# design.net
KiCad netlist of a schematic drawn in EasyEDA Pro
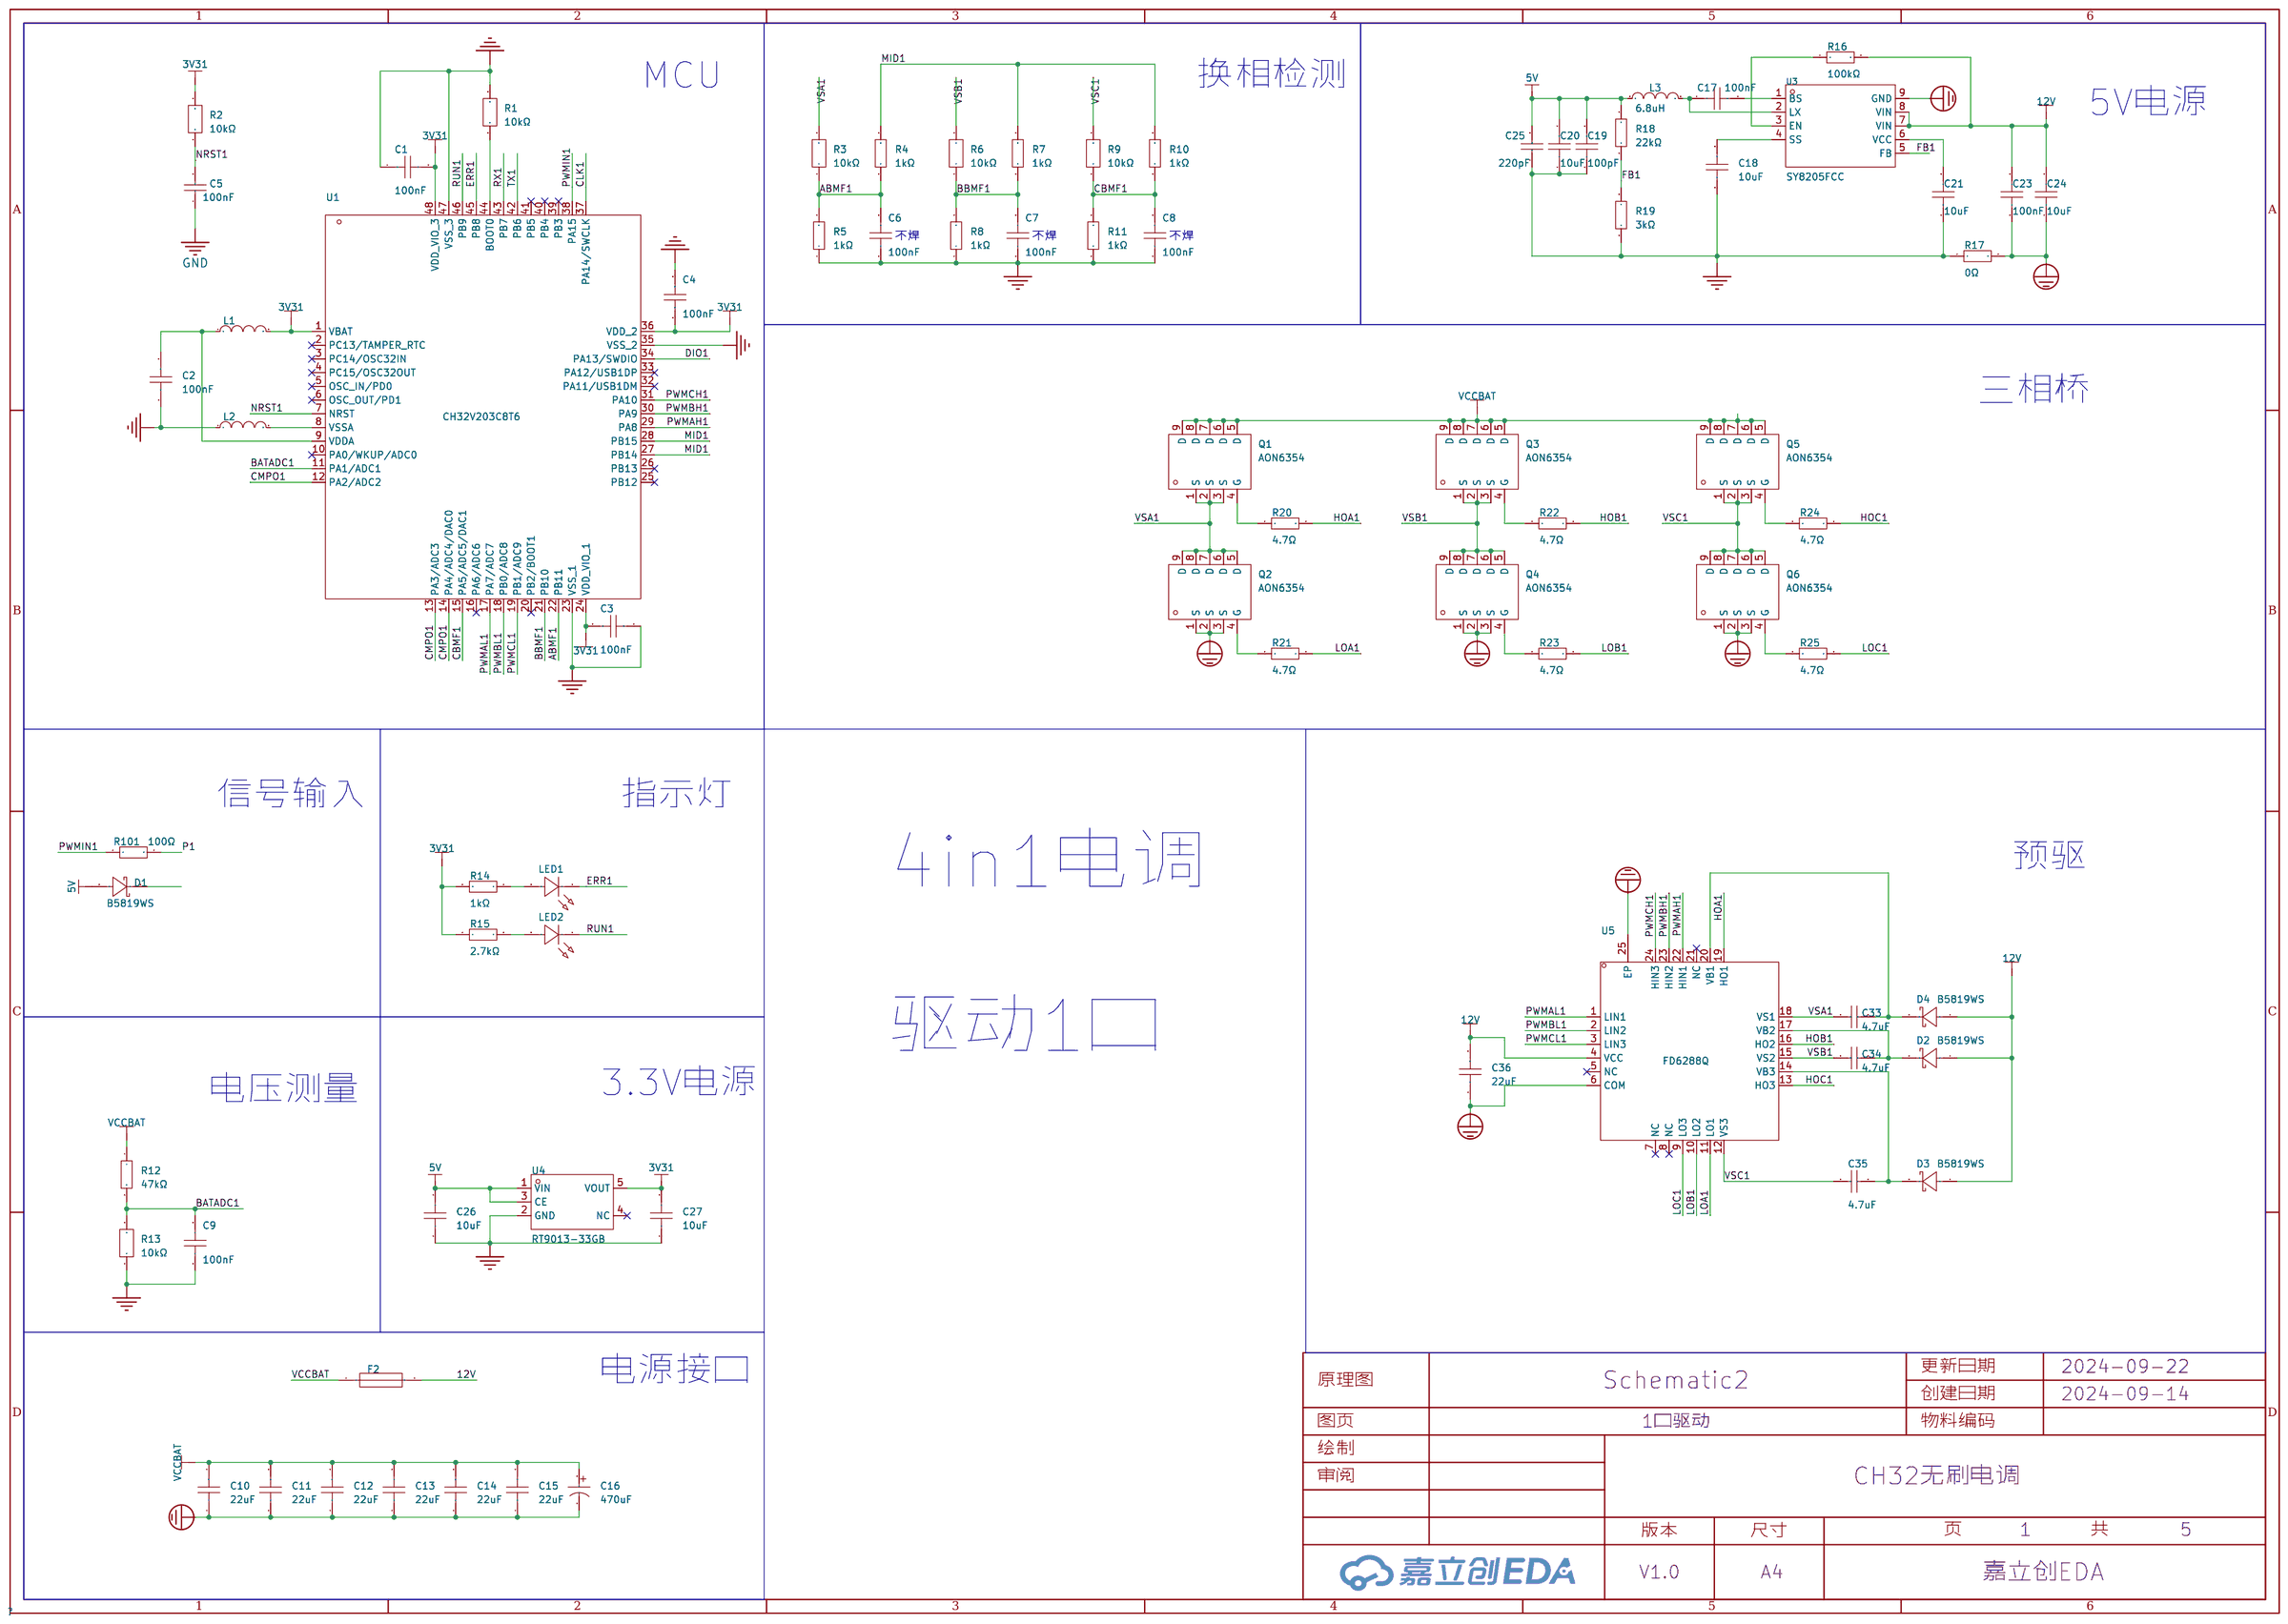
[diagram p0: 1口驱动]
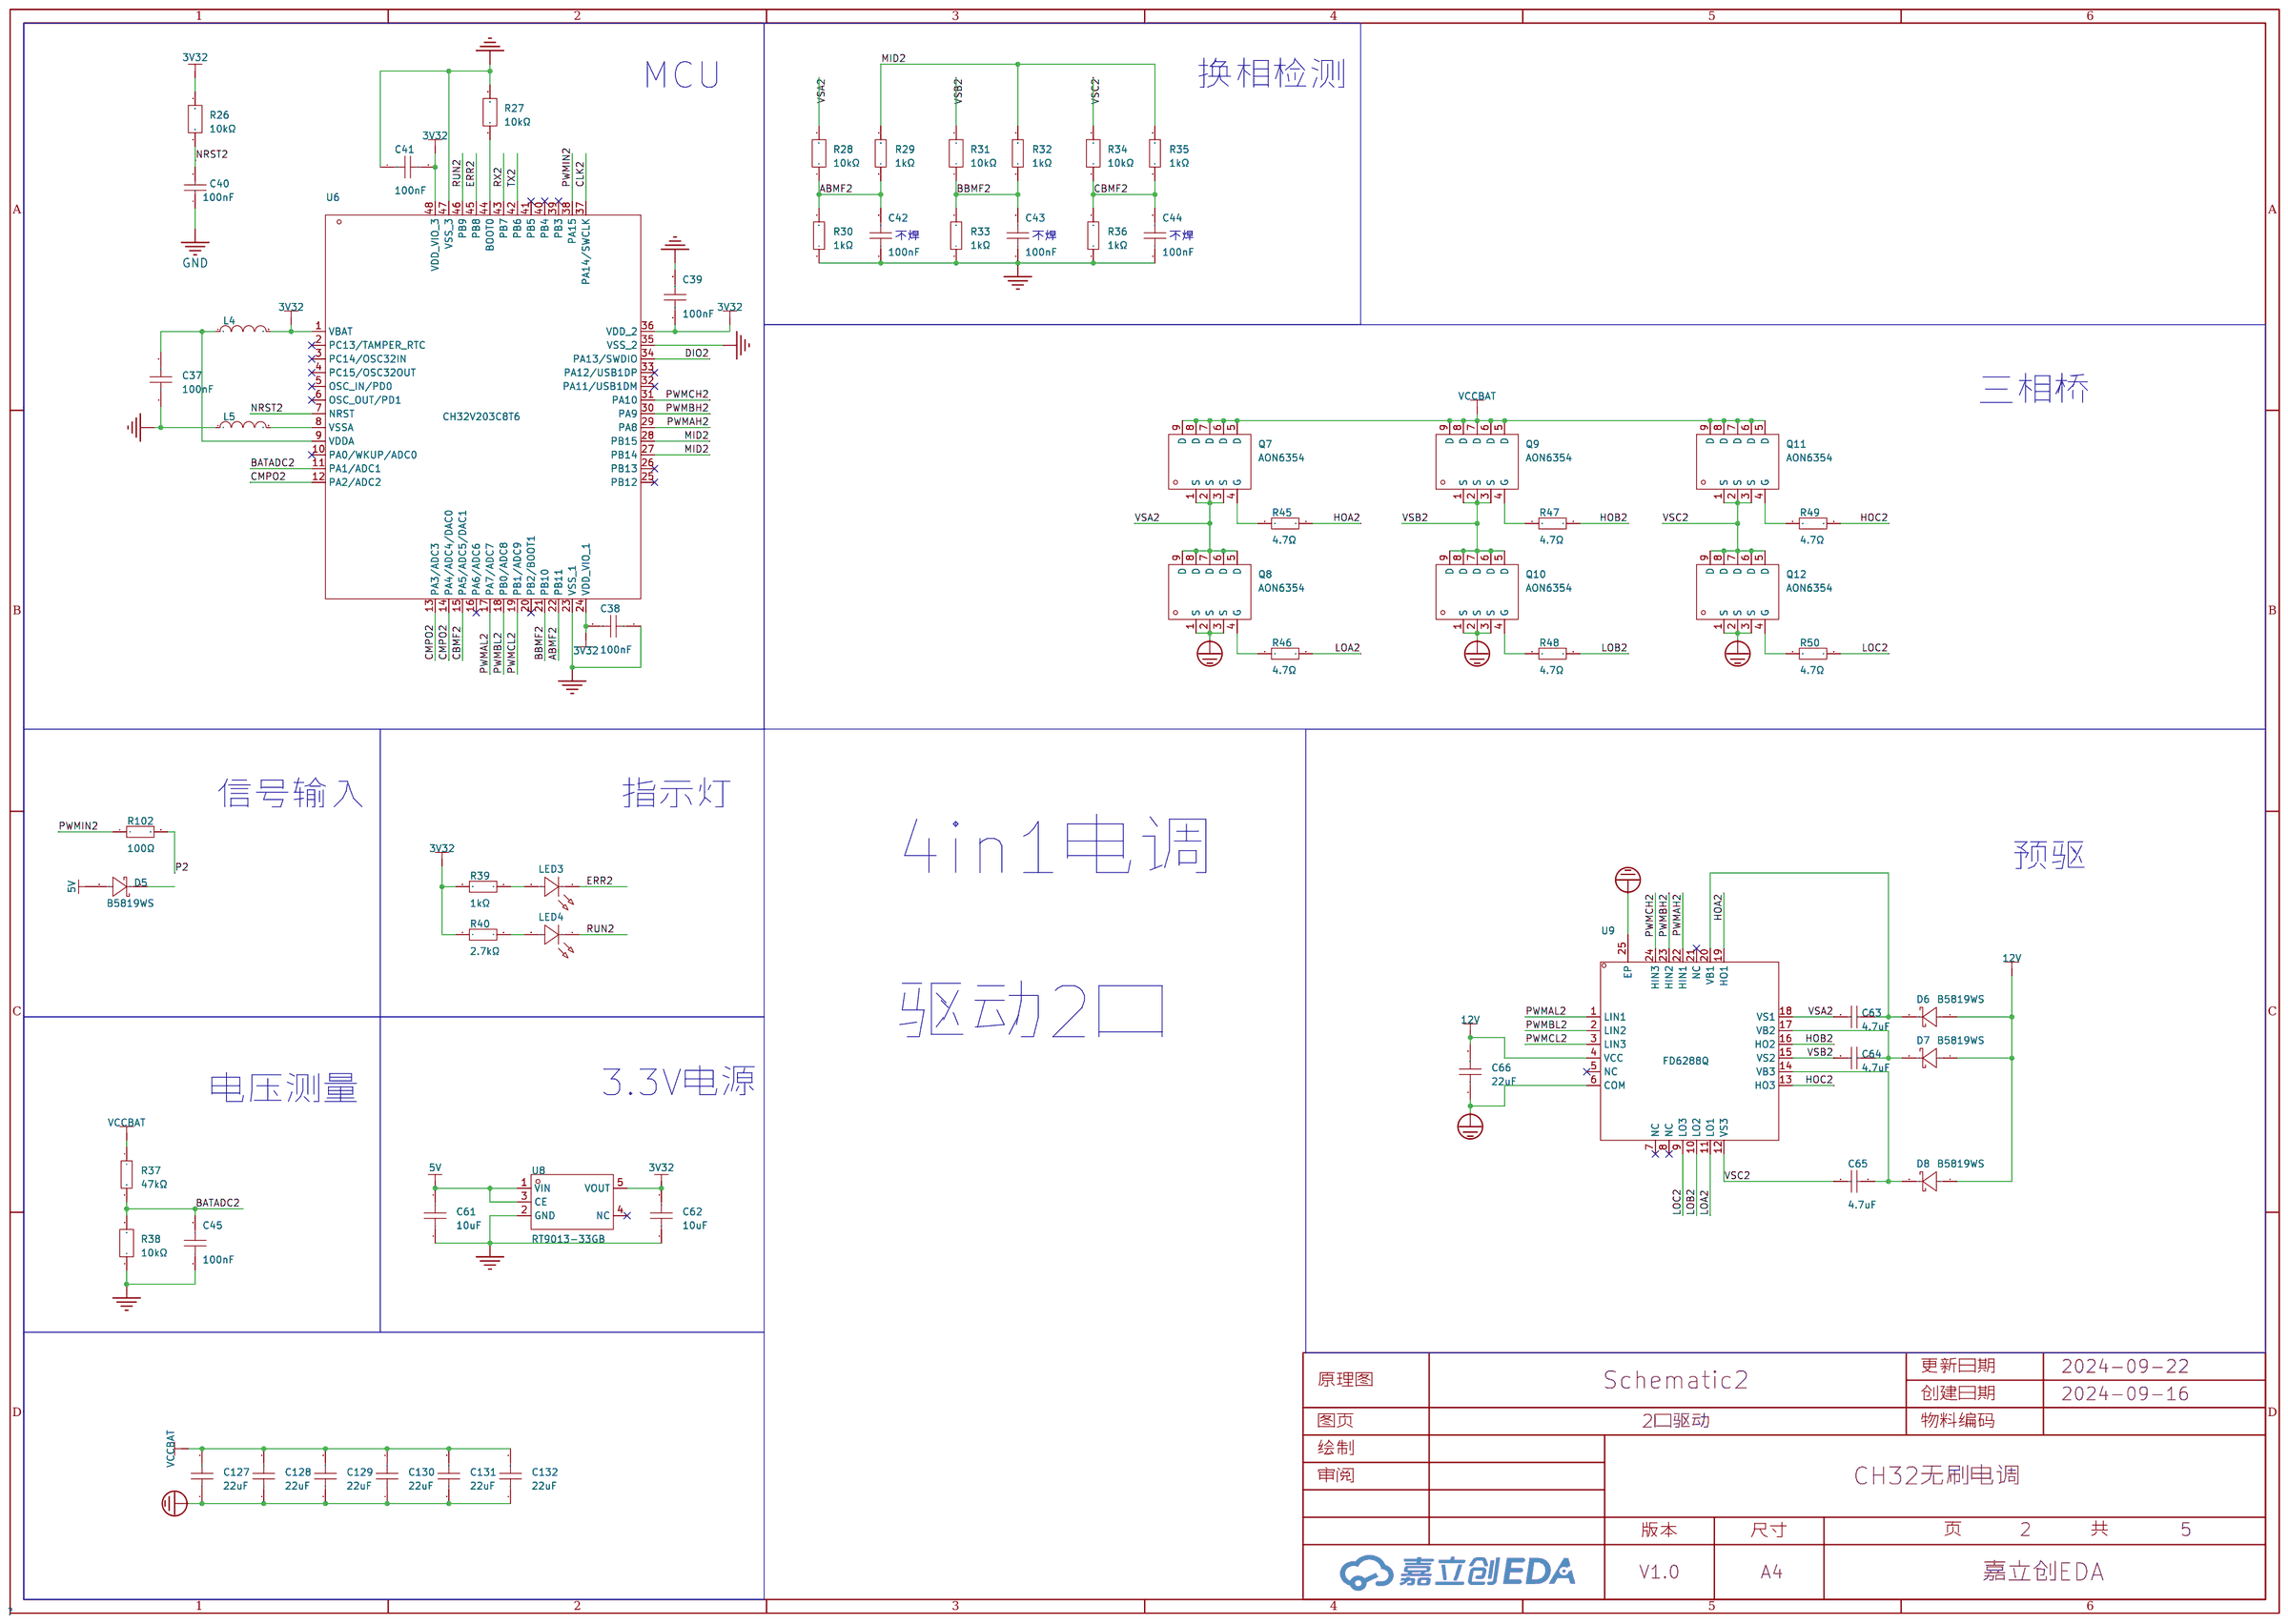
[diagram p1: 2口驱动]
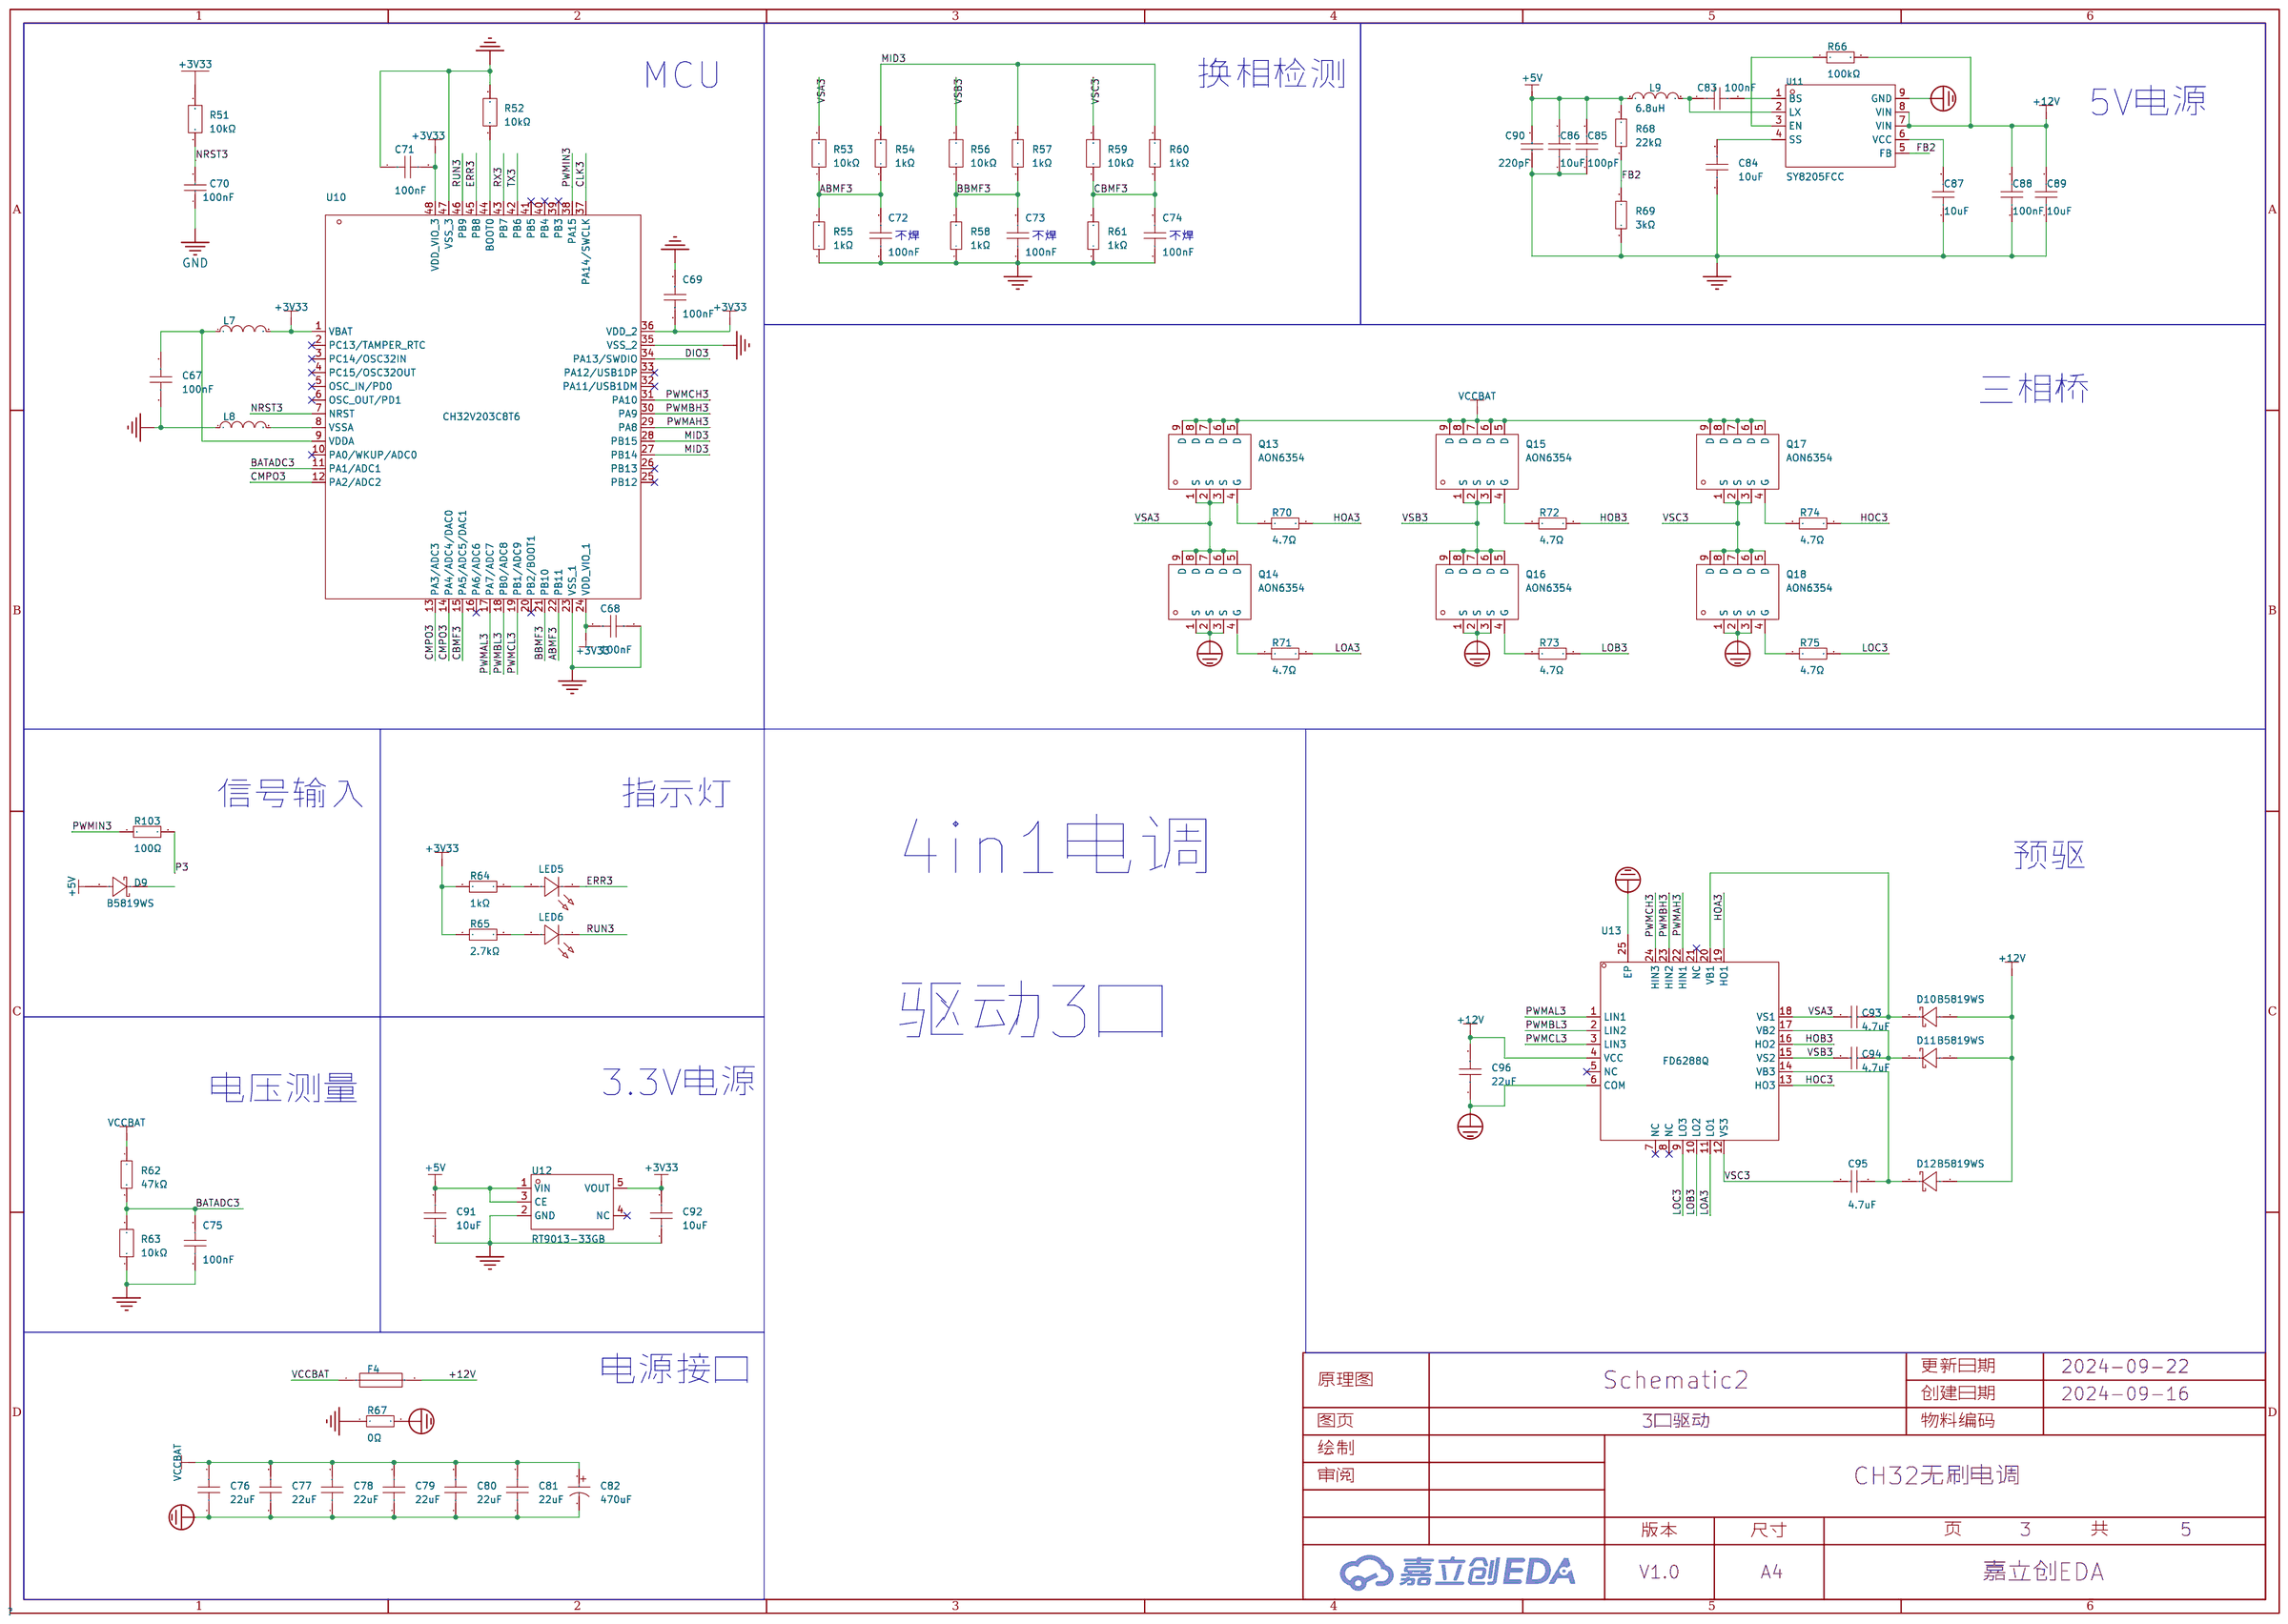
[diagram p2: 3口驱动]
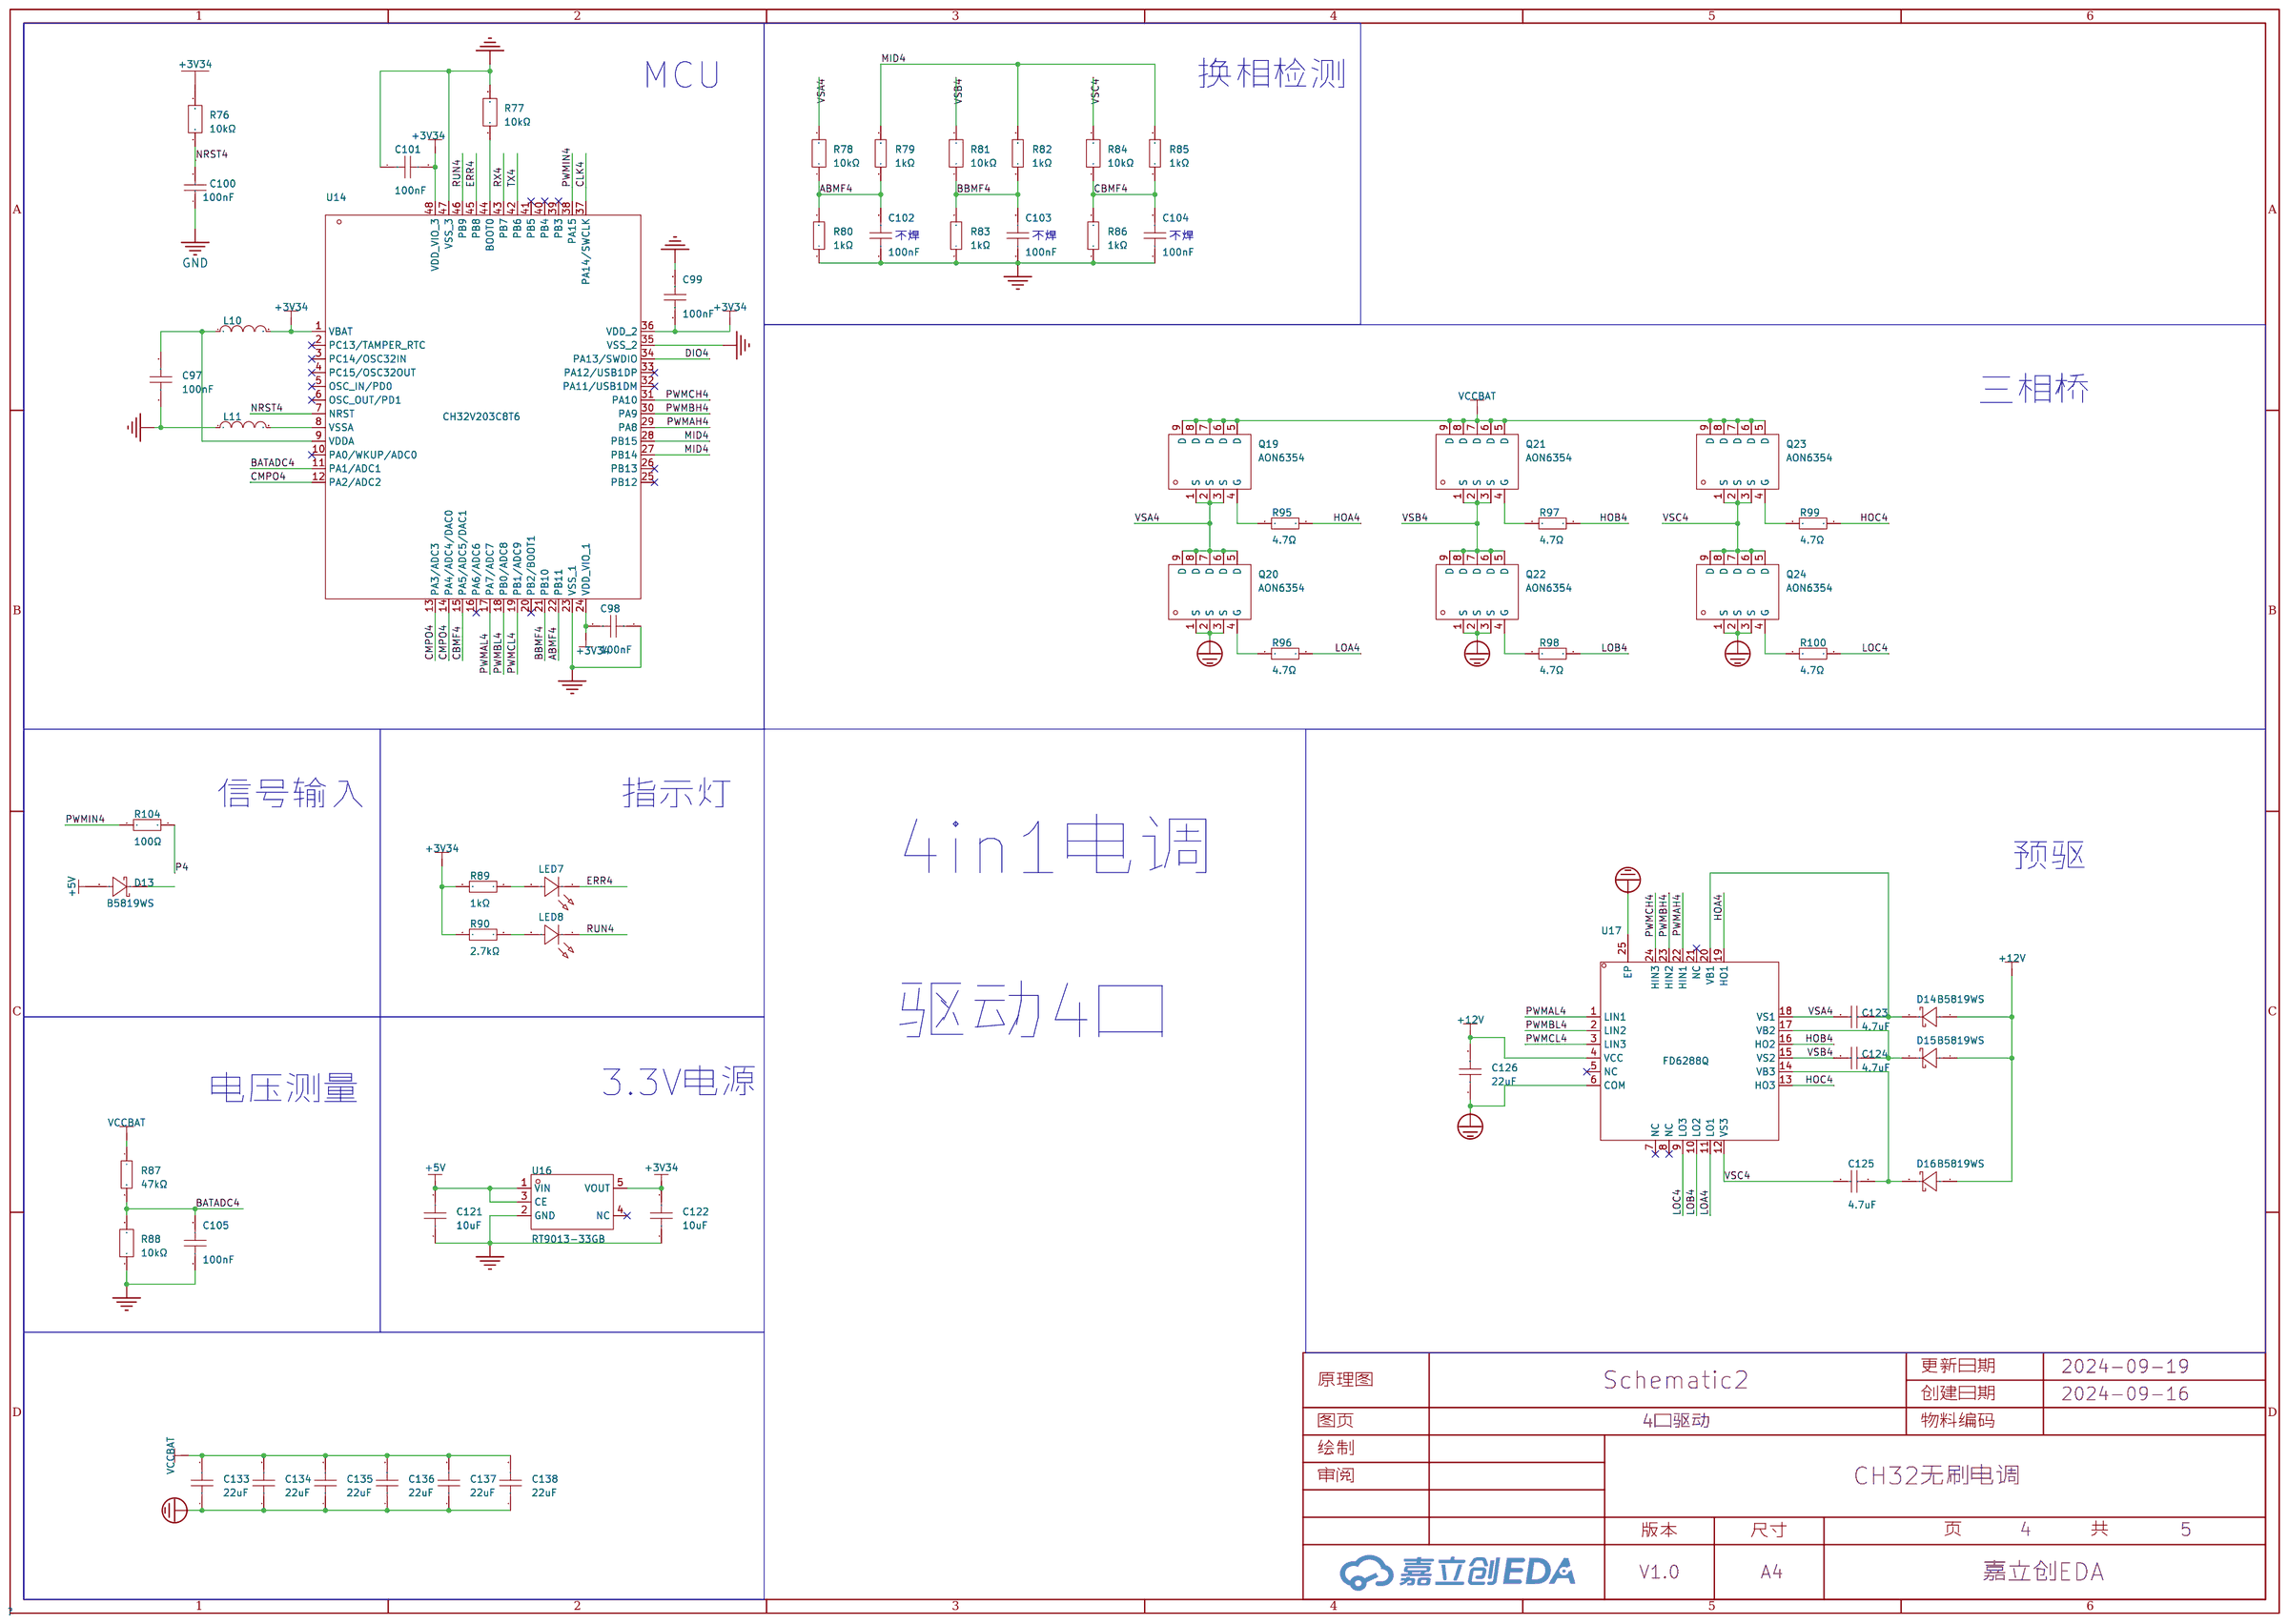
[diagram p3: 4口驱动]
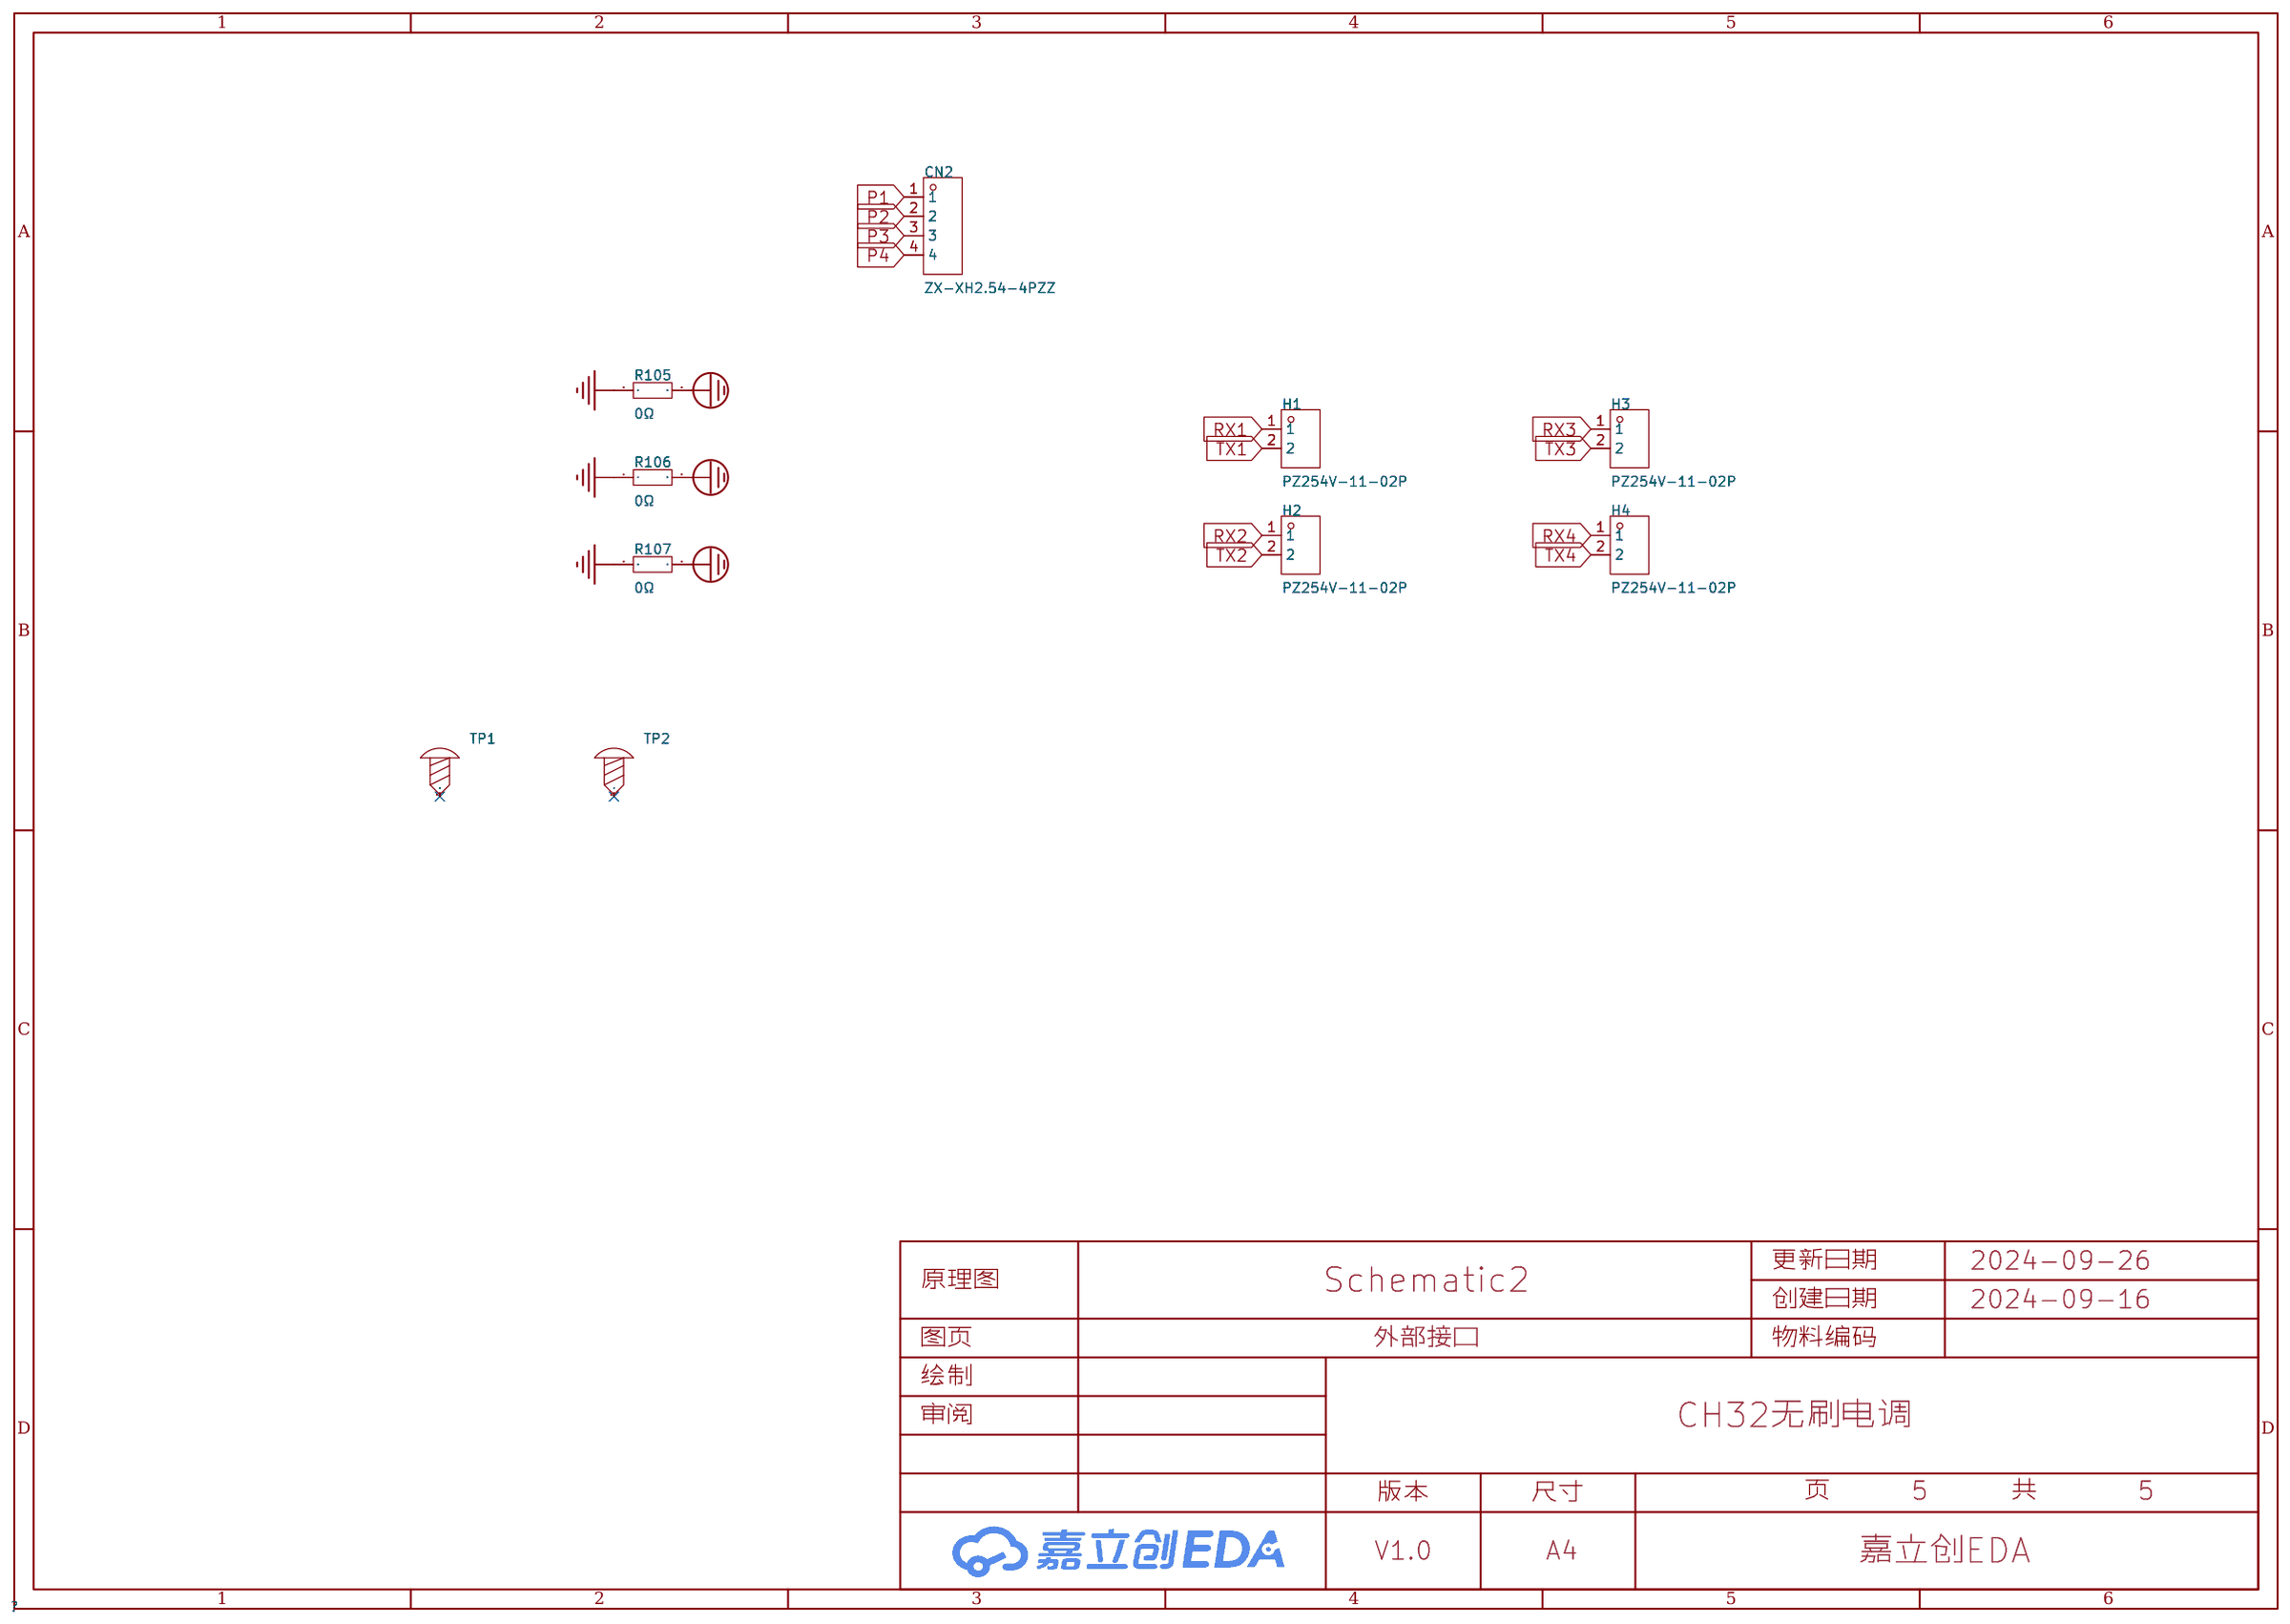
[diagram p4: 外部接口]

(export (version "E")
  (design (tool "Eeschema 10.0.6"))
  (components
    (comp (ref "C1")
      (value "100nF")
      (footprint "easyedapro:C0603")
      (description "容值:100nF;精度:±10%;额定电压:50V;材质(温度系数):X7R;")
      (fields
        (field (name "Manufacturer Part") "CGA0603X7R104K500JT")
        (field (name "Manufacturer") "HRE(芯声)")
      )
      (libsource (lib "easyedapro") (part "CGA0603X7R104K500JT"))
    )
    (comp (ref "C2")
      (value "100nF")
      (footprint "easyedapro:C0603")
      (description "容值:100nF;精度:±10%;额定电压:50V;材质(温度系数):X7R;")
      (fields
        (field (name "Manufacturer Part") "CGA0603X7R104K500JT")
        (field (name "Manufacturer") "HRE(芯声)")
      )
      (libsource (lib "easyedapro") (part "CGA0603X7R104K500JT"))
    )
    (comp (ref "C3")
      (value "100nF")
      (footprint "easyedapro:C0603")
      (description "容值:100nF;精度:±10%;额定电压:50V;材质(温度系数):X7R;")
      (fields
        (field (name "Manufacturer Part") "CGA0603X7R104K500JT")
        (field (name "Manufacturer") "HRE(芯声)")
      )
      (libsource (lib "easyedapro") (part "CGA0603X7R104K500JT"))
    )
    (comp (ref "C4")
      (value "100nF")
      (footprint "easyedapro:C0603")
      (description "容值:100nF;精度:±10%;额定电压:50V;材质(温度系数):X7R;")
      (fields
        (field (name "Manufacturer Part") "CGA0603X7R104K500JT")
        (field (name "Manufacturer") "HRE(芯声)")
      )
      (libsource (lib "easyedapro") (part "CGA0603X7R104K500JT"))
    )
    (comp (ref "C5")
      (value "100nF")
      (footprint "easyedapro:C0402")
      (description "容值:100nF;精度:±10%;额定电压:50V;温度系数:X7R;")
      (fields
        (field (name "Manufacturer Part") "CL05B104KB54PNC")
        (field (name "Manufacturer") "SAMSUNG(三星)")
      )
      (libsource (lib "easyedapro") (part "C 0402"))
    )
    (comp (ref "C6")
      (value "100nF")
      (footprint "easyedapro:C0603")
      (description "容值:100nF;精度:±10%;额定电压:50V;材质(温度系数):X7R;")
      (fields
        (field (name "Manufacturer Part") "CGA0603X7R104K500JT")
        (field (name "Manufacturer") "HRE(芯声)")
      )
      (libsource (lib "easyedapro") (part "CGA0603X7R104K500JT"))
    )
    (comp (ref "C7")
      (value "100nF")
      (footprint "easyedapro:C0603")
      (description "容值:100nF;精度:±10%;额定电压:50V;材质(温度系数):X7R;")
      (fields
        (field (name "Manufacturer Part") "CGA0603X7R104K500JT")
        (field (name "Manufacturer") "HRE(芯声)")
      )
      (libsource (lib "easyedapro") (part "CGA0603X7R104K500JT"))
    )
    (comp (ref "C8")
      (value "100nF")
      (footprint "easyedapro:C0603")
      (description "容值:100nF;精度:±10%;额定电压:50V;材质(温度系数):X7R;")
      (fields
        (field (name "Manufacturer Part") "CGA0603X7R104K500JT")
        (field (name "Manufacturer") "HRE(芯声)")
      )
      (libsource (lib "easyedapro") (part "CGA0603X7R104K500JT"))
    )
    (comp (ref "C9")
      (value "100nF")
      (footprint "easyedapro:C0603")
      (description "容值:100nF;精度:±10%;额定电压:50V;材质(温度系数):X7R;")
      (fields
        (field (name "Manufacturer Part") "CGA0603X7R104K500JT")
        (field (name "Manufacturer") "HRE(芯声)")
      )
      (libsource (lib "easyedapro") (part "CGA0603X7R104K500JT"))
    )
    (comp (ref "C10")
      (value "22uF")
      (footprint "easyedapro:C0805")
      (description "容值:22uF;精度:±20%;额定电压:35V;材质(温度系数):X5R;")
      (fields
        (field (name "Manufacturer Part") "CGA0805X5R226M350MT")
        (field (name "Manufacturer") "HRE(芯声)")
      )
      (libsource (lib "easyedapro") (part "CGA0805X5R226M350MT"))
    )
    (comp (ref "C11")
      (value "22uF")
      (footprint "easyedapro:C0805")
      (description "容值:22uF;精度:±20%;额定电压:35V;材质(温度系数):X5R;")
      (fields
        (field (name "Manufacturer Part") "CGA0805X5R226M350MT")
        (field (name "Manufacturer") "HRE(芯声)")
      )
      (libsource (lib "easyedapro") (part "CGA0805X5R226M350MT"))
    )
    (comp (ref "C12")
      (value "22uF")
      (footprint "easyedapro:C0805")
      (description "容值:22uF;精度:±20%;额定电压:35V;材质(温度系数):X5R;")
      (fields
        (field (name "Manufacturer Part") "CGA0805X5R226M350MT")
        (field (name "Manufacturer") "HRE(芯声)")
      )
      (libsource (lib "easyedapro") (part "CGA0805X5R226M350MT"))
    )
    (comp (ref "C13")
      (value "22uF")
      (footprint "easyedapro:C0805")
      (description "容值:22uF;精度:±20%;额定电压:35V;材质(温度系数):X5R;")
      (fields
        (field (name "Manufacturer Part") "CGA0805X5R226M350MT")
        (field (name "Manufacturer") "HRE(芯声)")
      )
      (libsource (lib "easyedapro") (part "CGA0805X5R226M350MT"))
    )
    (comp (ref "C14")
      (value "22uF")
      (footprint "easyedapro:C0805")
      (description "容值:22uF;精度:±20%;额定电压:35V;材质(温度系数):X5R;")
      (fields
        (field (name "Manufacturer Part") "CGA0805X5R226M350MT")
        (field (name "Manufacturer") "HRE(芯声)")
      )
      (libsource (lib "easyedapro") (part "CGA0805X5R226M350MT"))
    )
    (comp (ref "C15")
      (value "22uF")
      (footprint "easyedapro:C0805")
      (description "容值:22uF;精度:±20%;额定电压:35V;材质(温度系数):X5R;")
      (fields
        (field (name "Manufacturer Part") "CGA0805X5R226M350MT")
        (field (name "Manufacturer") "HRE(芯声)")
      )
      (libsource (lib "easyedapro") (part "CGA0805X5R226M350MT"))
    )
    (comp (ref "C16")
      (value "470uF")
      (footprint "easyedapro:CAP-TH_BD8.0-P3.50-D0.6-FD")
      (description "容值:470uF;精度:±20%;额定电压:25V;")
      (fields
        (field (name "Manufacturer Part") "KM477M025F12RR0VH2FP0")
        (field (name "Manufacturer") "CX(承兴)")
      )
      (libsource (lib "easyedapro") (part "470uF 25V 8*12"))
    )
    (comp (ref "C17")
      (value "100nF")
      (footprint "easyedapro:C0603")
      (description "容值:100nF;精度:±10%;额定电压:50V;材质(温度系数):X7R;")
      (fields
        (field (name "Manufacturer Part") "CGA0603X7R104K500JT")
        (field (name "Manufacturer") "HRE(芯声)")
      )
      (libsource (lib "easyedapro") (part "CGA0603X7R104K500JT"))
    )
    (comp (ref "C18")
      (value "10uF")
      (footprint "easyedapro:C0805")
      (description "容值:10uF;精度:±10%;额定电压:50V;材质(温度系数):X5R;")
      (fields
        (field (name "Manufacturer Part") "CL21A106KBYQNNE")
        (field (name "Manufacturer") "SAMSUNG(三星)")
      )
      (libsource (lib "easyedapro") (part "CL21A106KBYQNNE"))
    )
    (comp (ref "C19")
      (value "100pF")
      (footprint "easyedapro:C0603")
      (description "容值:100pF;精度:±5%;额定电压:50V;材质(温度系数):NP0;")
      (fields
        (field (name "Manufacturer Part") "CC0603JRNPO9BN101")
        (field (name "Manufacturer") "YAGEO(国巨)")
      )
      (libsource (lib "easyedapro") (part "CC0603JRNPO9BN101"))
    )
    (comp (ref "C20")
      (value "10uF")
      (footprint "easyedapro:C0603")
      (description "容值:10uF;精度:±20%;额定电压:25V;材质(温度系数):X5R;")
      (fields
        (field (name "Manufacturer Part") "CL10A106MA8NRNC")
        (field (name "Manufacturer") "SAMSUNG(三星)")
      )
      (libsource (lib "easyedapro") (part "CL10A106MA8NRNC"))
    )
    (comp (ref "C21")
      (value "10uF")
      (footprint "easyedapro:C0603")
      (description "容值:10uF;精度:±20%;额定电压:25V;材质(温度系数):X5R;")
      (fields
        (field (name "Manufacturer Part") "CL10A106MA8NRNC")
        (field (name "Manufacturer") "SAMSUNG(三星)")
      )
      (libsource (lib "easyedapro") (part "CL10A106MA8NRNC"))
    )
    (comp (ref "C23")
      (value "100nF")
      (footprint "easyedapro:C0603")
      (description "容值:100nF;精度:±10%;额定电压:50V;材质(温度系数):X7R;")
      (fields
        (field (name "Manufacturer Part") "CGA0603X7R104K500JT")
        (field (name "Manufacturer") "HRE(芯声)")
      )
      (libsource (lib "easyedapro") (part "CGA0603X7R104K500JT"))
    )
    (comp (ref "C24")
      (value "10uF")
      (footprint "easyedapro:C0805")
      (description "容值:10uF;精度:±10%;额定电压:50V;材质(温度系数):X5R;")
      (fields
        (field (name "Manufacturer Part") "CL21A106KBYQNNE")
        (field (name "Manufacturer") "SAMSUNG(三星)")
      )
      (libsource (lib "easyedapro") (part "CL21A106KBYQNNE"))
    )
    (comp (ref "C25")
      (value "220pF")
      (footprint "easyedapro:C0603")
      (description "容值:220pF;精度:±10%;额定电压:50V;材质(温度系数):X7R;")
      (fields
        (field (name "Manufacturer Part") "CL10B221KB8NNNC")
        (field (name "Manufacturer") "SAMSUNG(三星)")
      )
      (libsource (lib "easyedapro") (part "CL10B221KB8NNNC"))
    )
    (comp (ref "C26")
      (value "10uF")
      (footprint "easyedapro:C0603")
      (description "容值:10uF;精度:±10%;额定电压:10V;材质(温度系数):X5R;")
      (fields
        (field (name "Manufacturer Part") "CL10A106KP8NNNC")
        (field (name "Manufacturer") "SAMSUNG(三星)")
      )
      (libsource (lib "easyedapro") (part "CL10A106KP8NNNC"))
    )
    (comp (ref "C27")
      (value "10uF")
      (footprint "easyedapro:C0603")
      (description "容值:10uF;精度:±10%;额定电压:10V;材质(温度系数):X5R;")
      (fields
        (field (name "Manufacturer Part") "CL10A106KP8NNNC")
        (field (name "Manufacturer") "SAMSUNG(三星)")
      )
      (libsource (lib "easyedapro") (part "CL10A106KP8NNNC"))
    )
    (comp (ref "C33")
      (value "4.7uF")
      (footprint "easyedapro:C0603")
      (description "容值:4.7uF;精度:±10%;额定电压:16V;材质(温度系数):X5R;")
      (fields
        (field (name "Manufacturer Part") "CL10A475KO8NNNC")
        (field (name "Manufacturer") "SAMSUNG(三星)")
      )
      (libsource (lib "easyedapro") (part "CL10A475KO8NNNC"))
    )
    (comp (ref "C34")
      (value "4.7uF")
      (footprint "easyedapro:C0603")
      (description "容值:4.7uF;精度:±10%;额定电压:16V;材质(温度系数):X5R;")
      (fields
        (field (name "Manufacturer Part") "CL10A475KO8NNNC")
        (field (name "Manufacturer") "SAMSUNG(三星)")
      )
      (libsource (lib "easyedapro") (part "CL10A475KO8NNNC"))
    )
    (comp (ref "C35")
      (value "4.7uF")
      (footprint "easyedapro:C0603")
      (description "容值:4.7uF;精度:±10%;额定电压:16V;材质(温度系数):X5R;")
      (fields
        (field (name "Manufacturer Part") "CL10A475KO8NNNC")
        (field (name "Manufacturer") "SAMSUNG(三星)")
      )
      (libsource (lib "easyedapro") (part "CL10A475KO8NNNC"))
    )
    (comp (ref "C36")
      (value "22uF")
      (footprint "easyedapro:C0805")
      (description "容值:22uF;精度:±20%;额定电压:25V;材质(温度系数):X5R;")
      (fields
        (field (name "Manufacturer Part") "CL21A226MAQNNNE")
        (field (name "Manufacturer") "SAMSUNG(三星)")
      )
      (libsource (lib "easyedapro") (part "CL21A226MAQNNNE"))
    )
    (comp (ref "D1")
      (value "B5819WS")
      (footprint "easyedapro:SOD-323_L1.7-W1.3-LS2.5-FD")
      (description "二极管配置:独立式;正向压降(Vf):600mV@1.0A;直流反向耐压(Vr):40V;平均整流电流(Io):1A;")
      (fields (field (name "Manufacturer") "宏迦橙"))
      (libsource (lib "easyedapro") (part "B5819WS_C7420331"))
    )
    (comp (ref "D2")
      (value "B5819WS")
      (footprint "easyedapro:SOD-323_L1.7-W1.3-LS2.5-FD")
      (description "二极管配置:独立式;正向压降(Vf):600mV@1.0A;直流反向耐压(Vr):40V;平均整流电流(Io):1A;")
      (fields (field (name "Manufacturer") "宏迦橙"))
      (libsource (lib "easyedapro") (part "B5819WS_C7420331"))
    )
    (comp (ref "D3")
      (value "B5819WS")
      (footprint "easyedapro:SOD-323_L1.7-W1.3-LS2.5-FD")
      (description "二极管配置:独立式;正向压降(Vf):600mV@1.0A;直流反向耐压(Vr):40V;平均整流电流(Io):1A;")
      (fields (field (name "Manufacturer") "宏迦橙"))
      (libsource (lib "easyedapro") (part "B5819WS_C7420331"))
    )
    (comp (ref "D4")
      (value "B5819WS")
      (footprint "easyedapro:SOD-323_L1.7-W1.3-LS2.5-FD")
      (description "二极管配置:独立式;正向压降(Vf):600mV@1.0A;直流反向耐压(Vr):40V;平均整流电流(Io):1A;")
      (fields (field (name "Manufacturer") "宏迦橙"))
      (libsource (lib "easyedapro") (part "B5819WS_C7420331"))
    )
    (comp (ref "F2")
      (value "BSMD1206-150-16V")
      (footprint "easyedapro:F1206")
      (description "最大电压:16V;最大电流:40A;保持电流:1.5A;跳闸电流:3A;")
      (fields (field (name "Manufacturer") "BHFUSE(佰宏)"))
      (libsource (lib "easyedapro") (part "BSMD1206-150-16V"))
    )
    (comp (ref "L1")
      (value "CBG160808U000T")
      (footprint "easyedapro:L0603")
      (description "标称阻抗@测试频率:0Ω@100MHz;直流电阻(RDC):100mΩ;")
      (fields (field (name "Manufacturer") "FH(风华)"))
      (libsource (lib "easyedapro") (part "CBG160808U000T"))
    )
    (comp (ref "L2")
      (value "CBG160808U000T")
      (footprint "easyedapro:L0603")
      (description "标称阻抗@测试频率:0Ω@100MHz;直流电阻(RDC):100mΩ;")
      (fields (field (name "Manufacturer") "FH(风华)"))
      (libsource (lib "easyedapro") (part "CBG160808U000T"))
    )
    (comp (ref "L3")
      (value "6.8uH")
      (footprint "easyedapro:IND-SMD_L5.4-W5.2_FXL0530")
      (description "电感值:6.8uH;精度:±20%;额定电流:3.5A;饱和电流(Isat):4A;类型:一体成型电感;")
      (fields (field (name "Manufacturer Part") "FXL0530-6R8-M") (field (name "Manufacturer") "cjiang(长江微电)"))
      (libsource (lib "easyedapro") (part "FXL0530-6R8-M"))
    )
    (comp (ref "LED1")
      (value "XL-1608UGC-04")
      (footprint "easyedapro:LED0603-RD_GREEN")
      (fields (field (name "Manufacturer") "XINGLIGHT(成兴光)"))
      (libsource (lib "easyedapro") (part "XL-1608UGC-04"))
    )
    (comp (ref "LED2")
      (value "XL-1608UGC-04")
      (footprint "easyedapro:LED0603-RD_GREEN")
      (fields (field (name "Manufacturer") "XINGLIGHT(成兴光)"))
      (libsource (lib "easyedapro") (part "XL-1608UGC-04"))
    )
    (comp (ref "Q1")
      (value "AON6354")
      (footprint "easyedapro:DFN-8_L5.2-W6.1-P1.27-BL-EP")
      (fields (field (name "Manufacturer") "AOS"))
      (libsource (lib "easyedapro") (part "AON6354"))
    )
    (comp (ref "Q2")
      (value "AON6354")
      (footprint "easyedapro:DFN-8_L5.2-W6.1-P1.27-BL-EP")
      (fields (field (name "Manufacturer") "AOS"))
      (libsource (lib "easyedapro") (part "AON6354"))
    )
    (comp (ref "Q3")
      (value "AON6354")
      (footprint "easyedapro:DFN-8_L5.2-W6.1-P1.27-BL-EP")
      (fields (field (name "Manufacturer") "AOS"))
      (libsource (lib "easyedapro") (part "AON6354"))
    )
    (comp (ref "Q4")
      (value "AON6354")
      (footprint "easyedapro:DFN-8_L5.2-W6.1-P1.27-BL-EP")
      (fields (field (name "Manufacturer") "AOS"))
      (libsource (lib "easyedapro") (part "AON6354"))
    )
    (comp (ref "Q5")
      (value "AON6354")
      (footprint "easyedapro:DFN-8_L5.2-W6.1-P1.27-BL-EP")
      (fields (field (name "Manufacturer") "AOS"))
      (libsource (lib "easyedapro") (part "AON6354"))
    )
    (comp (ref "Q6")
      (value "AON6354")
      (footprint "easyedapro:DFN-8_L5.2-W6.1-P1.27-BL-EP")
      (fields (field (name "Manufacturer") "AOS"))
      (libsource (lib "easyedapro") (part "AON6354"))
    )
    (comp (ref "R1")
      (value "10kΩ")
      (footprint "easyedapro:R0603")
      (description "电阻类型:厚膜电阻;阻值:10kΩ;精度:±5%;功率:100mW;最大工作电压:75V;温度系数:±100ppm/°C;")
      (fields (field (name "Manufacturer Part") "FRC0603J103TS") (field (name "Manufacturer") "FOJAN(富捷)"))
      (libsource (lib "easyedapro") (part "FRC0603J103TS"))
    )
    (comp (ref "R2")
      (value "10kΩ")
      (footprint "easyedapro:R0603")
      (description "电阻类型:厚膜电阻;阻值:10kΩ;精度:±5%;功率:100mW;最大工作电压:75V;温度系数:±100ppm/°C;")
      (fields (field (name "Manufacturer Part") "FRC0603J103TS") (field (name "Manufacturer") "FOJAN(富捷)"))
      (libsource (lib "easyedapro") (part "FRC0603J103TS"))
    )
    (comp (ref "R3")
      (value "10kΩ")
      (footprint "easyedapro:R0603")
      (description "电阻类型:厚膜电阻;阻值:10kΩ;精度:±5%;功率:100mW;最大工作电压:75V;温度系数:±100ppm/°C;")
      (fields (field (name "Manufacturer Part") "FRC0603J103TS") (field (name "Manufacturer") "FOJAN(富捷)"))
      (libsource (lib "easyedapro") (part "FRC0603J103TS"))
    )
    (comp (ref "R4")
      (value "1kΩ")
      (footprint "easyedapro:R0603")
      (description "电阻类型:厚膜电阻;阻值:1kΩ;精度:±1%;功率:100mW;最大工作电压:75V;温度系数:±100ppm/°C;")
      (fields (field (name "Manufacturer Part") "RC0603FR-071KL") (field (name "Manufacturer") "YAGEO(国巨)"))
      (libsource (lib "easyedapro") (part "RC0603FR-071KL"))
    )
    (comp (ref "R5")
      (value "1kΩ")
      (footprint "easyedapro:R0603")
      (description "电阻类型:厚膜电阻;阻值:1kΩ;精度:±1%;功率:100mW;最大工作电压:75V;温度系数:±100ppm/°C;")
      (fields (field (name "Manufacturer Part") "RC0603FR-071KL") (field (name "Manufacturer") "YAGEO(国巨)"))
      (libsource (lib "easyedapro") (part "RC0603FR-071KL"))
    )
    (comp (ref "R6")
      (value "10kΩ")
      (footprint "easyedapro:R0603")
      (description "电阻类型:厚膜电阻;阻值:10kΩ;精度:±5%;功率:100mW;最大工作电压:75V;温度系数:±100ppm/°C;")
      (fields (field (name "Manufacturer Part") "FRC0603J103TS") (field (name "Manufacturer") "FOJAN(富捷)"))
      (libsource (lib "easyedapro") (part "FRC0603J103TS"))
    )
    (comp (ref "R7")
      (value "1kΩ")
      (footprint "easyedapro:R0603")
      (description "电阻类型:厚膜电阻;阻值:1kΩ;精度:±1%;功率:100mW;最大工作电压:75V;温度系数:±100ppm/°C;")
      (fields (field (name "Manufacturer Part") "RC0603FR-071KL") (field (name "Manufacturer") "YAGEO(国巨)"))
      (libsource (lib "easyedapro") (part "RC0603FR-071KL"))
    )
    (comp (ref "R8")
      (value "1kΩ")
      (footprint "easyedapro:R0603")
      (description "电阻类型:厚膜电阻;阻值:1kΩ;精度:±1%;功率:100mW;最大工作电压:75V;温度系数:±100ppm/°C;")
      (fields (field (name "Manufacturer Part") "RC0603FR-071KL") (field (name "Manufacturer") "YAGEO(国巨)"))
      (libsource (lib "easyedapro") (part "RC0603FR-071KL"))
    )
    (comp (ref "R9")
      (value "10kΩ")
      (footprint "easyedapro:R0603")
      (description "电阻类型:厚膜电阻;阻值:10kΩ;精度:±5%;功率:100mW;最大工作电压:75V;温度系数:±100ppm/°C;")
      (fields (field (name "Manufacturer Part") "FRC0603J103TS") (field (name "Manufacturer") "FOJAN(富捷)"))
      (libsource (lib "easyedapro") (part "FRC0603J103TS"))
    )
    (comp (ref "R10")
      (value "1kΩ")
      (footprint "easyedapro:R0603")
      (description "电阻类型:厚膜电阻;阻值:1kΩ;精度:±1%;功率:100mW;最大工作电压:75V;温度系数:±100ppm/°C;")
      (fields (field (name "Manufacturer Part") "RC0603FR-071KL") (field (name "Manufacturer") "YAGEO(国巨)"))
      (libsource (lib "easyedapro") (part "RC0603FR-071KL"))
    )
    (comp (ref "R11")
      (value "1kΩ")
      (footprint "easyedapro:R0603")
      (description "电阻类型:厚膜电阻;阻值:1kΩ;精度:±1%;功率:100mW;最大工作电压:75V;温度系数:±100ppm/°C;")
      (fields (field (name "Manufacturer Part") "RC0603FR-071KL") (field (name "Manufacturer") "YAGEO(国巨)"))
      (libsource (lib "easyedapro") (part "RC0603FR-071KL"))
    )
    (comp (ref "R12")
      (value "47kΩ")
      (footprint "easyedapro:R0603")
      (description "电阻类型:厚膜电阻;阻值:47kΩ;精度:±1%;功率:100mW;最大工作电压:75V;温度系数:±100ppm/°C;")
      (fields
        (field (name "Manufacturer Part") "0603WAF4702T5E")
        (field (name "Manufacturer") "UNI-ROYAL(厚声)")
      )
      (libsource (lib "easyedapro") (part "0603WAF4702T5E"))
    )
    (comp (ref "R13")
      (value "10kΩ")
      (footprint "easyedapro:R0603")
      (description "电阻类型:厚膜电阻;阻值:10kΩ;精度:±5%;功率:100mW;最大工作电压:75V;温度系数:±100ppm/°C;")
      (fields (field (name "Manufacturer Part") "FRC0603J103TS") (field (name "Manufacturer") "FOJAN(富捷)"))
      (libsource (lib "easyedapro") (part "FRC0603J103TS"))
    )
    (comp (ref "R14")
      (value "1kΩ")
      (footprint "easyedapro:R0603")
      (description "电阻类型:厚膜电阻;阻值:1kΩ;精度:±1%;功率:100mW;最大工作电压:75V;温度系数:±100ppm/°C;")
      (fields (field (name "Manufacturer Part") "RC0603FR-071KL") (field (name "Manufacturer") "YAGEO(国巨)"))
      (libsource (lib "easyedapro") (part "RC0603FR-071KL"))
    )
    (comp (ref "R15")
      (value "2.7kΩ")
      (footprint "easyedapro:R0603")
      (description "电阻类型:厚膜电阻;阻值:2.7kΩ;精度:±1%;功率:100mW;最大工作电压:75V;温度系数:±100ppm/°C;")
      (fields
        (field (name "Manufacturer Part") "0603WAF2701T5E")
        (field (name "Manufacturer") "UNI-ROYAL(厚声)")
      )
      (libsource (lib "easyedapro") (part "0603WAF2701T5E"))
    )
    (comp (ref "R16")
      (value "100kΩ")
      (footprint "easyedapro:R0603")
      (description "电阻类型:厚膜电阻;阻值:100kΩ;精度:±1%;功率:100mW;最大工作电压:75V;温度系数:±100ppm/°C;")
      (fields
        (field (name "Manufacturer Part") "0603WAF1003T5E")
        (field (name "Manufacturer") "UNI-ROYAL(厚声)")
      )
      (libsource (lib "easyedapro") (part "0603WAF1003T5E"))
    )
    (comp (ref "R17")
      (value "0Ω")
      (footprint "easyedapro:R0603")
      (description "电阻类型:厚膜电阻;阻值:0Ω;精度:±1%;功率:100mW;最大工作电压:75V;")
      (fields
        (field (name "Manufacturer Part") "0603WAF0000T5E")
        (field (name "Manufacturer") "UNI-ROYAL(厚声)")
      )
      (libsource (lib "easyedapro") (part "0603WAF0000T5E"))
    )
    (comp (ref "R18")
      (value "22kΩ")
      (footprint "easyedapro:R0603")
      (description "电阻类型:厚膜电阻;阻值:22kΩ;精度:±1%;功率:100mW;最大工作电压:75V;温度系数:±100ppm/°C;")
      (fields
        (field (name "Manufacturer Part") "0603WAF2202T5E")
        (field (name "Manufacturer") "UNI-ROYAL(厚声)")
      )
      (libsource (lib "easyedapro") (part "0603WAF2202T5E"))
    )
    (comp (ref "R19")
      (value "3kΩ")
      (footprint "easyedapro:R0603")
      (description "电阻类型:厚膜电阻;阻值:3kΩ;精度:±1%;功率:100mW;最大工作电压:75V;温度系数:±100ppm/°C;")
      (fields
        (field (name "Manufacturer Part") "0603WAF3001T5E")
        (field (name "Manufacturer") "UNI-ROYAL(厚声)")
      )
      (libsource (lib "easyedapro") (part "0603WAF3001T5E"))
    )
    (comp (ref "R20")
      (value "4.7Ω")
      (footprint "easyedapro:R0603")
      (description "电阻类型:厚膜电阻;阻值:4.7Ω;精度:±1%;功率:100mW;最大工作电压:75V;温度系数:±400ppm/°C;")
      (fields
        (field (name "Manufacturer Part") "0603WAF470KT5E")
        (field (name "Manufacturer") "UNI-ROYAL(厚声)")
      )
      (libsource (lib "easyedapro") (part "0603WAF470KT5E"))
    )
    (comp (ref "R21")
      (value "4.7Ω")
      (footprint "easyedapro:R0603")
      (description "电阻类型:厚膜电阻;阻值:4.7Ω;精度:±1%;功率:100mW;最大工作电压:75V;温度系数:±400ppm/°C;")
      (fields
        (field (name "Manufacturer Part") "0603WAF470KT5E")
        (field (name "Manufacturer") "UNI-ROYAL(厚声)")
      )
      (libsource (lib "easyedapro") (part "0603WAF470KT5E"))
    )
    (comp (ref "R22")
      (value "4.7Ω")
      (footprint "easyedapro:R0603")
      (description "电阻类型:厚膜电阻;阻值:4.7Ω;精度:±1%;功率:100mW;最大工作电压:75V;温度系数:±400ppm/°C;")
      (fields
        (field (name "Manufacturer Part") "0603WAF470KT5E")
        (field (name "Manufacturer") "UNI-ROYAL(厚声)")
      )
      (libsource (lib "easyedapro") (part "0603WAF470KT5E"))
    )
    (comp (ref "R23")
      (value "4.7Ω")
      (footprint "easyedapro:R0603")
      (description "电阻类型:厚膜电阻;阻值:4.7Ω;精度:±1%;功率:100mW;最大工作电压:75V;温度系数:±400ppm/°C;")
      (fields
        (field (name "Manufacturer Part") "0603WAF470KT5E")
        (field (name "Manufacturer") "UNI-ROYAL(厚声)")
      )
      (libsource (lib "easyedapro") (part "0603WAF470KT5E"))
    )
    (comp (ref "R24")
      (value "4.7Ω")
      (footprint "easyedapro:R0603")
      (description "电阻类型:厚膜电阻;阻值:4.7Ω;精度:±1%;功率:100mW;最大工作电压:75V;温度系数:±400ppm/°C;")
      (fields
        (field (name "Manufacturer Part") "0603WAF470KT5E")
        (field (name "Manufacturer") "UNI-ROYAL(厚声)")
      )
      (libsource (lib "easyedapro") (part "0603WAF470KT5E"))
    )
    (comp (ref "R25")
      (value "4.7Ω")
      (footprint "easyedapro:R0603")
      (description "电阻类型:厚膜电阻;阻值:4.7Ω;精度:±1%;功率:100mW;最大工作电压:75V;温度系数:±400ppm/°C;")
      (fields
        (field (name "Manufacturer Part") "0603WAF470KT5E")
        (field (name "Manufacturer") "UNI-ROYAL(厚声)")
      )
      (libsource (lib "easyedapro") (part "0603WAF470KT5E"))
    )
    (comp (ref "R101")
      (value "100Ω")
      (footprint "easyedapro:R0603")
      (description "电阻类型:厚膜电阻;阻值:100Ω;精度:±1%;功率:100mW;最大工作电压:75V;温度系数:±100ppm/°C;")
      (fields (field (name "Manufacturer Part") "RC0603FR-07100RL") (field (name "Manufacturer") "YAGEO(国巨)"))
      (libsource (lib "easyedapro") (part "RC0603FR-07100RL"))
    )
    (comp (ref "U1")
      (value "CH32V203C8T6")
      (footprint "easyedapro:LQFP-48_L7.0-W7.0-P0.50-LS9.0-BL")
      (description "CPU内核:RISC-V;程序存储容量:64KB;RAM总容量:20KB;GPIO端口数量:-;工作电压范围:-;CPU最大主频:144MHz;程序存储器类型:FLASH;")
      (fields (field (name "Manufacturer") "WCH(南京沁恒)"))
      (libsource (lib "easyedapro") (part "CH32V203C8T6"))
    )
    (comp (ref "U3")
      (value "SY8205FCC")
      (footprint "easyedapro:SOIC-8_L5.0-W4.0-P1.27-LS6.0-BL-EP2.0")
      (description "功能类型:降压型;输入电压:-;输出电流(最大值):-;")
      (fields (field (name "Manufacturer") "silergy(矽力杰)"))
      (libsource (lib "easyedapro") (part "SY8205FCC"))
    )
    (comp (ref "U4")
      (value "RT9013-33GB")
      (footprint "easyedapro:SOT-23-5_L2.9-W1.6-P0.95-LS2.8-BR")
      (fields (field (name "Manufacturer") "TECH PUBLIC(台舟)"))
      (libsource (lib "easyedapro") (part "RT9013-33GB_C19268157"))
    )
    (comp (ref "U5")
      (value "FD6288Q")
      (footprint "easyedapro:QFN-24_L4.0-W4.0-P0.50-BL-EP2.6")
      (fields (field (name "Manufacturer") "Fortior Tech(峰岹)"))
      (libsource (lib "easyedapro") (part "FD6288Q_C328453"))
    )
    (comp (ref "C37")
      (value "100nF")
      (footprint "easyedapro:C0603")
      (description "容值:100nF;精度:±10%;额定电压:50V;材质(温度系数):X7R;")
      (fields
        (field (name "Manufacturer Part") "CGA0603X7R104K500JT")
        (field (name "Manufacturer") "HRE(芯声)")
      )
      (libsource (lib "easyedapro") (part "CGA0603X7R104K500JT"))
    )
    (comp (ref "C38")
      (value "100nF")
      (footprint "easyedapro:C0603")
      (description "容值:100nF;精度:±10%;额定电压:50V;材质(温度系数):X7R;")
      (fields
        (field (name "Manufacturer Part") "CGA0603X7R104K500JT")
        (field (name "Manufacturer") "HRE(芯声)")
      )
      (libsource (lib "easyedapro") (part "CGA0603X7R104K500JT"))
    )
    (comp (ref "C39")
      (value "100nF")
      (footprint "easyedapro:C0603")
      (description "容值:100nF;精度:±10%;额定电压:50V;材质(温度系数):X7R;")
      (fields
        (field (name "Manufacturer Part") "CGA0603X7R104K500JT")
        (field (name "Manufacturer") "HRE(芯声)")
      )
      (libsource (lib "easyedapro") (part "CGA0603X7R104K500JT"))
    )
    (comp (ref "C40")
      (value "100nF")
      (footprint "easyedapro:C0402")
      (description "容值:100nF;精度:±10%;额定电压:50V;温度系数:X7R;")
      (fields
        (field (name "Manufacturer Part") "CL05B104KB54PNC")
        (field (name "Manufacturer") "SAMSUNG(三星)")
      )
      (libsource (lib "easyedapro") (part "C 0402"))
    )
    (comp (ref "C41")
      (value "100nF")
      (footprint "easyedapro:C0603")
      (description "容值:100nF;精度:±10%;额定电压:50V;材质(温度系数):X7R;")
      (fields
        (field (name "Manufacturer Part") "CGA0603X7R104K500JT")
        (field (name "Manufacturer") "HRE(芯声)")
      )
      (libsource (lib "easyedapro") (part "CGA0603X7R104K500JT"))
    )
    (comp (ref "C42")
      (value "100nF")
      (footprint "easyedapro:C0603")
      (description "容值:100nF;精度:±10%;额定电压:50V;材质(温度系数):X7R;")
      (fields
        (field (name "Manufacturer Part") "CGA0603X7R104K500JT")
        (field (name "Manufacturer") "HRE(芯声)")
      )
      (libsource (lib "easyedapro") (part "CGA0603X7R104K500JT"))
    )
    (comp (ref "C43")
      (value "100nF")
      (footprint "easyedapro:C0603")
      (description "容值:100nF;精度:±10%;额定电压:50V;材质(温度系数):X7R;")
      (fields
        (field (name "Manufacturer Part") "CGA0603X7R104K500JT")
        (field (name "Manufacturer") "HRE(芯声)")
      )
      (libsource (lib "easyedapro") (part "CGA0603X7R104K500JT"))
    )
    (comp (ref "C44")
      (value "100nF")
      (footprint "easyedapro:C0603")
      (description "容值:100nF;精度:±10%;额定电压:50V;材质(温度系数):X7R;")
      (fields
        (field (name "Manufacturer Part") "CGA0603X7R104K500JT")
        (field (name "Manufacturer") "HRE(芯声)")
      )
      (libsource (lib "easyedapro") (part "CGA0603X7R104K500JT"))
    )
    (comp (ref "C45")
      (value "100nF")
      (footprint "easyedapro:C0603")
      (description "容值:100nF;精度:±10%;额定电压:50V;材质(温度系数):X7R;")
      (fields
        (field (name "Manufacturer Part") "CGA0603X7R104K500JT")
        (field (name "Manufacturer") "HRE(芯声)")
      )
      (libsource (lib "easyedapro") (part "CGA0603X7R104K500JT"))
    )
    (comp (ref "C61")
      (value "10uF")
      (footprint "easyedapro:C0603")
      (description "容值:10uF;精度:±10%;额定电压:10V;材质(温度系数):X5R;")
      (fields
        (field (name "Manufacturer Part") "CL10A106KP8NNNC")
        (field (name "Manufacturer") "SAMSUNG(三星)")
      )
      (libsource (lib "easyedapro") (part "CL10A106KP8NNNC"))
    )
    (comp (ref "C62")
      (value "10uF")
      (footprint "easyedapro:C0603")
      (description "容值:10uF;精度:±10%;额定电压:10V;材质(温度系数):X5R;")
      (fields
        (field (name "Manufacturer Part") "CL10A106KP8NNNC")
        (field (name "Manufacturer") "SAMSUNG(三星)")
      )
      (libsource (lib "easyedapro") (part "CL10A106KP8NNNC"))
    )
    (comp (ref "C63")
      (value "4.7uF")
      (footprint "easyedapro:C0603")
      (description "容值:4.7uF;精度:±10%;额定电压:16V;材质(温度系数):X5R;")
      (fields
        (field (name "Manufacturer Part") "CL10A475KO8NNNC")
        (field (name "Manufacturer") "SAMSUNG(三星)")
      )
      (libsource (lib "easyedapro") (part "CL10A475KO8NNNC"))
    )
    (comp (ref "C64")
      (value "4.7uF")
      (footprint "easyedapro:C0603")
      (description "容值:4.7uF;精度:±10%;额定电压:16V;材质(温度系数):X5R;")
      (fields
        (field (name "Manufacturer Part") "CL10A475KO8NNNC")
        (field (name "Manufacturer") "SAMSUNG(三星)")
      )
      (libsource (lib "easyedapro") (part "CL10A475KO8NNNC"))
    )
    (comp (ref "C65")
      (value "4.7uF")
      (footprint "easyedapro:C0603")
      (description "容值:4.7uF;精度:±10%;额定电压:16V;材质(温度系数):X5R;")
      (fields
        (field (name "Manufacturer Part") "CL10A475KO8NNNC")
        (field (name "Manufacturer") "SAMSUNG(三星)")
      )
      (libsource (lib "easyedapro") (part "CL10A475KO8NNNC"))
    )
    (comp (ref "C66")
      (value "22uF")
      (footprint "easyedapro:C0805")
      (description "容值:22uF;精度:±20%;额定电压:25V;材质(温度系数):X5R;")
      (fields
        (field (name "Manufacturer Part") "CL21A226MAQNNNE")
        (field (name "Manufacturer") "SAMSUNG(三星)")
      )
      (libsource (lib "easyedapro") (part "CL21A226MAQNNNE"))
    )
    (comp (ref "C127")
      (value "22uF")
      (footprint "easyedapro:C0805")
      (description "容值:22uF;精度:±20%;额定电压:35V;材质(温度系数):X5R;")
      (fields
        (field (name "Manufacturer Part") "CGA0805X5R226M350MT")
        (field (name "Manufacturer") "HRE(芯声)")
      )
      (libsource (lib "easyedapro") (part "CGA0805X5R226M350MT"))
    )
    (comp (ref "C128")
      (value "22uF")
      (footprint "easyedapro:C0805")
      (description "容值:22uF;精度:±20%;额定电压:35V;材质(温度系数):X5R;")
      (fields
        (field (name "Manufacturer Part") "CGA0805X5R226M350MT")
        (field (name "Manufacturer") "HRE(芯声)")
      )
      (libsource (lib "easyedapro") (part "CGA0805X5R226M350MT"))
    )
    (comp (ref "C129")
      (value "22uF")
      (footprint "easyedapro:C0805")
      (description "容值:22uF;精度:±20%;额定电压:35V;材质(温度系数):X5R;")
      (fields
        (field (name "Manufacturer Part") "CGA0805X5R226M350MT")
        (field (name "Manufacturer") "HRE(芯声)")
      )
      (libsource (lib "easyedapro") (part "CGA0805X5R226M350MT"))
    )
    (comp (ref "C130")
      (value "22uF")
      (footprint "easyedapro:C0805")
      (description "容值:22uF;精度:±20%;额定电压:35V;材质(温度系数):X5R;")
      (fields
        (field (name "Manufacturer Part") "CGA0805X5R226M350MT")
        (field (name "Manufacturer") "HRE(芯声)")
      )
      (libsource (lib "easyedapro") (part "CGA0805X5R226M350MT"))
    )
    (comp (ref "C131")
      (value "22uF")
      (footprint "easyedapro:C0805")
      (description "容值:22uF;精度:±20%;额定电压:35V;材质(温度系数):X5R;")
      (fields
        (field (name "Manufacturer Part") "CGA0805X5R226M350MT")
        (field (name "Manufacturer") "HRE(芯声)")
      )
      (libsource (lib "easyedapro") (part "CGA0805X5R226M350MT"))
    )
    (comp (ref "C132")
      (value "22uF")
      (footprint "easyedapro:C0805")
      (description "容值:22uF;精度:±20%;额定电压:35V;材质(温度系数):X5R;")
      (fields
        (field (name "Manufacturer Part") "CGA0805X5R226M350MT")
        (field (name "Manufacturer") "HRE(芯声)")
      )
      (libsource (lib "easyedapro") (part "CGA0805X5R226M350MT"))
    )
    (comp (ref "D5")
      (value "B5819WS")
      (footprint "easyedapro:SOD-323_L1.7-W1.3-LS2.5-FD")
      (description "二极管配置:独立式;正向压降(Vf):600mV@1.0A;直流反向耐压(Vr):40V;平均整流电流(Io):1A;")
      (fields (field (name "Manufacturer") "宏迦橙"))
      (libsource (lib "easyedapro") (part "B5819WS_C7420331"))
    )
    (comp (ref "D6")
      (value "B5819WS")
      (footprint "easyedapro:SOD-323_L1.7-W1.3-LS2.5-FD")
      (description "二极管配置:独立式;正向压降(Vf):600mV@1.0A;直流反向耐压(Vr):40V;平均整流电流(Io):1A;")
      (fields (field (name "Manufacturer") "宏迦橙"))
      (libsource (lib "easyedapro") (part "B5819WS_C7420331"))
    )
    (comp (ref "D7")
      (value "B5819WS")
      (footprint "easyedapro:SOD-323_L1.7-W1.3-LS2.5-FD")
      (description "二极管配置:独立式;正向压降(Vf):600mV@1.0A;直流反向耐压(Vr):40V;平均整流电流(Io):1A;")
      (fields (field (name "Manufacturer") "宏迦橙"))
      (libsource (lib "easyedapro") (part "B5819WS_C7420331"))
    )
    (comp (ref "D8")
      (value "B5819WS")
      (footprint "easyedapro:SOD-323_L1.7-W1.3-LS2.5-FD")
      (description "二极管配置:独立式;正向压降(Vf):600mV@1.0A;直流反向耐压(Vr):40V;平均整流电流(Io):1A;")
      (fields (field (name "Manufacturer") "宏迦橙"))
      (libsource (lib "easyedapro") (part "B5819WS_C7420331"))
    )
    (comp (ref "L4")
      (value "CBG160808U000T")
      (footprint "easyedapro:L0603")
      (description "标称阻抗@测试频率:0Ω@100MHz;直流电阻(RDC):100mΩ;")
      (fields (field (name "Manufacturer") "FH(风华)"))
      (libsource (lib "easyedapro") (part "CBG160808U000T"))
    )
    (comp (ref "L5")
      (value "CBG160808U000T")
      (footprint "easyedapro:L0603")
      (description "标称阻抗@测试频率:0Ω@100MHz;直流电阻(RDC):100mΩ;")
      (fields (field (name "Manufacturer") "FH(风华)"))
      (libsource (lib "easyedapro") (part "CBG160808U000T"))
    )
    (comp (ref "LED3")
      (value "XL-1608UGC-04")
      (footprint "easyedapro:LED0603-RD_GREEN")
      (fields (field (name "Manufacturer") "XINGLIGHT(成兴光)"))
      (libsource (lib "easyedapro") (part "XL-1608UGC-04"))
    )
    (comp (ref "LED4")
      (value "XL-1608UGC-04")
      (footprint "easyedapro:LED0603-RD_GREEN")
      (fields (field (name "Manufacturer") "XINGLIGHT(成兴光)"))
      (libsource (lib "easyedapro") (part "XL-1608UGC-04"))
    )
    (comp (ref "Q7")
      (value "AON6354")
      (footprint "easyedapro:DFN-8_L5.2-W6.1-P1.27-BL-EP")
      (fields (field (name "Manufacturer") "AOS"))
      (libsource (lib "easyedapro") (part "AON6354"))
    )
    (comp (ref "Q8")
      (value "AON6354")
      (footprint "easyedapro:DFN-8_L5.2-W6.1-P1.27-BL-EP")
      (fields (field (name "Manufacturer") "AOS"))
      (libsource (lib "easyedapro") (part "AON6354"))
    )
    (comp (ref "Q9")
      (value "AON6354")
      (footprint "easyedapro:DFN-8_L5.2-W6.1-P1.27-BL-EP")
      (fields (field (name "Manufacturer") "AOS"))
      (libsource (lib "easyedapro") (part "AON6354"))
    )
    (comp (ref "Q10")
      (value "AON6354")
      (footprint "easyedapro:DFN-8_L5.2-W6.1-P1.27-BL-EP")
      (fields (field (name "Manufacturer") "AOS"))
      (libsource (lib "easyedapro") (part "AON6354"))
    )
    (comp (ref "Q11")
      (value "AON6354")
      (footprint "easyedapro:DFN-8_L5.2-W6.1-P1.27-BL-EP")
      (fields (field (name "Manufacturer") "AOS"))
      (libsource (lib "easyedapro") (part "AON6354"))
    )
    (comp (ref "Q12")
      (value "AON6354")
      (footprint "easyedapro:DFN-8_L5.2-W6.1-P1.27-BL-EP")
      (fields (field (name "Manufacturer") "AOS"))
      (libsource (lib "easyedapro") (part "AON6354"))
    )
    (comp (ref "R26")
      (value "10kΩ")
      (footprint "easyedapro:R0603")
      (description "电阻类型:厚膜电阻;阻值:10kΩ;精度:±5%;功率:100mW;最大工作电压:75V;温度系数:±100ppm/°C;")
      (fields (field (name "Manufacturer Part") "FRC0603J103TS") (field (name "Manufacturer") "FOJAN(富捷)"))
      (libsource (lib "easyedapro") (part "FRC0603J103TS"))
    )
    (comp (ref "R27")
      (value "10kΩ")
      (footprint "easyedapro:R0603")
      (description "电阻类型:厚膜电阻;阻值:10kΩ;精度:±5%;功率:100mW;最大工作电压:75V;温度系数:±100ppm/°C;")
      (fields (field (name "Manufacturer Part") "FRC0603J103TS") (field (name "Manufacturer") "FOJAN(富捷)"))
      (libsource (lib "easyedapro") (part "FRC0603J103TS"))
    )
    (comp (ref "R28")
      (value "10kΩ")
      (footprint "easyedapro:R0603")
      (description "电阻类型:厚膜电阻;阻值:10kΩ;精度:±5%;功率:100mW;最大工作电压:75V;温度系数:±100ppm/°C;")
      (fields (field (name "Manufacturer Part") "FRC0603J103TS") (field (name "Manufacturer") "FOJAN(富捷)"))
      (libsource (lib "easyedapro") (part "FRC0603J103TS"))
    )
    (comp (ref "R29")
      (value "1kΩ")
      (footprint "easyedapro:R0603")
      (description "电阻类型:厚膜电阻;阻值:1kΩ;精度:±1%;功率:100mW;最大工作电压:75V;温度系数:±100ppm/°C;")
      (fields (field (name "Manufacturer Part") "RC0603FR-071KL") (field (name "Manufacturer") "YAGEO(国巨)"))
      (libsource (lib "easyedapro") (part "RC0603FR-071KL"))
    )
    (comp (ref "R30")
      (value "1kΩ")
      (footprint "easyedapro:R0603")
      (description "电阻类型:厚膜电阻;阻值:1kΩ;精度:±1%;功率:100mW;最大工作电压:75V;温度系数:±100ppm/°C;")
      (fields (field (name "Manufacturer Part") "RC0603FR-071KL") (field (name "Manufacturer") "YAGEO(国巨)"))
      (libsource (lib "easyedapro") (part "RC0603FR-071KL"))
    )
    (comp (ref "R31")
      (value "10kΩ")
      (footprint "easyedapro:R0603")
      (description "电阻类型:厚膜电阻;阻值:10kΩ;精度:±5%;功率:100mW;最大工作电压:75V;温度系数:±100ppm/°C;")
      (fields (field (name "Manufacturer Part") "FRC0603J103TS") (field (name "Manufacturer") "FOJAN(富捷)"))
      (libsource (lib "easyedapro") (part "FRC0603J103TS"))
    )
    (comp (ref "R32")
      (value "1kΩ")
      (footprint "easyedapro:R0603")
      (description "电阻类型:厚膜电阻;阻值:1kΩ;精度:±1%;功率:100mW;最大工作电压:75V;温度系数:±100ppm/°C;")
      (fields (field (name "Manufacturer Part") "RC0603FR-071KL") (field (name "Manufacturer") "YAGEO(国巨)"))
      (libsource (lib "easyedapro") (part "RC0603FR-071KL"))
    )
    (comp (ref "R33")
      (value "1kΩ")
      (footprint "easyedapro:R0603")
      (description "电阻类型:厚膜电阻;阻值:1kΩ;精度:±1%;功率:100mW;最大工作电压:75V;温度系数:±100ppm/°C;")
      (fields (field (name "Manufacturer Part") "RC0603FR-071KL") (field (name "Manufacturer") "YAGEO(国巨)"))
      (libsource (lib "easyedapro") (part "RC0603FR-071KL"))
    )
    (comp (ref "R34")
      (value "10kΩ")
      (footprint "easyedapro:R0603")
      (description "电阻类型:厚膜电阻;阻值:10kΩ;精度:±5%;功率:100mW;最大工作电压:75V;温度系数:±100ppm/°C;")
      (fields (field (name "Manufacturer Part") "FRC0603J103TS") (field (name "Manufacturer") "FOJAN(富捷)"))
      (libsource (lib "easyedapro") (part "FRC0603J103TS"))
    )
    (comp (ref "R35")
      (value "1kΩ")
      (footprint "easyedapro:R0603")
      (description "电阻类型:厚膜电阻;阻值:1kΩ;精度:±1%;功率:100mW;最大工作电压:75V;温度系数:±100ppm/°C;")
      (fields (field (name "Manufacturer Part") "RC0603FR-071KL") (field (name "Manufacturer") "YAGEO(国巨)"))
      (libsource (lib "easyedapro") (part "RC0603FR-071KL"))
    )
    (comp (ref "R36")
      (value "1kΩ")
      (footprint "easyedapro:R0603")
      (description "电阻类型:厚膜电阻;阻值:1kΩ;精度:±1%;功率:100mW;最大工作电压:75V;温度系数:±100ppm/°C;")
      (fields (field (name "Manufacturer Part") "RC0603FR-071KL") (field (name "Manufacturer") "YAGEO(国巨)"))
      (libsource (lib "easyedapro") (part "RC0603FR-071KL"))
    )
    (comp (ref "R37")
      (value "47kΩ")
      (footprint "easyedapro:R0603")
      (description "电阻类型:厚膜电阻;阻值:47kΩ;精度:±1%;功率:100mW;最大工作电压:75V;温度系数:±100ppm/°C;")
      (fields
        (field (name "Manufacturer Part") "0603WAF4702T5E")
        (field (name "Manufacturer") "UNI-ROYAL(厚声)")
      )
      (libsource (lib "easyedapro") (part "0603WAF4702T5E"))
    )
    (comp (ref "R38")
      (value "10kΩ")
      (footprint "easyedapro:R0603")
      (description "电阻类型:厚膜电阻;阻值:10kΩ;精度:±5%;功率:100mW;最大工作电压:75V;温度系数:±100ppm/°C;")
      (fields (field (name "Manufacturer Part") "FRC0603J103TS") (field (name "Manufacturer") "FOJAN(富捷)"))
      (libsource (lib "easyedapro") (part "FRC0603J103TS"))
    )
    (comp (ref "R39")
      (value "1kΩ")
      (footprint "easyedapro:R0603")
      (description "电阻类型:厚膜电阻;阻值:1kΩ;精度:±1%;功率:100mW;最大工作电压:75V;温度系数:±100ppm/°C;")
      (fields (field (name "Manufacturer Part") "RC0603FR-071KL") (field (name "Manufacturer") "YAGEO(国巨)"))
      (libsource (lib "easyedapro") (part "RC0603FR-071KL"))
    )
    (comp (ref "R40")
      (value "2.7kΩ")
      (footprint "easyedapro:R0603")
      (description "电阻类型:厚膜电阻;阻值:2.7kΩ;精度:±1%;功率:100mW;最大工作电压:75V;温度系数:±100ppm/°C;")
      (fields
        (field (name "Manufacturer Part") "0603WAF2701T5E")
        (field (name "Manufacturer") "UNI-ROYAL(厚声)")
      )
      (libsource (lib "easyedapro") (part "0603WAF2701T5E"))
    )
    (comp (ref "R45")
      (value "4.7Ω")
      (footprint "easyedapro:R0603")
      (description "电阻类型:厚膜电阻;阻值:4.7Ω;精度:±1%;功率:100mW;最大工作电压:75V;温度系数:±400ppm/°C;")
      (fields
        (field (name "Manufacturer Part") "0603WAF470KT5E")
        (field (name "Manufacturer") "UNI-ROYAL(厚声)")
      )
      (libsource (lib "easyedapro") (part "0603WAF470KT5E"))
    )
    (comp (ref "R46")
      (value "4.7Ω")
      (footprint "easyedapro:R0603")
      (description "电阻类型:厚膜电阻;阻值:4.7Ω;精度:±1%;功率:100mW;最大工作电压:75V;温度系数:±400ppm/°C;")
      (fields
        (field (name "Manufacturer Part") "0603WAF470KT5E")
        (field (name "Manufacturer") "UNI-ROYAL(厚声)")
      )
      (libsource (lib "easyedapro") (part "0603WAF470KT5E"))
    )
    (comp (ref "R47")
      (value "4.7Ω")
      (footprint "easyedapro:R0603")
      (description "电阻类型:厚膜电阻;阻值:4.7Ω;精度:±1%;功率:100mW;最大工作电压:75V;温度系数:±400ppm/°C;")
      (fields
        (field (name "Manufacturer Part") "0603WAF470KT5E")
        (field (name "Manufacturer") "UNI-ROYAL(厚声)")
      )
      (libsource (lib "easyedapro") (part "0603WAF470KT5E"))
    )
    (comp (ref "R48")
      (value "4.7Ω")
      (footprint "easyedapro:R0603")
      (description "电阻类型:厚膜电阻;阻值:4.7Ω;精度:±1%;功率:100mW;最大工作电压:75V;温度系数:±400ppm/°C;")
      (fields
        (field (name "Manufacturer Part") "0603WAF470KT5E")
        (field (name "Manufacturer") "UNI-ROYAL(厚声)")
      )
      (libsource (lib "easyedapro") (part "0603WAF470KT5E"))
    )
    (comp (ref "R49")
      (value "4.7Ω")
      (footprint "easyedapro:R0603")
      (description "电阻类型:厚膜电阻;阻值:4.7Ω;精度:±1%;功率:100mW;最大工作电压:75V;温度系数:±400ppm/°C;")
      (fields
        (field (name "Manufacturer Part") "0603WAF470KT5E")
        (field (name "Manufacturer") "UNI-ROYAL(厚声)")
      )
      (libsource (lib "easyedapro") (part "0603WAF470KT5E"))
    )
    (comp (ref "R50")
      (value "4.7Ω")
      (footprint "easyedapro:R0603")
      (description "电阻类型:厚膜电阻;阻值:4.7Ω;精度:±1%;功率:100mW;最大工作电压:75V;温度系数:±400ppm/°C;")
      (fields
        (field (name "Manufacturer Part") "0603WAF470KT5E")
        (field (name "Manufacturer") "UNI-ROYAL(厚声)")
      )
      (libsource (lib "easyedapro") (part "0603WAF470KT5E"))
    )
    (comp (ref "R102")
      (value "100Ω")
      (footprint "easyedapro:R0603")
      (description "电阻类型:厚膜电阻;阻值:100Ω;精度:±1%;功率:100mW;最大工作电压:75V;温度系数:±100ppm/°C;")
      (fields (field (name "Manufacturer Part") "RC0603FR-07100RL") (field (name "Manufacturer") "YAGEO(国巨)"))
      (libsource (lib "easyedapro") (part "RC0603FR-07100RL"))
    )
    (comp (ref "U6")
      (value "CH32V203C8T6")
      (footprint "easyedapro:LQFP-48_L7.0-W7.0-P0.50-LS9.0-BL")
      (description "CPU内核:RISC-V;程序存储容量:64KB;RAM总容量:20KB;GPIO端口数量:-;工作电压范围:-;CPU最大主频:144MHz;程序存储器类型:FLASH;")
      (fields (field (name "Manufacturer") "WCH(南京沁恒)"))
      (libsource (lib "easyedapro") (part "CH32V203C8T6"))
    )
    (comp (ref "U8")
      (value "RT9013-33GB")
      (footprint "easyedapro:SOT-23-5_L2.9-W1.6-P0.95-LS2.8-BR")
      (fields (field (name "Manufacturer") "TECH PUBLIC(台舟)"))
      (libsource (lib "easyedapro") (part "RT9013-33GB_C19268157"))
    )
    (comp (ref "U9")
      (value "FD6288Q")
      (footprint "easyedapro:QFN-24_L4.0-W4.0-P0.50-BL-EP2.6")
      (fields (field (name "Manufacturer") "Fortior Tech(峰岹)"))
      (libsource (lib "easyedapro") (part "FD6288Q_C328453"))
    )
    (comp (ref "C67")
      (value "100nF")
      (footprint "easyedapro:C0603")
      (description "容值:100nF;精度:±10%;额定电压:50V;材质(温度系数):X7R;")
      (fields
        (field (name "Manufacturer Part") "CGA0603X7R104K500JT")
        (field (name "Manufacturer") "HRE(芯声)")
      )
      (libsource (lib "easyedapro") (part "CGA0603X7R104K500JT"))
    )
    (comp (ref "C68")
      (value "100nF")
      (footprint "easyedapro:C0603")
      (description "容值:100nF;精度:±10%;额定电压:50V;材质(温度系数):X7R;")
      (fields
        (field (name "Manufacturer Part") "CGA0603X7R104K500JT")
        (field (name "Manufacturer") "HRE(芯声)")
      )
      (libsource (lib "easyedapro") (part "CGA0603X7R104K500JT"))
    )
    (comp (ref "C69")
      (value "100nF")
      (footprint "easyedapro:C0603")
      (description "容值:100nF;精度:±10%;额定电压:50V;材质(温度系数):X7R;")
      (fields
        (field (name "Manufacturer Part") "CGA0603X7R104K500JT")
        (field (name "Manufacturer") "HRE(芯声)")
      )
      (libsource (lib "easyedapro") (part "CGA0603X7R104K500JT"))
    )
    (comp (ref "C70")
      (value "100nF")
      (footprint "easyedapro:C0402")
      (description "容值:100nF;精度:±10%;额定电压:50V;温度系数:X7R;")
      (fields
        (field (name "Manufacturer Part") "CL05B104KB54PNC")
        (field (name "Manufacturer") "SAMSUNG(三星)")
      )
      (libsource (lib "easyedapro") (part "C 0402"))
    )
    (comp (ref "C71")
      (value "100nF")
      (footprint "easyedapro:C0603")
      (description "容值:100nF;精度:±10%;额定电压:50V;材质(温度系数):X7R;")
      (fields
        (field (name "Manufacturer Part") "CGA0603X7R104K500JT")
        (field (name "Manufacturer") "HRE(芯声)")
      )
      (libsource (lib "easyedapro") (part "CGA0603X7R104K500JT"))
    )
    (comp (ref "C72")
      (value "100nF")
      (footprint "easyedapro:C0603")
      (description "容值:100nF;精度:±10%;额定电压:50V;材质(温度系数):X7R;")
      (fields
        (field (name "Manufacturer Part") "CGA0603X7R104K500JT")
        (field (name "Manufacturer") "HRE(芯声)")
      )
      (libsource (lib "easyedapro") (part "CGA0603X7R104K500JT"))
    )
    (comp (ref "C73")
      (value "100nF")
      (footprint "easyedapro:C0603")
      (description "容值:100nF;精度:±10%;额定电压:50V;材质(温度系数):X7R;")
      (fields
        (field (name "Manufacturer Part") "CGA0603X7R104K500JT")
        (field (name "Manufacturer") "HRE(芯声)")
      )
      (libsource (lib "easyedapro") (part "CGA0603X7R104K500JT"))
    )
    (comp (ref "C74")
      (value "100nF")
      (footprint "easyedapro:C0603")
      (description "容值:100nF;精度:±10%;额定电压:50V;材质(温度系数):X7R;")
      (fields
        (field (name "Manufacturer Part") "CGA0603X7R104K500JT")
        (field (name "Manufacturer") "HRE(芯声)")
      )
      (libsource (lib "easyedapro") (part "CGA0603X7R104K500JT"))
    )
    (comp (ref "C75")
      (value "100nF")
      (footprint "easyedapro:C0603")
      (description "容值:100nF;精度:±10%;额定电压:50V;材质(温度系数):X7R;")
      (fields
        (field (name "Manufacturer Part") "CGA0603X7R104K500JT")
        (field (name "Manufacturer") "HRE(芯声)")
      )
      (libsource (lib "easyedapro") (part "CGA0603X7R104K500JT"))
    )
    (comp (ref "C76")
      (value "22uF")
      (footprint "easyedapro:C0805")
      (description "容值:22uF;精度:±20%;额定电压:35V;材质(温度系数):X5R;")
      (fields
        (field (name "Manufacturer Part") "CGA0805X5R226M350MT")
        (field (name "Manufacturer") "HRE(芯声)")
      )
      (libsource (lib "easyedapro") (part "CGA0805X5R226M350MT"))
    )
    (comp (ref "C77")
      (value "22uF")
      (footprint "easyedapro:C0805")
      (description "容值:22uF;精度:±20%;额定电压:35V;材质(温度系数):X5R;")
      (fields
        (field (name "Manufacturer Part") "CGA0805X5R226M350MT")
        (field (name "Manufacturer") "HRE(芯声)")
      )
      (libsource (lib "easyedapro") (part "CGA0805X5R226M350MT"))
    )
    (comp (ref "C78")
      (value "22uF")
      (footprint "easyedapro:C0805")
      (description "容值:22uF;精度:±20%;额定电压:35V;材质(温度系数):X5R;")
      (fields
        (field (name "Manufacturer Part") "CGA0805X5R226M350MT")
        (field (name "Manufacturer") "HRE(芯声)")
      )
      (libsource (lib "easyedapro") (part "CGA0805X5R226M350MT"))
    )
    (comp (ref "C79")
      (value "22uF")
      (footprint "easyedapro:C0805")
      (description "容值:22uF;精度:±20%;额定电压:35V;材质(温度系数):X5R;")
      (fields
        (field (name "Manufacturer Part") "CGA0805X5R226M350MT")
        (field (name "Manufacturer") "HRE(芯声)")
      )
      (libsource (lib "easyedapro") (part "CGA0805X5R226M350MT"))
    )
    (comp (ref "C80")
      (value "22uF")
      (footprint "easyedapro:C0805")
      (description "容值:22uF;精度:±20%;额定电压:35V;材质(温度系数):X5R;")
      (fields
        (field (name "Manufacturer Part") "CGA0805X5R226M350MT")
        (field (name "Manufacturer") "HRE(芯声)")
      )
      (libsource (lib "easyedapro") (part "CGA0805X5R226M350MT"))
    )
    (comp (ref "C81")
      (value "22uF")
      (footprint "easyedapro:C0805")
      (description "容值:22uF;精度:±20%;额定电压:35V;材质(温度系数):X5R;")
      (fields
        (field (name "Manufacturer Part") "CGA0805X5R226M350MT")
        (field (name "Manufacturer") "HRE(芯声)")
      )
      (libsource (lib "easyedapro") (part "CGA0805X5R226M350MT"))
    )
    (comp (ref "C82")
      (value "470uF")
      (footprint "easyedapro:CAP-TH_BD8.0-P3.50-D0.6-FD")
      (description "容值:470uF;精度:±20%;额定电压:25V;")
      (fields
        (field (name "Manufacturer Part") "KM477M025F12RR0VH2FP0")
        (field (name "Manufacturer") "CX(承兴)")
      )
      (libsource (lib "easyedapro") (part "470uF 25V 8*12"))
    )
    (comp (ref "C83")
      (value "100nF")
      (footprint "easyedapro:C0603")
      (description "容值:100nF;精度:±10%;额定电压:50V;材质(温度系数):X7R;")
      (fields
        (field (name "Manufacturer Part") "CGA0603X7R104K500JT")
        (field (name "Manufacturer") "HRE(芯声)")
      )
      (libsource (lib "easyedapro") (part "CGA0603X7R104K500JT"))
    )
    (comp (ref "C84")
      (value "10uF")
      (footprint "easyedapro:C0805")
      (description "容值:10uF;精度:±10%;额定电压:50V;材质(温度系数):X5R;")
      (fields
        (field (name "Manufacturer Part") "CL21A106KBYQNNE")
        (field (name "Manufacturer") "SAMSUNG(三星)")
      )
      (libsource (lib "easyedapro") (part "CL21A106KBYQNNE"))
    )
    (comp (ref "C85")
      (value "100pF")
      (footprint "easyedapro:C0603")
      (description "容值:100pF;精度:±5%;额定电压:50V;材质(温度系数):NP0;")
      (fields
        (field (name "Manufacturer Part") "CC0603JRNPO9BN101")
        (field (name "Manufacturer") "YAGEO(国巨)")
      )
      (libsource (lib "easyedapro") (part "CC0603JRNPO9BN101"))
    )
    (comp (ref "C86")
      (value "10uF")
      (footprint "easyedapro:C0603")
      (description "容值:10uF;精度:±20%;额定电压:25V;材质(温度系数):X5R;")
      (fields
        (field (name "Manufacturer Part") "CL10A106MA8NRNC")
        (field (name "Manufacturer") "SAMSUNG(三星)")
      )
      (libsource (lib "easyedapro") (part "CL10A106MA8NRNC"))
    )
    (comp (ref "C87")
      (value "10uF")
      (footprint "easyedapro:C0603")
      (description "容值:10uF;精度:±20%;额定电压:25V;材质(温度系数):X5R;")
      (fields
        (field (name "Manufacturer Part") "CL10A106MA8NRNC")
        (field (name "Manufacturer") "SAMSUNG(三星)")
      )
      (libsource (lib "easyedapro") (part "CL10A106MA8NRNC"))
    )
    (comp (ref "C88")
      (value "100nF")
      (footprint "easyedapro:C0603")
      (description "容值:100nF;精度:±10%;额定电压:50V;材质(温度系数):X7R;")
      (fields
        (field (name "Manufacturer Part") "CGA0603X7R104K500JT")
        (field (name "Manufacturer") "HRE(芯声)")
      )
      (libsource (lib "easyedapro") (part "CGA0603X7R104K500JT"))
    )
    (comp (ref "C89")
      (value "10uF")
      (footprint "easyedapro:C0805")
      (description "容值:10uF;精度:±10%;额定电压:50V;材质(温度系数):X5R;")
      (fields
        (field (name "Manufacturer Part") "CL21A106KBYQNNE")
        (field (name "Manufacturer") "SAMSUNG(三星)")
      )
      (libsource (lib "easyedapro") (part "CL21A106KBYQNNE"))
    )
    (comp (ref "C90")
      (value "220pF")
      (footprint "easyedapro:C0603")
      (description "容值:220pF;精度:±10%;额定电压:50V;材质(温度系数):X7R;")
      (fields
        (field (name "Manufacturer Part") "CL10B221KB8NNNC")
        (field (name "Manufacturer") "SAMSUNG(三星)")
      )
      (libsource (lib "easyedapro") (part "CL10B221KB8NNNC"))
    )
    (comp (ref "C91")
      (value "10uF")
      (footprint "easyedapro:C0603")
      (description "容值:10uF;精度:±10%;额定电压:10V;材质(温度系数):X5R;")
      (fields
        (field (name "Manufacturer Part") "CL10A106KP8NNNC")
        (field (name "Manufacturer") "SAMSUNG(三星)")
      )
      (libsource (lib "easyedapro") (part "CL10A106KP8NNNC"))
    )
    (comp (ref "C92")
      (value "10uF")
      (footprint "easyedapro:C0603")
      (description "容值:10uF;精度:±10%;额定电压:10V;材质(温度系数):X5R;")
      (fields
        (field (name "Manufacturer Part") "CL10A106KP8NNNC")
        (field (name "Manufacturer") "SAMSUNG(三星)")
      )
      (libsource (lib "easyedapro") (part "CL10A106KP8NNNC"))
    )
    (comp (ref "C93")
      (value "4.7uF")
      (footprint "easyedapro:C0603")
      (description "容值:4.7uF;精度:±10%;额定电压:16V;材质(温度系数):X5R;")
      (fields
        (field (name "Manufacturer Part") "CL10A475KO8NNNC")
        (field (name "Manufacturer") "SAMSUNG(三星)")
      )
      (libsource (lib "easyedapro") (part "CL10A475KO8NNNC"))
    )
    (comp (ref "C94")
      (value "4.7uF")
      (footprint "easyedapro:C0603")
      (description "容值:4.7uF;精度:±10%;额定电压:16V;材质(温度系数):X5R;")
      (fields
        (field (name "Manufacturer Part") "CL10A475KO8NNNC")
        (field (name "Manufacturer") "SAMSUNG(三星)")
      )
      (libsource (lib "easyedapro") (part "CL10A475KO8NNNC"))
    )
    (comp (ref "C95")
      (value "4.7uF")
      (footprint "easyedapro:C0603")
      (description "容值:4.7uF;精度:±10%;额定电压:16V;材质(温度系数):X5R;")
      (fields
        (field (name "Manufacturer Part") "CL10A475KO8NNNC")
        (field (name "Manufacturer") "SAMSUNG(三星)")
      )
      (libsource (lib "easyedapro") (part "CL10A475KO8NNNC"))
    )
    (comp (ref "C96")
      (value "22uF")
      (footprint "easyedapro:C0805")
      (description "容值:22uF;精度:±20%;额定电压:25V;材质(温度系数):X5R;")
      (fields
        (field (name "Manufacturer Part") "CL21A226MAQNNNE")
        (field (name "Manufacturer") "SAMSUNG(三星)")
      )
      (libsource (lib "easyedapro") (part "CL21A226MAQNNNE"))
    )
    (comp (ref "D9")
      (value "B5819WS")
      (footprint "easyedapro:SOD-323_L1.7-W1.3-LS2.5-FD")
      (description "二极管配置:独立式;正向压降(Vf):600mV@1.0A;直流反向耐压(Vr):40V;平均整流电流(Io):1A;")
      (fields (field (name "Manufacturer") "宏迦橙"))
      (libsource (lib "easyedapro") (part "B5819WS_C7420331"))
    )
    (comp (ref "D10")
      (value "B5819WS")
      (footprint "easyedapro:SOD-323_L1.7-W1.3-LS2.5-FD")
      (description "二极管配置:独立式;正向压降(Vf):600mV@1.0A;直流反向耐压(Vr):40V;平均整流电流(Io):1A;")
      (fields (field (name "Manufacturer") "宏迦橙"))
      (libsource (lib "easyedapro") (part "B5819WS_C7420331"))
    )
    (comp (ref "D11")
      (value "B5819WS")
      (footprint "easyedapro:SOD-323_L1.7-W1.3-LS2.5-FD")
      (description "二极管配置:独立式;正向压降(Vf):600mV@1.0A;直流反向耐压(Vr):40V;平均整流电流(Io):1A;")
      (fields (field (name "Manufacturer") "宏迦橙"))
      (libsource (lib "easyedapro") (part "B5819WS_C7420331"))
    )
    (comp (ref "D12")
      (value "B5819WS")
      (footprint "easyedapro:SOD-323_L1.7-W1.3-LS2.5-FD")
      (description "二极管配置:独立式;正向压降(Vf):600mV@1.0A;直流反向耐压(Vr):40V;平均整流电流(Io):1A;")
      (fields (field (name "Manufacturer") "宏迦橙"))
      (libsource (lib "easyedapro") (part "B5819WS_C7420331"))
    )
    (comp (ref "F4")
      (value "BSMD1206-150-16V")
      (footprint "easyedapro:F1206")
      (description "最大电压:16V;最大电流:40A;保持电流:1.5A;跳闸电流:3A;")
      (fields (field (name "Manufacturer") "BHFUSE(佰宏)"))
      (libsource (lib "easyedapro") (part "BSMD1206-150-16V"))
    )
    (comp (ref "L7")
      (value "CBG160808U000T")
      (footprint "easyedapro:L0603")
      (description "标称阻抗@测试频率:0Ω@100MHz;直流电阻(RDC):100mΩ;")
      (fields (field (name "Manufacturer") "FH(风华)"))
      (libsource (lib "easyedapro") (part "CBG160808U000T"))
    )
    (comp (ref "L8")
      (value "CBG160808U000T")
      (footprint "easyedapro:L0603")
      (description "标称阻抗@测试频率:0Ω@100MHz;直流电阻(RDC):100mΩ;")
      (fields (field (name "Manufacturer") "FH(风华)"))
      (libsource (lib "easyedapro") (part "CBG160808U000T"))
    )
    (comp (ref "L9")
      (value "6.8uH")
      (footprint "easyedapro:IND-SMD_L5.4-W5.2_FXL0530")
      (description "电感值:6.8uH;精度:±20%;额定电流:3.5A;饱和电流(Isat):4A;类型:一体成型电感;")
      (fields (field (name "Manufacturer Part") "FXL0530-6R8-M") (field (name "Manufacturer") "cjiang(长江微电)"))
      (libsource (lib "easyedapro") (part "FXL0530-6R8-M"))
    )
    (comp (ref "LED5")
      (value "XL-1608UGC-04")
      (footprint "easyedapro:LED0603-RD_GREEN")
      (fields (field (name "Manufacturer") "XINGLIGHT(成兴光)"))
      (libsource (lib "easyedapro") (part "XL-1608UGC-04"))
    )
    (comp (ref "LED6")
      (value "XL-1608UGC-04")
      (footprint "easyedapro:LED0603-RD_GREEN")
      (fields (field (name "Manufacturer") "XINGLIGHT(成兴光)"))
      (libsource (lib "easyedapro") (part "XL-1608UGC-04"))
    )
    (comp (ref "Q13")
      (value "AON6354")
      (footprint "easyedapro:DFN-8_L5.2-W6.1-P1.27-BL-EP")
      (fields (field (name "Manufacturer") "AOS"))
      (libsource (lib "easyedapro") (part "AON6354"))
    )
    (comp (ref "Q14")
      (value "AON6354")
      (footprint "easyedapro:DFN-8_L5.2-W6.1-P1.27-BL-EP")
      (fields (field (name "Manufacturer") "AOS"))
      (libsource (lib "easyedapro") (part "AON6354"))
    )
    (comp (ref "Q15")
      (value "AON6354")
      (footprint "easyedapro:DFN-8_L5.2-W6.1-P1.27-BL-EP")
      (fields (field (name "Manufacturer") "AOS"))
      (libsource (lib "easyedapro") (part "AON6354"))
    )
    (comp (ref "Q16")
      (value "AON6354")
      (footprint "easyedapro:DFN-8_L5.2-W6.1-P1.27-BL-EP")
      (fields (field (name "Manufacturer") "AOS"))
      (libsource (lib "easyedapro") (part "AON6354"))
    )
    (comp (ref "Q17")
      (value "AON6354")
      (footprint "easyedapro:DFN-8_L5.2-W6.1-P1.27-BL-EP")
      (fields (field (name "Manufacturer") "AOS"))
      (libsource (lib "easyedapro") (part "AON6354"))
    )
    (comp (ref "Q18")
      (value "AON6354")
      (footprint "easyedapro:DFN-8_L5.2-W6.1-P1.27-BL-EP")
      (fields (field (name "Manufacturer") "AOS"))
      (libsource (lib "easyedapro") (part "AON6354"))
    )
    (comp (ref "R51")
      (value "10kΩ")
      (footprint "easyedapro:R0603")
      (description "电阻类型:厚膜电阻;阻值:10kΩ;精度:±5%;功率:100mW;最大工作电压:75V;温度系数:±100ppm/°C;")
      (fields (field (name "Manufacturer Part") "FRC0603J103TS") (field (name "Manufacturer") "FOJAN(富捷)"))
      (libsource (lib "easyedapro") (part "FRC0603J103TS"))
    )
    (comp (ref "R52")
      (value "10kΩ")
      (footprint "easyedapro:R0603")
      (description "电阻类型:厚膜电阻;阻值:10kΩ;精度:±5%;功率:100mW;最大工作电压:75V;温度系数:±100ppm/°C;")
      (fields (field (name "Manufacturer Part") "FRC0603J103TS") (field (name "Manufacturer") "FOJAN(富捷)"))
      (libsource (lib "easyedapro") (part "FRC0603J103TS"))
    )
    (comp (ref "R53")
      (value "10kΩ")
      (footprint "easyedapro:R0603")
      (description "电阻类型:厚膜电阻;阻值:10kΩ;精度:±5%;功率:100mW;最大工作电压:75V;温度系数:±100ppm/°C;")
      (fields (field (name "Manufacturer Part") "FRC0603J103TS") (field (name "Manufacturer") "FOJAN(富捷)"))
      (libsource (lib "easyedapro") (part "FRC0603J103TS"))
    )
    (comp (ref "R54")
      (value "1kΩ")
      (footprint "easyedapro:R0603")
      (description "电阻类型:厚膜电阻;阻值:1kΩ;精度:±1%;功率:100mW;最大工作电压:75V;温度系数:±100ppm/°C;")
      (fields (field (name "Manufacturer Part") "RC0603FR-071KL") (field (name "Manufacturer") "YAGEO(国巨)"))
      (libsource (lib "easyedapro") (part "RC0603FR-071KL"))
    )
    (comp (ref "R55")
      (value "1kΩ")
      (footprint "easyedapro:R0603")
      (description "电阻类型:厚膜电阻;阻值:1kΩ;精度:±1%;功率:100mW;最大工作电压:75V;温度系数:±100ppm/°C;")
      (fields (field (name "Manufacturer Part") "RC0603FR-071KL") (field (name "Manufacturer") "YAGEO(国巨)"))
      (libsource (lib "easyedapro") (part "RC0603FR-071KL"))
    )
    (comp (ref "R56")
      (value "10kΩ")
      (footprint "easyedapro:R0603")
      (description "电阻类型:厚膜电阻;阻值:10kΩ;精度:±5%;功率:100mW;最大工作电压:75V;温度系数:±100ppm/°C;")
      (fields (field (name "Manufacturer Part") "FRC0603J103TS") (field (name "Manufacturer") "FOJAN(富捷)"))
      (libsource (lib "easyedapro") (part "FRC0603J103TS"))
    )
    (comp (ref "R57")
      (value "1kΩ")
      (footprint "easyedapro:R0603")
      (description "电阻类型:厚膜电阻;阻值:1kΩ;精度:±1%;功率:100mW;最大工作电压:75V;温度系数:±100ppm/°C;")
      (fields (field (name "Manufacturer Part") "RC0603FR-071KL") (field (name "Manufacturer") "YAGEO(国巨)"))
      (libsource (lib "easyedapro") (part "RC0603FR-071KL"))
    )
    (comp (ref "R58")
      (value "1kΩ")
      (footprint "easyedapro:R0603")
      (description "电阻类型:厚膜电阻;阻值:1kΩ;精度:±1%;功率:100mW;最大工作电压:75V;温度系数:±100ppm/°C;")
      (fields (field (name "Manufacturer Part") "RC0603FR-071KL") (field (name "Manufacturer") "YAGEO(国巨)"))
      (libsource (lib "easyedapro") (part "RC0603FR-071KL"))
    )
    (comp (ref "R59")
      (value "10kΩ")
      (footprint "easyedapro:R0603")
      (description "电阻类型:厚膜电阻;阻值:10kΩ;精度:±5%;功率:100mW;最大工作电压:75V;温度系数:±100ppm/°C;")
      (fields (field (name "Manufacturer Part") "FRC0603J103TS") (field (name "Manufacturer") "FOJAN(富捷)"))
      (libsource (lib "easyedapro") (part "FRC0603J103TS"))
    )
    (comp (ref "R60")
      (value "1kΩ")
      (footprint "easyedapro:R0603")
      (description "电阻类型:厚膜电阻;阻值:1kΩ;精度:±1%;功率:100mW;最大工作电压:75V;温度系数:±100ppm/°C;")
      (fields (field (name "Manufacturer Part") "RC0603FR-071KL") (field (name "Manufacturer") "YAGEO(国巨)"))
      (libsource (lib "easyedapro") (part "RC0603FR-071KL"))
    )
    (comp (ref "R61")
      (value "1kΩ")
      (footprint "easyedapro:R0603")
      (description "电阻类型:厚膜电阻;阻值:1kΩ;精度:±1%;功率:100mW;最大工作电压:75V;温度系数:±100ppm/°C;")
      (fields (field (name "Manufacturer Part") "RC0603FR-071KL") (field (name "Manufacturer") "YAGEO(国巨)"))
      (libsource (lib "easyedapro") (part "RC0603FR-071KL"))
    )
    (comp (ref "R62")
      (value "47kΩ")
      (footprint "easyedapro:R0603")
      (description "电阻类型:厚膜电阻;阻值:47kΩ;精度:±1%;功率:100mW;最大工作电压:75V;温度系数:±100ppm/°C;")
      (fields
        (field (name "Manufacturer Part") "0603WAF4702T5E")
        (field (name "Manufacturer") "UNI-ROYAL(厚声)")
      )
      (libsource (lib "easyedapro") (part "0603WAF4702T5E"))
    )
    (comp (ref "R63")
      (value "10kΩ")
      (footprint "easyedapro:R0603")
      (description "电阻类型:厚膜电阻;阻值:10kΩ;精度:±5%;功率:100mW;最大工作电压:75V;温度系数:±100ppm/°C;")
      (fields (field (name "Manufacturer Part") "FRC0603J103TS") (field (name "Manufacturer") "FOJAN(富捷)"))
      (libsource (lib "easyedapro") (part "FRC0603J103TS"))
    )
    (comp (ref "R64")
      (value "1kΩ")
      (footprint "easyedapro:R0603")
      (description "电阻类型:厚膜电阻;阻值:1kΩ;精度:±1%;功率:100mW;最大工作电压:75V;温度系数:±100ppm/°C;")
      (fields (field (name "Manufacturer Part") "RC0603FR-071KL") (field (name "Manufacturer") "YAGEO(国巨)"))
      (libsource (lib "easyedapro") (part "RC0603FR-071KL"))
    )
    (comp (ref "R65")
      (value "2.7kΩ")
      (footprint "easyedapro:R0603")
      (description "电阻类型:厚膜电阻;阻值:2.7kΩ;精度:±1%;功率:100mW;最大工作电压:75V;温度系数:±100ppm/°C;")
      (fields
        (field (name "Manufacturer Part") "0603WAF2701T5E")
        (field (name "Manufacturer") "UNI-ROYAL(厚声)")
      )
      (libsource (lib "easyedapro") (part "0603WAF2701T5E"))
    )
    (comp (ref "R66")
      (value "100kΩ")
      (footprint "easyedapro:R0603")
      (description "电阻类型:厚膜电阻;阻值:100kΩ;精度:±1%;功率:100mW;最大工作电压:75V;温度系数:±100ppm/°C;")
      (fields
        (field (name "Manufacturer Part") "0603WAF1003T5E")
        (field (name "Manufacturer") "UNI-ROYAL(厚声)")
      )
      (libsource (lib "easyedapro") (part "0603WAF1003T5E"))
    )
    (comp (ref "R67")
      (value "0Ω")
      (footprint "easyedapro:R0603")
      (description "电阻类型:厚膜电阻;阻值:0Ω;精度:±1%;功率:100mW;最大工作电压:75V;")
      (fields
        (field (name "Manufacturer Part") "0603WAF0000T5E")
        (field (name "Manufacturer") "UNI-ROYAL(厚声)")
      )
      (libsource (lib "easyedapro") (part "0603WAF0000T5E"))
    )
    (comp (ref "R68")
      (value "22kΩ")
      (footprint "easyedapro:R0603")
      (description "电阻类型:厚膜电阻;阻值:22kΩ;精度:±1%;功率:100mW;最大工作电压:75V;温度系数:±100ppm/°C;")
      (fields
        (field (name "Manufacturer Part") "0603WAF2202T5E")
        (field (name "Manufacturer") "UNI-ROYAL(厚声)")
      )
      (libsource (lib "easyedapro") (part "0603WAF2202T5E"))
    )
    (comp (ref "R69")
      (value "3kΩ")
      (footprint "easyedapro:R0603")
      (description "电阻类型:厚膜电阻;阻值:3kΩ;精度:±1%;功率:100mW;最大工作电压:75V;温度系数:±100ppm/°C;")
      (fields
        (field (name "Manufacturer Part") "0603WAF3001T5E")
        (field (name "Manufacturer") "UNI-ROYAL(厚声)")
      )
      (libsource (lib "easyedapro") (part "0603WAF3001T5E"))
    )
    (comp (ref "R70")
      (value "4.7Ω")
      (footprint "easyedapro:R0603")
      (description "电阻类型:厚膜电阻;阻值:4.7Ω;精度:±1%;功率:100mW;最大工作电压:75V;温度系数:±400ppm/°C;")
      (fields
        (field (name "Manufacturer Part") "0603WAF470KT5E")
        (field (name "Manufacturer") "UNI-ROYAL(厚声)")
      )
      (libsource (lib "easyedapro") (part "0603WAF470KT5E"))
    )
    (comp (ref "R71")
      (value "4.7Ω")
      (footprint "easyedapro:R0603")
      (description "电阻类型:厚膜电阻;阻值:4.7Ω;精度:±1%;功率:100mW;最大工作电压:75V;温度系数:±400ppm/°C;")
      (fields
        (field (name "Manufacturer Part") "0603WAF470KT5E")
        (field (name "Manufacturer") "UNI-ROYAL(厚声)")
      )
      (libsource (lib "easyedapro") (part "0603WAF470KT5E"))
    )
    (comp (ref "R72")
      (value "4.7Ω")
      (footprint "easyedapro:R0603")
      (description "电阻类型:厚膜电阻;阻值:4.7Ω;精度:±1%;功率:100mW;最大工作电压:75V;温度系数:±400ppm/°C;")
      (fields
        (field (name "Manufacturer Part") "0603WAF470KT5E")
        (field (name "Manufacturer") "UNI-ROYAL(厚声)")
      )
      (libsource (lib "easyedapro") (part "0603WAF470KT5E"))
    )
    (comp (ref "R73")
      (value "4.7Ω")
      (footprint "easyedapro:R0603")
      (description "电阻类型:厚膜电阻;阻值:4.7Ω;精度:±1%;功率:100mW;最大工作电压:75V;温度系数:±400ppm/°C;")
      (fields
        (field (name "Manufacturer Part") "0603WAF470KT5E")
        (field (name "Manufacturer") "UNI-ROYAL(厚声)")
      )
      (libsource (lib "easyedapro") (part "0603WAF470KT5E"))
    )
    (comp (ref "R74")
      (value "4.7Ω")
      (footprint "easyedapro:R0603")
      (description "电阻类型:厚膜电阻;阻值:4.7Ω;精度:±1%;功率:100mW;最大工作电压:75V;温度系数:±400ppm/°C;")
      (fields
        (field (name "Manufacturer Part") "0603WAF470KT5E")
        (field (name "Manufacturer") "UNI-ROYAL(厚声)")
      )
      (libsource (lib "easyedapro") (part "0603WAF470KT5E"))
    )
    (comp (ref "R75")
      (value "4.7Ω")
      (footprint "easyedapro:R0603")
      (description "电阻类型:厚膜电阻;阻值:4.7Ω;精度:±1%;功率:100mW;最大工作电压:75V;温度系数:±400ppm/°C;")
      (fields
        (field (name "Manufacturer Part") "0603WAF470KT5E")
        (field (name "Manufacturer") "UNI-ROYAL(厚声)")
      )
      (libsource (lib "easyedapro") (part "0603WAF470KT5E"))
    )
    (comp (ref "R103")
      (value "100Ω")
      (footprint "easyedapro:R0603")
      (description "电阻类型:厚膜电阻;阻值:100Ω;精度:±1%;功率:100mW;最大工作电压:75V;温度系数:±100ppm/°C;")
      (fields (field (name "Manufacturer Part") "RC0603FR-07100RL") (field (name "Manufacturer") "YAGEO(国巨)"))
      (libsource (lib "easyedapro") (part "RC0603FR-07100RL"))
    )
    (comp (ref "U10")
      (value "CH32V203C8T6")
      (footprint "easyedapro:LQFP-48_L7.0-W7.0-P0.50-LS9.0-BL")
      (description "CPU内核:RISC-V;程序存储容量:64KB;RAM总容量:20KB;GPIO端口数量:-;工作电压范围:-;CPU最大主频:144MHz;程序存储器类型:FLASH;")
      (fields (field (name "Manufacturer") "WCH(南京沁恒)"))
      (libsource (lib "easyedapro") (part "CH32V203C8T6"))
    )
    (comp (ref "U11")
      (value "SY8205FCC")
      (footprint "easyedapro:SOIC-8_L5.0-W4.0-P1.27-LS6.0-BL-EP2.0")
      (description "功能类型:降压型;输入电压:-;输出电流(最大值):-;")
      (fields (field (name "Manufacturer") "silergy(矽力杰)"))
      (libsource (lib "easyedapro") (part "SY8205FCC"))
    )
    (comp (ref "U12")
      (value "RT9013-33GB")
      (footprint "easyedapro:SOT-23-5_L2.9-W1.6-P0.95-LS2.8-BR")
      (fields (field (name "Manufacturer") "TECH PUBLIC(台舟)"))
      (libsource (lib "easyedapro") (part "RT9013-33GB_C19268157"))
    )
    (comp (ref "U13")
      (value "FD6288Q")
      (footprint "easyedapro:QFN-24_L4.0-W4.0-P0.50-BL-EP2.6")
      (fields (field (name "Manufacturer") "Fortior Tech(峰岹)"))
      (libsource (lib "easyedapro") (part "FD6288Q_C328453"))
    )
    (comp (ref "C97")
      (value "100nF")
      (footprint "easyedapro:C0603")
      (description "容值:100nF;精度:±10%;额定电压:50V;材质(温度系数):X7R;")
      (fields
        (field (name "Manufacturer Part") "CGA0603X7R104K500JT")
        (field (name "Manufacturer") "HRE(芯声)")
      )
      (libsource (lib "easyedapro") (part "CGA0603X7R104K500JT"))
    )
    (comp (ref "C98")
      (value "100nF")
      (footprint "easyedapro:C0603")
      (description "容值:100nF;精度:±10%;额定电压:50V;材质(温度系数):X7R;")
      (fields
        (field (name "Manufacturer Part") "CGA0603X7R104K500JT")
        (field (name "Manufacturer") "HRE(芯声)")
      )
      (libsource (lib "easyedapro") (part "CGA0603X7R104K500JT"))
    )
    (comp (ref "C99")
      (value "100nF")
      (footprint "easyedapro:C0603")
      (description "容值:100nF;精度:±10%;额定电压:50V;材质(温度系数):X7R;")
      (fields
        (field (name "Manufacturer Part") "CGA0603X7R104K500JT")
        (field (name "Manufacturer") "HRE(芯声)")
      )
      (libsource (lib "easyedapro") (part "CGA0603X7R104K500JT"))
    )
    (comp (ref "C100")
      (value "100nF")
      (footprint "easyedapro:C0402")
      (description "容值:100nF;精度:±10%;额定电压:50V;温度系数:X7R;")
      (fields
        (field (name "Manufacturer Part") "CL05B104KB54PNC")
        (field (name "Manufacturer") "SAMSUNG(三星)")
      )
      (libsource (lib "easyedapro") (part "C 0402"))
    )
    (comp (ref "C101")
      (value "100nF")
      (footprint "easyedapro:C0603")
      (description "容值:100nF;精度:±10%;额定电压:50V;材质(温度系数):X7R;")
      (fields
        (field (name "Manufacturer Part") "CGA0603X7R104K500JT")
        (field (name "Manufacturer") "HRE(芯声)")
      )
      (libsource (lib "easyedapro") (part "CGA0603X7R104K500JT"))
    )
    (comp (ref "C102")
      (value "100nF")
      (footprint "easyedapro:C0603")
      (description "容值:100nF;精度:±10%;额定电压:50V;材质(温度系数):X7R;")
      (fields
        (field (name "Manufacturer Part") "CGA0603X7R104K500JT")
        (field (name "Manufacturer") "HRE(芯声)")
      )
      (libsource (lib "easyedapro") (part "CGA0603X7R104K500JT"))
    )
    (comp (ref "C103")
      (value "100nF")
      (footprint "easyedapro:C0603")
      (description "容值:100nF;精度:±10%;额定电压:50V;材质(温度系数):X7R;")
      (fields
        (field (name "Manufacturer Part") "CGA0603X7R104K500JT")
        (field (name "Manufacturer") "HRE(芯声)")
      )
      (libsource (lib "easyedapro") (part "CGA0603X7R104K500JT"))
    )
    (comp (ref "C104")
      (value "100nF")
      (footprint "easyedapro:C0603")
      (description "容值:100nF;精度:±10%;额定电压:50V;材质(温度系数):X7R;")
      (fields
        (field (name "Manufacturer Part") "CGA0603X7R104K500JT")
        (field (name "Manufacturer") "HRE(芯声)")
      )
      (libsource (lib "easyedapro") (part "CGA0603X7R104K500JT"))
    )
    (comp (ref "C105")
      (value "100nF")
      (footprint "easyedapro:C0603")
      (description "容值:100nF;精度:±10%;额定电压:50V;材质(温度系数):X7R;")
      (fields
        (field (name "Manufacturer Part") "CGA0603X7R104K500JT")
        (field (name "Manufacturer") "HRE(芯声)")
      )
      (libsource (lib "easyedapro") (part "CGA0603X7R104K500JT"))
    )
    (comp (ref "C121")
      (value "10uF")
      (footprint "easyedapro:C0603")
      (description "容值:10uF;精度:±10%;额定电压:10V;材质(温度系数):X5R;")
      (fields
        (field (name "Manufacturer Part") "CL10A106KP8NNNC")
        (field (name "Manufacturer") "SAMSUNG(三星)")
      )
      (libsource (lib "easyedapro") (part "CL10A106KP8NNNC"))
    )
    (comp (ref "C122")
      (value "10uF")
      (footprint "easyedapro:C0603")
      (description "容值:10uF;精度:±10%;额定电压:10V;材质(温度系数):X5R;")
      (fields
        (field (name "Manufacturer Part") "CL10A106KP8NNNC")
        (field (name "Manufacturer") "SAMSUNG(三星)")
      )
      (libsource (lib "easyedapro") (part "CL10A106KP8NNNC"))
    )
    (comp (ref "C123")
      (value "4.7uF")
      (footprint "easyedapro:C0603")
      (description "容值:4.7uF;精度:±10%;额定电压:16V;材质(温度系数):X5R;")
      (fields
        (field (name "Manufacturer Part") "CL10A475KO8NNNC")
        (field (name "Manufacturer") "SAMSUNG(三星)")
      )
      (libsource (lib "easyedapro") (part "CL10A475KO8NNNC"))
    )
    (comp (ref "C124")
      (value "4.7uF")
      (footprint "easyedapro:C0603")
      (description "容值:4.7uF;精度:±10%;额定电压:16V;材质(温度系数):X5R;")
      (fields
        (field (name "Manufacturer Part") "CL10A475KO8NNNC")
        (field (name "Manufacturer") "SAMSUNG(三星)")
      )
      (libsource (lib "easyedapro") (part "CL10A475KO8NNNC"))
    )
    (comp (ref "C125")
      (value "4.7uF")
      (footprint "easyedapro:C0603")
      (description "容值:4.7uF;精度:±10%;额定电压:16V;材质(温度系数):X5R;")
      (fields
        (field (name "Manufacturer Part") "CL10A475KO8NNNC")
        (field (name "Manufacturer") "SAMSUNG(三星)")
      )
      (libsource (lib "easyedapro") (part "CL10A475KO8NNNC"))
    )
    (comp (ref "C126")
      (value "22uF")
      (footprint "easyedapro:C0805")
      (description "容值:22uF;精度:±20%;额定电压:25V;材质(温度系数):X5R;")
      (fields
        (field (name "Manufacturer Part") "CL21A226MAQNNNE")
        (field (name "Manufacturer") "SAMSUNG(三星)")
      )
      (libsource (lib "easyedapro") (part "CL21A226MAQNNNE"))
    )
    (comp (ref "C133")
      (value "22uF")
      (footprint "easyedapro:C0805")
      (description "容值:22uF;精度:±20%;额定电压:35V;材质(温度系数):X5R;")
      (fields
        (field (name "Manufacturer Part") "CGA0805X5R226M350MT")
        (field (name "Manufacturer") "HRE(芯声)")
      )
      (libsource (lib "easyedapro") (part "CGA0805X5R226M350MT"))
    )
    (comp (ref "C134")
      (value "22uF")
      (footprint "easyedapro:C0805")
      (description "容值:22uF;精度:±20%;额定电压:35V;材质(温度系数):X5R;")
      (fields
        (field (name "Manufacturer Part") "CGA0805X5R226M350MT")
        (field (name "Manufacturer") "HRE(芯声)")
      )
      (libsource (lib "easyedapro") (part "CGA0805X5R226M350MT"))
    )
    (comp (ref "C135")
      (value "22uF")
      (footprint "easyedapro:C0805")
      (description "容值:22uF;精度:±20%;额定电压:35V;材质(温度系数):X5R;")
      (fields
        (field (name "Manufacturer Part") "CGA0805X5R226M350MT")
        (field (name "Manufacturer") "HRE(芯声)")
      )
      (libsource (lib "easyedapro") (part "CGA0805X5R226M350MT"))
    )
    (comp (ref "C136")
      (value "22uF")
      (footprint "easyedapro:C0805")
      (description "容值:22uF;精度:±20%;额定电压:35V;材质(温度系数):X5R;")
      (fields
        (field (name "Manufacturer Part") "CGA0805X5R226M350MT")
        (field (name "Manufacturer") "HRE(芯声)")
      )
      (libsource (lib "easyedapro") (part "CGA0805X5R226M350MT"))
    )
    (comp (ref "C137")
      (value "22uF")
      (footprint "easyedapro:C0805")
      (description "容值:22uF;精度:±20%;额定电压:35V;材质(温度系数):X5R;")
      (fields
        (field (name "Manufacturer Part") "CGA0805X5R226M350MT")
        (field (name "Manufacturer") "HRE(芯声)")
      )
      (libsource (lib "easyedapro") (part "CGA0805X5R226M350MT"))
    )
    (comp (ref "C138")
      (value "22uF")
      (footprint "easyedapro:C0805")
      (description "容值:22uF;精度:±20%;额定电压:35V;材质(温度系数):X5R;")
      (fields
        (field (name "Manufacturer Part") "CGA0805X5R226M350MT")
        (field (name "Manufacturer") "HRE(芯声)")
      )
      (libsource (lib "easyedapro") (part "CGA0805X5R226M350MT"))
    )
    (comp (ref "D13")
      (value "B5819WS")
      (footprint "easyedapro:SOD-323_L1.7-W1.3-LS2.5-FD")
      (description "二极管配置:独立式;正向压降(Vf):600mV@1.0A;直流反向耐压(Vr):40V;平均整流电流(Io):1A;")
      (fields (field (name "Manufacturer") "宏迦橙"))
      (libsource (lib "easyedapro") (part "B5819WS_C7420331"))
    )
    (comp (ref "D14")
      (value "B5819WS")
      (footprint "easyedapro:SOD-323_L1.7-W1.3-LS2.5-FD")
      (description "二极管配置:独立式;正向压降(Vf):600mV@1.0A;直流反向耐压(Vr):40V;平均整流电流(Io):1A;")
      (fields (field (name "Manufacturer") "宏迦橙"))
      (libsource (lib "easyedapro") (part "B5819WS_C7420331"))
    )
    (comp (ref "D15")
      (value "B5819WS")
      (footprint "easyedapro:SOD-323_L1.7-W1.3-LS2.5-FD")
      (description "二极管配置:独立式;正向压降(Vf):600mV@1.0A;直流反向耐压(Vr):40V;平均整流电流(Io):1A;")
      (fields (field (name "Manufacturer") "宏迦橙"))
      (libsource (lib "easyedapro") (part "B5819WS_C7420331"))
    )
    (comp (ref "D16")
      (value "B5819WS")
      (footprint "easyedapro:SOD-323_L1.7-W1.3-LS2.5-FD")
      (description "二极管配置:独立式;正向压降(Vf):600mV@1.0A;直流反向耐压(Vr):40V;平均整流电流(Io):1A;")
      (fields (field (name "Manufacturer") "宏迦橙"))
      (libsource (lib "easyedapro") (part "B5819WS_C7420331"))
    )
    (comp (ref "L10")
      (value "CBG160808U000T")
      (footprint "easyedapro:L0603")
      (description "标称阻抗@测试频率:0Ω@100MHz;直流电阻(RDC):100mΩ;")
      (fields (field (name "Manufacturer") "FH(风华)"))
      (libsource (lib "easyedapro") (part "CBG160808U000T"))
    )
    (comp (ref "L11")
      (value "CBG160808U000T")
      (footprint "easyedapro:L0603")
      (description "标称阻抗@测试频率:0Ω@100MHz;直流电阻(RDC):100mΩ;")
      (fields (field (name "Manufacturer") "FH(风华)"))
      (libsource (lib "easyedapro") (part "CBG160808U000T"))
    )
    (comp (ref "LED7")
      (value "XL-1608UGC-04")
      (footprint "easyedapro:LED0603-RD_GREEN")
      (fields (field (name "Manufacturer") "XINGLIGHT(成兴光)"))
      (libsource (lib "easyedapro") (part "XL-1608UGC-04"))
    )
    (comp (ref "LED8")
      (value "XL-1608UGC-04")
      (footprint "easyedapro:LED0603-RD_GREEN")
      (fields (field (name "Manufacturer") "XINGLIGHT(成兴光)"))
      (libsource (lib "easyedapro") (part "XL-1608UGC-04"))
    )
    (comp (ref "Q19")
      (value "AON6354")
      (footprint "easyedapro:DFN-8_L5.2-W6.1-P1.27-BL-EP")
      (fields (field (name "Manufacturer") "AOS"))
      (libsource (lib "easyedapro") (part "AON6354"))
    )
    (comp (ref "Q20")
      (value "AON6354")
      (footprint "easyedapro:DFN-8_L5.2-W6.1-P1.27-BL-EP")
      (fields (field (name "Manufacturer") "AOS"))
      (libsource (lib "easyedapro") (part "AON6354"))
    )
    (comp (ref "Q21")
      (value "AON6354")
      (footprint "easyedapro:DFN-8_L5.2-W6.1-P1.27-BL-EP")
      (fields (field (name "Manufacturer") "AOS"))
      (libsource (lib "easyedapro") (part "AON6354"))
    )
    (comp (ref "Q22")
      (value "AON6354")
      (footprint "easyedapro:DFN-8_L5.2-W6.1-P1.27-BL-EP")
      (fields (field (name "Manufacturer") "AOS"))
      (libsource (lib "easyedapro") (part "AON6354"))
    )
    (comp (ref "Q23")
      (value "AON6354")
      (footprint "easyedapro:DFN-8_L5.2-W6.1-P1.27-BL-EP")
      (fields (field (name "Manufacturer") "AOS"))
      (libsource (lib "easyedapro") (part "AON6354"))
    )
    (comp (ref "Q24")
      (value "AON6354")
      (footprint "easyedapro:DFN-8_L5.2-W6.1-P1.27-BL-EP")
      (fields (field (name "Manufacturer") "AOS"))
      (libsource (lib "easyedapro") (part "AON6354"))
    )
    (comp (ref "R76")
      (value "10kΩ")
      (footprint "easyedapro:R0603")
      (description "电阻类型:厚膜电阻;阻值:10kΩ;精度:±5%;功率:100mW;最大工作电压:75V;温度系数:±100ppm/°C;")
      (fields (field (name "Manufacturer Part") "FRC0603J103TS") (field (name "Manufacturer") "FOJAN(富捷)"))
      (libsource (lib "easyedapro") (part "FRC0603J103TS"))
    )
    (comp (ref "R77")
      (value "10kΩ")
      (footprint "easyedapro:R0603")
      (description "电阻类型:厚膜电阻;阻值:10kΩ;精度:±5%;功率:100mW;最大工作电压:75V;温度系数:±100ppm/°C;")
      (fields (field (name "Manufacturer Part") "FRC0603J103TS") (field (name "Manufacturer") "FOJAN(富捷)"))
      (libsource (lib "easyedapro") (part "FRC0603J103TS"))
    )
    (comp (ref "R78")
      (value "10kΩ")
      (footprint "easyedapro:R0603")
      (description "电阻类型:厚膜电阻;阻值:10kΩ;精度:±5%;功率:100mW;最大工作电压:75V;温度系数:±100ppm/°C;")
      (fields (field (name "Manufacturer Part") "FRC0603J103TS") (field (name "Manufacturer") "FOJAN(富捷)"))
      (libsource (lib "easyedapro") (part "FRC0603J103TS"))
    )
    (comp (ref "R79")
      (value "1kΩ")
      (footprint "easyedapro:R0603")
      (description "电阻类型:厚膜电阻;阻值:1kΩ;精度:±1%;功率:100mW;最大工作电压:75V;温度系数:±100ppm/°C;")
      (fields (field (name "Manufacturer Part") "RC0603FR-071KL") (field (name "Manufacturer") "YAGEO(国巨)"))
      (libsource (lib "easyedapro") (part "RC0603FR-071KL"))
    )
    (comp (ref "R80")
      (value "1kΩ")
      (footprint "easyedapro:R0603")
      (description "电阻类型:厚膜电阻;阻值:1kΩ;精度:±1%;功率:100mW;最大工作电压:75V;温度系数:±100ppm/°C;")
      (fields (field (name "Manufacturer Part") "RC0603FR-071KL") (field (name "Manufacturer") "YAGEO(国巨)"))
      (libsource (lib "easyedapro") (part "RC0603FR-071KL"))
    )
    (comp (ref "R81")
      (value "10kΩ")
      (footprint "easyedapro:R0603")
      (description "电阻类型:厚膜电阻;阻值:10kΩ;精度:±5%;功率:100mW;最大工作电压:75V;温度系数:±100ppm/°C;")
      (fields (field (name "Manufacturer Part") "FRC0603J103TS") (field (name "Manufacturer") "FOJAN(富捷)"))
      (libsource (lib "easyedapro") (part "FRC0603J103TS"))
    )
    (comp (ref "R82")
      (value "1kΩ")
      (footprint "easyedapro:R0603")
      (description "电阻类型:厚膜电阻;阻值:1kΩ;精度:±1%;功率:100mW;最大工作电压:75V;温度系数:±100ppm/°C;")
      (fields (field (name "Manufacturer Part") "RC0603FR-071KL") (field (name "Manufacturer") "YAGEO(国巨)"))
      (libsource (lib "easyedapro") (part "RC0603FR-071KL"))
    )
    (comp (ref "R83")
      (value "1kΩ")
      (footprint "easyedapro:R0603")
      (description "电阻类型:厚膜电阻;阻值:1kΩ;精度:±1%;功率:100mW;最大工作电压:75V;温度系数:±100ppm/°C;")
      (fields (field (name "Manufacturer Part") "RC0603FR-071KL") (field (name "Manufacturer") "YAGEO(国巨)"))
      (libsource (lib "easyedapro") (part "RC0603FR-071KL"))
    )
    (comp (ref "R84")
      (value "10kΩ")
      (footprint "easyedapro:R0603")
      (description "电阻类型:厚膜电阻;阻值:10kΩ;精度:±5%;功率:100mW;最大工作电压:75V;温度系数:±100ppm/°C;")
      (fields (field (name "Manufacturer Part") "FRC0603J103TS") (field (name "Manufacturer") "FOJAN(富捷)"))
      (libsource (lib "easyedapro") (part "FRC0603J103TS"))
    )
    (comp (ref "R85")
      (value "1kΩ")
      (footprint "easyedapro:R0603")
      (description "电阻类型:厚膜电阻;阻值:1kΩ;精度:±1%;功率:100mW;最大工作电压:75V;温度系数:±100ppm/°C;")
      (fields (field (name "Manufacturer Part") "RC0603FR-071KL") (field (name "Manufacturer") "YAGEO(国巨)"))
      (libsource (lib "easyedapro") (part "RC0603FR-071KL"))
    )
    (comp (ref "R86")
      (value "1kΩ")
      (footprint "easyedapro:R0603")
      (description "电阻类型:厚膜电阻;阻值:1kΩ;精度:±1%;功率:100mW;最大工作电压:75V;温度系数:±100ppm/°C;")
      (fields (field (name "Manufacturer Part") "RC0603FR-071KL") (field (name "Manufacturer") "YAGEO(国巨)"))
      (libsource (lib "easyedapro") (part "RC0603FR-071KL"))
    )
    (comp (ref "R87")
      (value "47kΩ")
      (footprint "easyedapro:R0603")
      (description "电阻类型:厚膜电阻;阻值:47kΩ;精度:±1%;功率:100mW;最大工作电压:75V;温度系数:±100ppm/°C;")
      (fields
        (field (name "Manufacturer Part") "0603WAF4702T5E")
        (field (name "Manufacturer") "UNI-ROYAL(厚声)")
      )
      (libsource (lib "easyedapro") (part "0603WAF4702T5E"))
    )
    (comp (ref "R88")
      (value "10kΩ")
      (footprint "easyedapro:R0603")
      (description "电阻类型:厚膜电阻;阻值:10kΩ;精度:±5%;功率:100mW;最大工作电压:75V;温度系数:±100ppm/°C;")
      (fields (field (name "Manufacturer Part") "FRC0603J103TS") (field (name "Manufacturer") "FOJAN(富捷)"))
      (libsource (lib "easyedapro") (part "FRC0603J103TS"))
    )
    (comp (ref "R89")
      (value "1kΩ")
      (footprint "easyedapro:R0603")
      (description "电阻类型:厚膜电阻;阻值:1kΩ;精度:±1%;功率:100mW;最大工作电压:75V;温度系数:±100ppm/°C;")
      (fields (field (name "Manufacturer Part") "RC0603FR-071KL") (field (name "Manufacturer") "YAGEO(国巨)"))
      (libsource (lib "easyedapro") (part "RC0603FR-071KL"))
    )
    (comp (ref "R90")
      (value "2.7kΩ")
      (footprint "easyedapro:R0603")
      (description "电阻类型:厚膜电阻;阻值:2.7kΩ;精度:±1%;功率:100mW;最大工作电压:75V;温度系数:±100ppm/°C;")
      (fields
        (field (name "Manufacturer Part") "0603WAF2701T5E")
        (field (name "Manufacturer") "UNI-ROYAL(厚声)")
      )
      (libsource (lib "easyedapro") (part "0603WAF2701T5E"))
    )
    (comp (ref "R95")
      (value "4.7Ω")
      (footprint "easyedapro:R0603")
      (description "电阻类型:厚膜电阻;阻值:4.7Ω;精度:±1%;功率:100mW;最大工作电压:75V;温度系数:±400ppm/°C;")
      (fields
        (field (name "Manufacturer Part") "0603WAF470KT5E")
        (field (name "Manufacturer") "UNI-ROYAL(厚声)")
      )
      (libsource (lib "easyedapro") (part "0603WAF470KT5E"))
    )
    (comp (ref "R96")
      (value "4.7Ω")
      (footprint "easyedapro:R0603")
      (description "电阻类型:厚膜电阻;阻值:4.7Ω;精度:±1%;功率:100mW;最大工作电压:75V;温度系数:±400ppm/°C;")
      (fields
        (field (name "Manufacturer Part") "0603WAF470KT5E")
        (field (name "Manufacturer") "UNI-ROYAL(厚声)")
      )
      (libsource (lib "easyedapro") (part "0603WAF470KT5E"))
    )
    (comp (ref "R97")
      (value "4.7Ω")
      (footprint "easyedapro:R0603")
      (description "电阻类型:厚膜电阻;阻值:4.7Ω;精度:±1%;功率:100mW;最大工作电压:75V;温度系数:±400ppm/°C;")
      (fields
        (field (name "Manufacturer Part") "0603WAF470KT5E")
        (field (name "Manufacturer") "UNI-ROYAL(厚声)")
      )
      (libsource (lib "easyedapro") (part "0603WAF470KT5E"))
    )
    (comp (ref "R98")
      (value "4.7Ω")
      (footprint "easyedapro:R0603")
      (description "电阻类型:厚膜电阻;阻值:4.7Ω;精度:±1%;功率:100mW;最大工作电压:75V;温度系数:±400ppm/°C;")
      (fields
        (field (name "Manufacturer Part") "0603WAF470KT5E")
        (field (name "Manufacturer") "UNI-ROYAL(厚声)")
      )
      (libsource (lib "easyedapro") (part "0603WAF470KT5E"))
    )
    (comp (ref "R99")
      (value "4.7Ω")
      (footprint "easyedapro:R0603")
      (description "电阻类型:厚膜电阻;阻值:4.7Ω;精度:±1%;功率:100mW;最大工作电压:75V;温度系数:±400ppm/°C;")
      (fields
        (field (name "Manufacturer Part") "0603WAF470KT5E")
        (field (name "Manufacturer") "UNI-ROYAL(厚声)")
      )
      (libsource (lib "easyedapro") (part "0603WAF470KT5E"))
    )
    (comp (ref "R100")
      (value "4.7Ω")
      (footprint "easyedapro:R0603")
      (description "电阻类型:厚膜电阻;阻值:4.7Ω;精度:±1%;功率:100mW;最大工作电压:75V;温度系数:±400ppm/°C;")
      (fields
        (field (name "Manufacturer Part") "0603WAF470KT5E")
        (field (name "Manufacturer") "UNI-ROYAL(厚声)")
      )
      (libsource (lib "easyedapro") (part "0603WAF470KT5E"))
    )
    (comp (ref "R104")
      (value "100Ω")
      (footprint "easyedapro:R0603")
      (description "电阻类型:厚膜电阻;阻值:100Ω;精度:±1%;功率:100mW;最大工作电压:75V;温度系数:±100ppm/°C;")
      (fields (field (name "Manufacturer Part") "RC0603FR-07100RL") (field (name "Manufacturer") "YAGEO(国巨)"))
      (libsource (lib "easyedapro") (part "RC0603FR-07100RL"))
    )
    (comp (ref "U14")
      (value "CH32V203C8T6")
      (footprint "easyedapro:LQFP-48_L7.0-W7.0-P0.50-LS9.0-BL")
      (description "CPU内核:RISC-V;程序存储容量:64KB;RAM总容量:20KB;GPIO端口数量:-;工作电压范围:-;CPU最大主频:144MHz;程序存储器类型:FLASH;")
      (fields (field (name "Manufacturer") "WCH(南京沁恒)"))
      (libsource (lib "easyedapro") (part "CH32V203C8T6"))
    )
    (comp (ref "U16")
      (value "RT9013-33GB")
      (footprint "easyedapro:SOT-23-5_L2.9-W1.6-P0.95-LS2.8-BR")
      (fields (field (name "Manufacturer") "TECH PUBLIC(台舟)"))
      (libsource (lib "easyedapro") (part "RT9013-33GB_C19268157"))
    )
    (comp (ref "U17")
      (value "FD6288Q")
      (footprint "easyedapro:QFN-24_L4.0-W4.0-P0.50-BL-EP2.6")
      (fields (field (name "Manufacturer") "Fortior Tech(峰岹)"))
      (libsource (lib "easyedapro") (part "FD6288Q_C328453"))
    )
    (comp (ref "CN2")
      (value "ZX-XH2.54-4PZZ")
      (footprint "easyedapro:CONN-TH_4P-P2.50_4PIN")
      (fields (field (name "Manufacturer") "Megastar(兆星)"))
      (libsource (lib "easyedapro") (part "ZX-XH2.54-4PZZ"))
    )
    (comp (ref "H1")
      (value "PZ254V-11-02P")
      (footprint "easyedapro:HDR-TH_2P-P2.54-V-M")
      (fields (field (name "Manufacturer") "XFCN(兴飞)"))
      (libsource (lib "easyedapro") (part "PZ254V-11-02P"))
    )
    (comp (ref "H2")
      (value "PZ254V-11-02P")
      (footprint "easyedapro:HDR-TH_2P-P2.54-V-M")
      (fields (field (name "Manufacturer") "XFCN(兴飞)"))
      (libsource (lib "easyedapro") (part "PZ254V-11-02P"))
    )
    (comp (ref "H3")
      (value "PZ254V-11-02P")
      (footprint "easyedapro:HDR-TH_2P-P2.54-V-M")
      (fields (field (name "Manufacturer") "XFCN(兴飞)"))
      (libsource (lib "easyedapro") (part "PZ254V-11-02P"))
    )
    (comp (ref "H4")
      (value "PZ254V-11-02P")
      (footprint "easyedapro:HDR-TH_2P-P2.54-V-M")
      (fields (field (name "Manufacturer") "XFCN(兴飞)"))
      (libsource (lib "easyedapro") (part "PZ254V-11-02P"))
    )
    (comp (ref "R105")
      (value "0Ω")
      (footprint "easyedapro:R0603")
      (description "电阻类型:厚膜电阻;阻值:0Ω;精度:±1%;功率:100mW;最大工作电压:75V;")
      (fields
        (field (name "Manufacturer Part") "0603WAF0000T5E")
        (field (name "Manufacturer") "UNI-ROYAL(厚声)")
      )
      (libsource (lib "easyedapro") (part "0603WAF0000T5E"))
    )
    (comp (ref "R106")
      (value "0Ω")
      (footprint "easyedapro:R0603")
      (description "电阻类型:厚膜电阻;阻值:0Ω;精度:±1%;功率:100mW;最大工作电压:75V;")
      (fields
        (field (name "Manufacturer Part") "0603WAF0000T5E")
        (field (name "Manufacturer") "UNI-ROYAL(厚声)")
      )
      (libsource (lib "easyedapro") (part "0603WAF0000T5E"))
    )
    (comp (ref "R107")
      (value "0Ω")
      (footprint "easyedapro:R0603")
      (description "电阻类型:厚膜电阻;阻值:0Ω;精度:±1%;功率:100mW;最大工作电压:75V;")
      (fields
        (field (name "Manufacturer Part") "0603WAF0000T5E")
        (field (name "Manufacturer") "UNI-ROYAL(厚声)")
      )
      (libsource (lib "easyedapro") (part "0603WAF0000T5E"))
    )
    (comp (ref "TP1") (value "~") (footprint "easyedapro:M3螺丝") (libsource (lib "easyedapro") (part "螺丝孔")))
    (comp (ref "TP2") (value "~") (footprint "easyedapro:M3螺丝") (libsource (lib "easyedapro") (part "螺丝孔")))
  )
  (nets
    (net (code "1") (name "+3V33") (class "Default")
      (node (ref "C68") (pin "2") (pinfunction "2_2") (pintype "unspecified"))
      (node (ref "C69") (pin "1") (pinfunction "1_1") (pintype "unspecified"))
      (node (ref "C71") (pin "2") (pinfunction "2_2") (pintype "unspecified"))
      (node (ref "C92") (pin "2") (pinfunction "2_2") (pintype "unspecified"))
      (node (ref "L7") (pin "2") (pinfunction "2_2") (pintype "unspecified"))
      (node (ref "R51") (pin "2") (pinfunction "2_2") (pintype "unspecified"))
      (node (ref "R64") (pin "2") (pinfunction "2_2") (pintype "input"))
      (node (ref "R65") (pin "1") (pinfunction "1_1") (pintype "input"))
      (node (ref "U10") (pin "1") (pinfunction "VBAT_1") (pintype "unspecified"))
      (node (ref "U10") (pin "24") (pinfunction "VDD_VIO_1_24") (pintype "unspecified"))
      (node (ref "U10") (pin "36") (pinfunction "VDD_2_36") (pintype "unspecified"))
      (node (ref "U10") (pin "48") (pinfunction "VDD_VIO_3_48") (pintype "unspecified"))
      (node (ref "U12") (pin "5") (pinfunction "VOUT_5") (pintype "unspecified"))
    )
    (net (code "2") (name "+3V34") (class "Default")
      (node (ref "C101") (pin "2") (pinfunction "2_2") (pintype "unspecified"))
      (node (ref "C122") (pin "2") (pinfunction "2_2") (pintype "unspecified"))
      (node (ref "C98") (pin "2") (pinfunction "2_2") (pintype "unspecified"))
      (node (ref "C99") (pin "1") (pinfunction "1_1") (pintype "unspecified"))
      (node (ref "L10") (pin "2") (pinfunction "2_2") (pintype "unspecified"))
      (node (ref "R76") (pin "2") (pinfunction "2_2") (pintype "unspecified"))
      (node (ref "R89") (pin "2") (pinfunction "2_2") (pintype "input"))
      (node (ref "R90") (pin "1") (pinfunction "1_1") (pintype "input"))
      (node (ref "U14") (pin "1") (pinfunction "VBAT_1") (pintype "unspecified"))
      (node (ref "U14") (pin "24") (pinfunction "VDD_VIO_1_24") (pintype "unspecified"))
      (node (ref "U14") (pin "36") (pinfunction "VDD_2_36") (pintype "unspecified"))
      (node (ref "U14") (pin "48") (pinfunction "VDD_VIO_3_48") (pintype "unspecified"))
      (node (ref "U16") (pin "5") (pinfunction "VOUT_5") (pintype "unspecified"))
    )
    (net (code "3") (name "+5V") (class "Default")
      (node (ref "C121") (pin "2") (pinfunction "2_2") (pintype "unspecified"))
      (node (ref "C85") (pin "2") (pinfunction "2_2") (pintype "unspecified"))
      (node (ref "C86") (pin "2") (pinfunction "2_2") (pintype "unspecified"))
      (node (ref "C90") (pin "2") (pinfunction "2_2") (pintype "input"))
      (node (ref "C91") (pin "2") (pinfunction "2_2") (pintype "unspecified"))
      (node (ref "D13") (pin "1") (pinfunction "A_1") (pintype "unspecified"))
      (node (ref "D9") (pin "1") (pinfunction "A_1") (pintype "unspecified"))
      (node (ref "L9") (pin "1") (pinfunction "1_1") (pintype "unspecified"))
      (node (ref "R68") (pin "2") (pinfunction "2_2") (pintype "input"))
      (node (ref "U12") (pin "1") (pinfunction "VIN_1") (pintype "unspecified"))
      (node (ref "U12") (pin "3") (pinfunction "CE_3") (pintype "unspecified"))
      (node (ref "U16") (pin "1") (pinfunction "VIN_1") (pintype "unspecified"))
      (node (ref "U16") (pin "3") (pinfunction "CE_3") (pintype "unspecified"))
    )
    (net (code "4") (name "+12V") (class "Default")
      (node (ref "C126") (pin "2") (pinfunction "2_2") (pintype "unspecified"))
      (node (ref "C88") (pin "2") (pinfunction "2_2") (pintype "unspecified"))
      (node (ref "C89") (pin "2") (pinfunction "2_2") (pintype "unspecified"))
      (node (ref "C96") (pin "2") (pinfunction "2_2") (pintype "unspecified"))
      (node (ref "D10") (pin "1") (pinfunction "A_1") (pintype "unspecified"))
      (node (ref "D11") (pin "1") (pinfunction "A_1") (pintype "unspecified"))
      (node (ref "D12") (pin "1") (pinfunction "A_1") (pintype "unspecified"))
      (node (ref "D14") (pin "1") (pinfunction "A_1") (pintype "unspecified"))
      (node (ref "D15") (pin "1") (pinfunction "A_1") (pintype "unspecified"))
      (node (ref "D16") (pin "1") (pinfunction "A_1") (pintype "unspecified"))
      (node (ref "F4") (pin "2") (pinfunction "2_2") (pintype "unspecified"))
      (node (ref "R66") (pin "2") (pinfunction "2_2") (pintype "input"))
      (node (ref "U11") (pin "7") (pinfunction "VIN_7") (pintype "input"))
      (node (ref "U11") (pin "8") (pinfunction "VIN_8") (pintype "input"))
      (node (ref "U13") (pin "4") (pinfunction "VCC_4") (pintype "unspecified"))
      (node (ref "U17") (pin "4") (pinfunction "VCC_4") (pintype "unspecified"))
    )
    (net (code "5") (name "3V31") (class "Default")
      (node (ref "C1") (pin "2") (pinfunction "2_2") (pintype "unspecified"))
      (node (ref "C27") (pin "2") (pinfunction "2_2") (pintype "unspecified"))
      (node (ref "C3") (pin "2") (pinfunction "2_2") (pintype "unspecified"))
      (node (ref "C4") (pin "1") (pinfunction "1_1") (pintype "unspecified"))
      (node (ref "L1") (pin "2") (pinfunction "2_2") (pintype "unspecified"))
      (node (ref "R14") (pin "2") (pinfunction "2_2") (pintype "input"))
      (node (ref "R15") (pin "1") (pinfunction "1_1") (pintype "input"))
      (node (ref "R2") (pin "2") (pinfunction "2_2") (pintype "unspecified"))
      (node (ref "U1") (pin "1") (pinfunction "VBAT_1") (pintype "unspecified"))
      (node (ref "U1") (pin "24") (pinfunction "VDD_VIO_1_24") (pintype "unspecified"))
      (node (ref "U1") (pin "36") (pinfunction "VDD_2_36") (pintype "unspecified"))
      (node (ref "U1") (pin "48") (pinfunction "VDD_VIO_3_48") (pintype "unspecified"))
      (node (ref "U4") (pin "5") (pinfunction "VOUT_5") (pintype "unspecified"))
    )
    (net (code "6") (name "3V32") (class "Default")
      (node (ref "C38") (pin "2") (pinfunction "2_2") (pintype "unspecified"))
      (node (ref "C39") (pin "1") (pinfunction "1_1") (pintype "unspecified"))
      (node (ref "C41") (pin "2") (pinfunction "2_2") (pintype "unspecified"))
      (node (ref "C62") (pin "2") (pinfunction "2_2") (pintype "unspecified"))
      (node (ref "L4") (pin "2") (pinfunction "2_2") (pintype "unspecified"))
      (node (ref "R26") (pin "2") (pinfunction "2_2") (pintype "unspecified"))
      (node (ref "R39") (pin "2") (pinfunction "2_2") (pintype "input"))
      (node (ref "R40") (pin "1") (pinfunction "1_1") (pintype "input"))
      (node (ref "U6") (pin "1") (pinfunction "VBAT_1") (pintype "unspecified"))
      (node (ref "U6") (pin "24") (pinfunction "VDD_VIO_1_24") (pintype "unspecified"))
      (node (ref "U6") (pin "36") (pinfunction "VDD_2_36") (pintype "unspecified"))
      (node (ref "U6") (pin "48") (pinfunction "VDD_VIO_3_48") (pintype "unspecified"))
      (node (ref "U8") (pin "5") (pinfunction "VOUT_5") (pintype "unspecified"))
    )
    (net (code "7") (name "5V") (class "Default")
      (node (ref "C19") (pin "2") (pinfunction "2_2") (pintype "unspecified"))
      (node (ref "C20") (pin "2") (pinfunction "2_2") (pintype "unspecified"))
      (node (ref "C25") (pin "2") (pinfunction "2_2") (pintype "input"))
      (node (ref "C26") (pin "2") (pinfunction "2_2") (pintype "unspecified"))
      (node (ref "C61") (pin "2") (pinfunction "2_2") (pintype "unspecified"))
      (node (ref "D1") (pin "1") (pinfunction "A_1") (pintype "unspecified"))
      (node (ref "D5") (pin "1") (pinfunction "A_1") (pintype "unspecified"))
      (node (ref "L3") (pin "1") (pinfunction "1_1") (pintype "unspecified"))
      (node (ref "R18") (pin "2") (pinfunction "2_2") (pintype "input"))
      (node (ref "U4") (pin "1") (pinfunction "VIN_1") (pintype "unspecified"))
      (node (ref "U4") (pin "3") (pinfunction "CE_3") (pintype "unspecified"))
      (node (ref "U8") (pin "1") (pinfunction "VIN_1") (pintype "unspecified"))
      (node (ref "U8") (pin "3") (pinfunction "CE_3") (pintype "unspecified"))
    )
    (net (code "8") (name "12V") (class "Default")
      (node (ref "C23") (pin "2") (pinfunction "2_2") (pintype "unspecified"))
      (node (ref "C24") (pin "2") (pinfunction "2_2") (pintype "unspecified"))
      (node (ref "C36") (pin "2") (pinfunction "2_2") (pintype "unspecified"))
      (node (ref "C66") (pin "2") (pinfunction "2_2") (pintype "unspecified"))
      (node (ref "D2") (pin "1") (pinfunction "A_1") (pintype "unspecified"))
      (node (ref "D3") (pin "1") (pinfunction "A_1") (pintype "unspecified"))
      (node (ref "D4") (pin "1") (pinfunction "A_1") (pintype "unspecified"))
      (node (ref "D6") (pin "1") (pinfunction "A_1") (pintype "unspecified"))
      (node (ref "D7") (pin "1") (pinfunction "A_1") (pintype "unspecified"))
      (node (ref "D8") (pin "1") (pinfunction "A_1") (pintype "unspecified"))
      (node (ref "F2") (pin "2") (pinfunction "2_2") (pintype "unspecified"))
      (node (ref "R16") (pin "2") (pinfunction "2_2") (pintype "input"))
      (node (ref "U3") (pin "7") (pinfunction "VIN_7") (pintype "input"))
      (node (ref "U3") (pin "8") (pinfunction "VIN_8") (pintype "input"))
      (node (ref "U5") (pin "4") (pinfunction "VCC_4") (pintype "unspecified"))
      (node (ref "U9") (pin "4") (pinfunction "VCC_4") (pintype "unspecified"))
    )
    (net (code "9") (name "ABMF1") (class "Default")
      (node (ref "C6") (pin "2") (pinfunction "2_2") (pintype "unspecified"))
      (node (ref "R3") (pin "1") (pinfunction "1_1") (pintype "unspecified"))
      (node (ref "R4") (pin "1") (pinfunction "1_1") (pintype "input"))
      (node (ref "R5") (pin "2") (pinfunction "2_2") (pintype "input"))
      (node (ref "U1") (pin "22") (pinfunction "PB11_22") (pintype "unspecified"))
    )
    (net (code "10") (name "ABMF2") (class "Default")
      (node (ref "C42") (pin "2") (pinfunction "2_2") (pintype "unspecified"))
      (node (ref "R28") (pin "1") (pinfunction "1_1") (pintype "unspecified"))
      (node (ref "R29") (pin "1") (pinfunction "1_1") (pintype "input"))
      (node (ref "R30") (pin "2") (pinfunction "2_2") (pintype "input"))
      (node (ref "U6") (pin "22") (pinfunction "PB11_22") (pintype "unspecified"))
    )
    (net (code "11") (name "ABMF3") (class "Default")
      (node (ref "C72") (pin "2") (pinfunction "2_2") (pintype "unspecified"))
      (node (ref "R53") (pin "1") (pinfunction "1_1") (pintype "unspecified"))
      (node (ref "R54") (pin "1") (pinfunction "1_1") (pintype "input"))
      (node (ref "R55") (pin "2") (pinfunction "2_2") (pintype "input"))
      (node (ref "U10") (pin "22") (pinfunction "PB11_22") (pintype "unspecified"))
    )
    (net (code "12") (name "ABMF4") (class "Default")
      (node (ref "C102") (pin "2") (pinfunction "2_2") (pintype "unspecified"))
      (node (ref "R78") (pin "1") (pinfunction "1_1") (pintype "unspecified"))
      (node (ref "R79") (pin "1") (pinfunction "1_1") (pintype "input"))
      (node (ref "R80") (pin "2") (pinfunction "2_2") (pintype "input"))
      (node (ref "U14") (pin "22") (pinfunction "PB11_22") (pintype "unspecified"))
    )
    (net (code "13") (name "BATADC1") (class "Default")
      (node (ref "C9") (pin "2") (pinfunction "2_2") (pintype "unspecified"))
      (node (ref "R12") (pin "2") (pinfunction "2_2") (pintype "input"))
      (node (ref "R13") (pin "2") (pinfunction "2_2") (pintype "unspecified"))
      (node (ref "U1") (pin "11") (pinfunction "PA1/ADC1_11") (pintype "unspecified"))
    )
    (net (code "14") (name "BATADC2") (class "Default")
      (node (ref "C45") (pin "2") (pinfunction "2_2") (pintype "unspecified"))
      (node (ref "R37") (pin "2") (pinfunction "2_2") (pintype "input"))
      (node (ref "R38") (pin "2") (pinfunction "2_2") (pintype "unspecified"))
      (node (ref "U6") (pin "11") (pinfunction "PA1/ADC1_11") (pintype "unspecified"))
    )
    (net (code "15") (name "BATADC3") (class "Default")
      (node (ref "C75") (pin "2") (pinfunction "2_2") (pintype "unspecified"))
      (node (ref "R62") (pin "2") (pinfunction "2_2") (pintype "input"))
      (node (ref "R63") (pin "2") (pinfunction "2_2") (pintype "unspecified"))
      (node (ref "U10") (pin "11") (pinfunction "PA1/ADC1_11") (pintype "unspecified"))
    )
    (net (code "16") (name "BATADC4") (class "Default")
      (node (ref "C105") (pin "2") (pinfunction "2_2") (pintype "unspecified"))
      (node (ref "R87") (pin "2") (pinfunction "2_2") (pintype "input"))
      (node (ref "R88") (pin "2") (pinfunction "2_2") (pintype "unspecified"))
      (node (ref "U14") (pin "11") (pinfunction "PA1/ADC1_11") (pintype "unspecified"))
    )
    (net (code "17") (name "BBMF1") (class "Default")
      (node (ref "C7") (pin "2") (pinfunction "2_2") (pintype "unspecified"))
      (node (ref "R6") (pin "1") (pinfunction "1_1") (pintype "unspecified"))
      (node (ref "R7") (pin "1") (pinfunction "1_1") (pintype "input"))
      (node (ref "R8") (pin "2") (pinfunction "2_2") (pintype "input"))
      (node (ref "U1") (pin "21") (pinfunction "PB10_21") (pintype "unspecified"))
    )
    (net (code "18") (name "BBMF2") (class "Default")
      (node (ref "C43") (pin "2") (pinfunction "2_2") (pintype "unspecified"))
      (node (ref "R31") (pin "1") (pinfunction "1_1") (pintype "unspecified"))
      (node (ref "R32") (pin "1") (pinfunction "1_1") (pintype "input"))
      (node (ref "R33") (pin "2") (pinfunction "2_2") (pintype "input"))
      (node (ref "U6") (pin "21") (pinfunction "PB10_21") (pintype "unspecified"))
    )
    (net (code "19") (name "BBMF3") (class "Default")
      (node (ref "C73") (pin "2") (pinfunction "2_2") (pintype "unspecified"))
      (node (ref "R56") (pin "1") (pinfunction "1_1") (pintype "unspecified"))
      (node (ref "R57") (pin "1") (pinfunction "1_1") (pintype "input"))
      (node (ref "R58") (pin "2") (pinfunction "2_2") (pintype "input"))
      (node (ref "U10") (pin "21") (pinfunction "PB10_21") (pintype "unspecified"))
    )
    (net (code "20") (name "BBMF4") (class "Default")
      (node (ref "C103") (pin "2") (pinfunction "2_2") (pintype "unspecified"))
      (node (ref "R81") (pin "1") (pinfunction "1_1") (pintype "unspecified"))
      (node (ref "R82") (pin "1") (pinfunction "1_1") (pintype "input"))
      (node (ref "R83") (pin "2") (pinfunction "2_2") (pintype "input"))
      (node (ref "U14") (pin "21") (pinfunction "PB10_21") (pintype "unspecified"))
    )
    (net (code "21") (name "CBMF1") (class "Default")
      (node (ref "C8") (pin "2") (pinfunction "2_2") (pintype "unspecified"))
      (node (ref "R10") (pin "1") (pinfunction "1_1") (pintype "input"))
      (node (ref "R11") (pin "2") (pinfunction "2_2") (pintype "input"))
      (node (ref "R9") (pin "1") (pinfunction "1_1") (pintype "unspecified"))
      (node (ref "U1") (pin "15") (pinfunction "PA5/ADC5/DAC1_15") (pintype "unspecified"))
    )
    (net (code "22") (name "CBMF2") (class "Default")
      (node (ref "C44") (pin "2") (pinfunction "2_2") (pintype "unspecified"))
      (node (ref "R34") (pin "1") (pinfunction "1_1") (pintype "unspecified"))
      (node (ref "R35") (pin "1") (pinfunction "1_1") (pintype "input"))
      (node (ref "R36") (pin "2") (pinfunction "2_2") (pintype "input"))
      (node (ref "U6") (pin "15") (pinfunction "PA5/ADC5/DAC1_15") (pintype "unspecified"))
    )
    (net (code "23") (name "CBMF3") (class "Default")
      (node (ref "C74") (pin "2") (pinfunction "2_2") (pintype "unspecified"))
      (node (ref "R59") (pin "1") (pinfunction "1_1") (pintype "unspecified"))
      (node (ref "R60") (pin "1") (pinfunction "1_1") (pintype "input"))
      (node (ref "R61") (pin "2") (pinfunction "2_2") (pintype "input"))
      (node (ref "U10") (pin "15") (pinfunction "PA5/ADC5/DAC1_15") (pintype "unspecified"))
    )
    (net (code "24") (name "CBMF4") (class "Default")
      (node (ref "C104") (pin "2") (pinfunction "2_2") (pintype "unspecified"))
      (node (ref "R84") (pin "1") (pinfunction "1_1") (pintype "unspecified"))
      (node (ref "R85") (pin "1") (pinfunction "1_1") (pintype "input"))
      (node (ref "R86") (pin "2") (pinfunction "2_2") (pintype "input"))
      (node (ref "U14") (pin "15") (pinfunction "PA5/ADC5/DAC1_15") (pintype "unspecified"))
    )
    (net (code "25") (name "CLK1") (class "Default")
      (node (ref "U1") (pin "37") (pinfunction "PA14/SWCLK_37") (pintype "unspecified"))
    )
    (net (code "26") (name "CLK2") (class "Default")
      (node (ref "U6") (pin "37") (pinfunction "PA14/SWCLK_37") (pintype "unspecified"))
    )
    (net (code "27") (name "CLK3") (class "Default")
      (node (ref "U10") (pin "37") (pinfunction "PA14/SWCLK_37") (pintype "unspecified"))
    )
    (net (code "28") (name "CLK4") (class "Default")
      (node (ref "U14") (pin "37") (pinfunction "PA14/SWCLK_37") (pintype "unspecified"))
    )
    (net (code "29") (name "CMPO1") (class "Default")
      (node (ref "U1") (pin "12") (pinfunction "PA2/ADC2_12") (pintype "unspecified"))
      (node (ref "U1") (pin "13") (pinfunction "PA3/ADC3_13") (pintype "unspecified"))
      (node (ref "U1") (pin "14") (pinfunction "PA4/ADC4/DAC0_14") (pintype "unspecified"))
    )
    (net (code "30") (name "CMPO2") (class "Default")
      (node (ref "U6") (pin "12") (pinfunction "PA2/ADC2_12") (pintype "unspecified"))
      (node (ref "U6") (pin "13") (pinfunction "PA3/ADC3_13") (pintype "unspecified"))
      (node (ref "U6") (pin "14") (pinfunction "PA4/ADC4/DAC0_14") (pintype "unspecified"))
    )
    (net (code "31") (name "CMPO3") (class "Default")
      (node (ref "U10") (pin "12") (pinfunction "PA2/ADC2_12") (pintype "unspecified"))
      (node (ref "U10") (pin "13") (pinfunction "PA3/ADC3_13") (pintype "unspecified"))
      (node (ref "U10") (pin "14") (pinfunction "PA4/ADC4/DAC0_14") (pintype "unspecified"))
    )
    (net (code "32") (name "CMPO4") (class "Default")
      (node (ref "U14") (pin "12") (pinfunction "PA2/ADC2_12") (pintype "unspecified"))
      (node (ref "U14") (pin "13") (pinfunction "PA3/ADC3_13") (pintype "unspecified"))
      (node (ref "U14") (pin "14") (pinfunction "PA4/ADC4/DAC0_14") (pintype "unspecified"))
    )
    (net (code "33") (name "DIO1") (class "Default")
      (node (ref "U1") (pin "34") (pinfunction "PA13/SWDIO_34") (pintype "unspecified"))
    )
    (net (code "34") (name "DIO2") (class "Default")
      (node (ref "U6") (pin "34") (pinfunction "PA13/SWDIO_34") (pintype "unspecified"))
    )
    (net (code "35") (name "DIO3") (class "Default")
      (node (ref "U10") (pin "34") (pinfunction "PA13/SWDIO_34") (pintype "unspecified"))
    )
    (net (code "36") (name "DIO4") (class "Default")
      (node (ref "U14") (pin "34") (pinfunction "PA13/SWDIO_34") (pintype "unspecified"))
    )
    (net (code "37") (name "ERR1") (class "Default")
      (node (ref "LED1") (pin "1") (pinfunction "K_1") (pintype "unspecified"))
      (node (ref "U1") (pin "45") (pinfunction "PB8_45") (pintype "unspecified"))
    )
    (net (code "38") (name "ERR2") (class "Default")
      (node (ref "LED3") (pin "1") (pinfunction "K_1") (pintype "unspecified"))
      (node (ref "U6") (pin "45") (pinfunction "PB8_45") (pintype "unspecified"))
    )
    (net (code "39") (name "ERR3") (class "Default")
      (node (ref "LED5") (pin "1") (pinfunction "K_1") (pintype "unspecified"))
      (node (ref "U10") (pin "45") (pinfunction "PB8_45") (pintype "unspecified"))
    )
    (net (code "40") (name "ERR4") (class "Default")
      (node (ref "LED7") (pin "1") (pinfunction "K_1") (pintype "unspecified"))
      (node (ref "U14") (pin "45") (pinfunction "PB8_45") (pintype "unspecified"))
    )
    (net (code "41") (name "FB1") (class "Default")
      (node (ref "R18") (pin "1") (pinfunction "1_1") (pintype "input"))
      (node (ref "R19") (pin "2") (pinfunction "2_2") (pintype "input"))
      (node (ref "U3") (pin "5") (pinfunction "FB_5") (pintype "input"))
    )
    (net (code "42") (name "FB2") (class "Default")
      (node (ref "R68") (pin "1") (pinfunction "1_1") (pintype "input"))
      (node (ref "R69") (pin "2") (pinfunction "2_2") (pintype "input"))
      (node (ref "U11") (pin "5") (pinfunction "FB_5") (pintype "input"))
    )
    (net (code "43") (name "GND") (class "Default")
      (node (ref "C1") (pin "1") (pinfunction "1_1") (pintype "unspecified"))
      (node (ref "C100") (pin "1") (pinfunction "1_1") (pintype "input"))
      (node (ref "C101") (pin "1") (pinfunction "1_1") (pintype "unspecified"))
      (node (ref "C102") (pin "1") (pinfunction "1_1") (pintype "unspecified"))
      (node (ref "C103") (pin "1") (pinfunction "1_1") (pintype "unspecified"))
      (node (ref "C104") (pin "1") (pinfunction "1_1") (pintype "unspecified"))
      (node (ref "C105") (pin "1") (pinfunction "1_1") (pintype "unspecified"))
      (node (ref "C121") (pin "1") (pinfunction "1_1") (pintype "unspecified"))
      (node (ref "C122") (pin "1") (pinfunction "1_1") (pintype "unspecified"))
      (node (ref "C18") (pin "1") (pinfunction "1_1") (pintype "unspecified"))
      (node (ref "C19") (pin "1") (pinfunction "1_1") (pintype "unspecified"))
      (node (ref "C2") (pin "1") (pinfunction "1_1") (pintype "unspecified"))
      (node (ref "C20") (pin "1") (pinfunction "1_1") (pintype "unspecified"))
      (node (ref "C21") (pin "1") (pinfunction "1_1") (pintype "unspecified"))
      (node (ref "C25") (pin "1") (pinfunction "1_1") (pintype "input"))
      (node (ref "C26") (pin "1") (pinfunction "1_1") (pintype "unspecified"))
      (node (ref "C27") (pin "1") (pinfunction "1_1") (pintype "unspecified"))
      (node (ref "C3") (pin "1") (pinfunction "1_1") (pintype "unspecified"))
      (node (ref "C37") (pin "1") (pinfunction "1_1") (pintype "unspecified"))
      (node (ref "C38") (pin "1") (pinfunction "1_1") (pintype "unspecified"))
      (node (ref "C39") (pin "2") (pinfunction "2_2") (pintype "unspecified"))
      (node (ref "C4") (pin "2") (pinfunction "2_2") (pintype "unspecified"))
      (node (ref "C40") (pin "1") (pinfunction "1_1") (pintype "input"))
      (node (ref "C41") (pin "1") (pinfunction "1_1") (pintype "unspecified"))
      (node (ref "C42") (pin "1") (pinfunction "1_1") (pintype "unspecified"))
      (node (ref "C43") (pin "1") (pinfunction "1_1") (pintype "unspecified"))
      (node (ref "C44") (pin "1") (pinfunction "1_1") (pintype "unspecified"))
      (node (ref "C45") (pin "1") (pinfunction "1_1") (pintype "unspecified"))
      (node (ref "C5") (pin "1") (pinfunction "1_1") (pintype "input"))
      (node (ref "C6") (pin "1") (pinfunction "1_1") (pintype "unspecified"))
      (node (ref "C61") (pin "1") (pinfunction "1_1") (pintype "unspecified"))
      (node (ref "C62") (pin "1") (pinfunction "1_1") (pintype "unspecified"))
      (node (ref "C67") (pin "1") (pinfunction "1_1") (pintype "unspecified"))
      (node (ref "C68") (pin "1") (pinfunction "1_1") (pintype "unspecified"))
      (node (ref "C69") (pin "2") (pinfunction "2_2") (pintype "unspecified"))
      (node (ref "C7") (pin "1") (pinfunction "1_1") (pintype "unspecified"))
      (node (ref "C70") (pin "1") (pinfunction "1_1") (pintype "input"))
      (node (ref "C71") (pin "1") (pinfunction "1_1") (pintype "unspecified"))
      (node (ref "C72") (pin "1") (pinfunction "1_1") (pintype "unspecified"))
      (node (ref "C73") (pin "1") (pinfunction "1_1") (pintype "unspecified"))
      (node (ref "C74") (pin "1") (pinfunction "1_1") (pintype "unspecified"))
      (node (ref "C75") (pin "1") (pinfunction "1_1") (pintype "unspecified"))
      (node (ref "C8") (pin "1") (pinfunction "1_1") (pintype "unspecified"))
      (node (ref "C84") (pin "1") (pinfunction "1_1") (pintype "unspecified"))
      (node (ref "C85") (pin "1") (pinfunction "1_1") (pintype "unspecified"))
      (node (ref "C86") (pin "1") (pinfunction "1_1") (pintype "unspecified"))
      (node (ref "C87") (pin "1") (pinfunction "1_1") (pintype "unspecified"))
      (node (ref "C88") (pin "1") (pinfunction "1_1") (pintype "unspecified"))
      (node (ref "C89") (pin "1") (pinfunction "1_1") (pintype "unspecified"))
      (node (ref "C9") (pin "1") (pinfunction "1_1") (pintype "unspecified"))
      (node (ref "C90") (pin "1") (pinfunction "1_1") (pintype "input"))
      (node (ref "C91") (pin "1") (pinfunction "1_1") (pintype "unspecified"))
      (node (ref "C92") (pin "1") (pinfunction "1_1") (pintype "unspecified"))
      (node (ref "C97") (pin "1") (pinfunction "1_1") (pintype "unspecified"))
      (node (ref "C98") (pin "1") (pinfunction "1_1") (pintype "unspecified"))
      (node (ref "C99") (pin "2") (pinfunction "2_2") (pintype "unspecified"))
      (node (ref "L11") (pin "1") (pinfunction "1_1") (pintype "unspecified"))
      (node (ref "L2") (pin "1") (pinfunction "1_1") (pintype "unspecified"))
      (node (ref "L5") (pin "1") (pinfunction "1_1") (pintype "unspecified"))
      (node (ref "L8") (pin "1") (pinfunction "1_1") (pintype "unspecified"))
      (node (ref "R1") (pin "2") (pinfunction "2_2") (pintype "unspecified"))
      (node (ref "R105") (pin "1") (pinfunction "1_1") (pintype "input"))
      (node (ref "R106") (pin "1") (pinfunction "1_1") (pintype "input"))
      (node (ref "R107") (pin "1") (pinfunction "1_1") (pintype "input"))
      (node (ref "R11") (pin "1") (pinfunction "1_1") (pintype "input"))
      (node (ref "R13") (pin "1") (pinfunction "1_1") (pintype "unspecified"))
      (node (ref "R17") (pin "1") (pinfunction "1_1") (pintype "input"))
      (node (ref "R19") (pin "1") (pinfunction "1_1") (pintype "input"))
      (node (ref "R27") (pin "2") (pinfunction "2_2") (pintype "unspecified"))
      (node (ref "R30") (pin "1") (pinfunction "1_1") (pintype "input"))
      (node (ref "R33") (pin "1") (pinfunction "1_1") (pintype "input"))
      (node (ref "R36") (pin "1") (pinfunction "1_1") (pintype "input"))
      (node (ref "R38") (pin "1") (pinfunction "1_1") (pintype "unspecified"))
      (node (ref "R5") (pin "1") (pinfunction "1_1") (pintype "input"))
      (node (ref "R52") (pin "2") (pinfunction "2_2") (pintype "unspecified"))
      (node (ref "R55") (pin "1") (pinfunction "1_1") (pintype "input"))
      (node (ref "R58") (pin "1") (pinfunction "1_1") (pintype "input"))
      (node (ref "R61") (pin "1") (pinfunction "1_1") (pintype "input"))
      (node (ref "R63") (pin "1") (pinfunction "1_1") (pintype "unspecified"))
      (node (ref "R67") (pin "1") (pinfunction "1_1") (pintype "input"))
      (node (ref "R69") (pin "1") (pinfunction "1_1") (pintype "input"))
      (node (ref "R77") (pin "2") (pinfunction "2_2") (pintype "unspecified"))
      (node (ref "R8") (pin "1") (pinfunction "1_1") (pintype "input"))
      (node (ref "R80") (pin "1") (pinfunction "1_1") (pintype "input"))
      (node (ref "R83") (pin "1") (pinfunction "1_1") (pintype "input"))
      (node (ref "R86") (pin "1") (pinfunction "1_1") (pintype "input"))
      (node (ref "R88") (pin "1") (pinfunction "1_1") (pintype "unspecified"))
      (node (ref "U1") (pin "23") (pinfunction "VSS_1_23") (pintype "unspecified"))
      (node (ref "U1") (pin "35") (pinfunction "VSS_2_35") (pintype "unspecified"))
      (node (ref "U1") (pin "47") (pinfunction "VSS_3_47") (pintype "unspecified"))
      (node (ref "U10") (pin "23") (pinfunction "VSS_1_23") (pintype "unspecified"))
      (node (ref "U10") (pin "35") (pinfunction "VSS_2_35") (pintype "unspecified"))
      (node (ref "U10") (pin "47") (pinfunction "VSS_3_47") (pintype "unspecified"))
      (node (ref "U12") (pin "2") (pinfunction "GND_2") (pintype "unspecified"))
      (node (ref "U14") (pin "23") (pinfunction "VSS_1_23") (pintype "unspecified"))
      (node (ref "U14") (pin "35") (pinfunction "VSS_2_35") (pintype "unspecified"))
      (node (ref "U14") (pin "47") (pinfunction "VSS_3_47") (pintype "unspecified"))
      (node (ref "U16") (pin "2") (pinfunction "GND_2") (pintype "unspecified"))
      (node (ref "U4") (pin "2") (pinfunction "GND_2") (pintype "unspecified"))
      (node (ref "U6") (pin "23") (pinfunction "VSS_1_23") (pintype "unspecified"))
      (node (ref "U6") (pin "35") (pinfunction "VSS_2_35") (pintype "unspecified"))
      (node (ref "U6") (pin "47") (pinfunction "VSS_3_47") (pintype "unspecified"))
      (node (ref "U8") (pin "2") (pinfunction "GND_2") (pintype "unspecified"))
    )
    (net (code "44") (name "HOA1") (class "Default")
      (node (ref "R20") (pin "2") (pinfunction "2_2") (pintype "input"))
      (node (ref "U5") (pin "19") (pinfunction "HO1_19") (pintype "unspecified"))
    )
    (net (code "45") (name "HOA2") (class "Default")
      (node (ref "R45") (pin "2") (pinfunction "2_2") (pintype "input"))
      (node (ref "U9") (pin "19") (pinfunction "HO1_19") (pintype "unspecified"))
    )
    (net (code "46") (name "HOA3") (class "Default")
      (node (ref "R70") (pin "2") (pinfunction "2_2") (pintype "input"))
      (node (ref "U13") (pin "19") (pinfunction "HO1_19") (pintype "unspecified"))
    )
    (net (code "47") (name "HOA4") (class "Default")
      (node (ref "R95") (pin "2") (pinfunction "2_2") (pintype "input"))
      (node (ref "U17") (pin "19") (pinfunction "HO1_19") (pintype "unspecified"))
    )
    (net (code "48") (name "HOB1") (class "Default")
      (node (ref "R22") (pin "2") (pinfunction "2_2") (pintype "input"))
      (node (ref "U5") (pin "16") (pinfunction "HO2_16") (pintype "unspecified"))
    )
    (net (code "49") (name "HOB2") (class "Default")
      (node (ref "R47") (pin "2") (pinfunction "2_2") (pintype "input"))
      (node (ref "U9") (pin "16") (pinfunction "HO2_16") (pintype "unspecified"))
    )
    (net (code "50") (name "HOB3") (class "Default")
      (node (ref "R72") (pin "2") (pinfunction "2_2") (pintype "input"))
      (node (ref "U13") (pin "16") (pinfunction "HO2_16") (pintype "unspecified"))
    )
    (net (code "51") (name "HOB4") (class "Default")
      (node (ref "R97") (pin "2") (pinfunction "2_2") (pintype "input"))
      (node (ref "U17") (pin "16") (pinfunction "HO2_16") (pintype "unspecified"))
    )
    (net (code "52") (name "HOC1") (class "Default")
      (node (ref "R24") (pin "2") (pinfunction "2_2") (pintype "input"))
      (node (ref "U5") (pin "13") (pinfunction "HO3_13") (pintype "unspecified"))
    )
    (net (code "53") (name "HOC2") (class "Default")
      (node (ref "R49") (pin "2") (pinfunction "2_2") (pintype "input"))
      (node (ref "U9") (pin "13") (pinfunction "HO3_13") (pintype "unspecified"))
    )
    (net (code "54") (name "HOC3") (class "Default")
      (node (ref "R74") (pin "2") (pinfunction "2_2") (pintype "input"))
      (node (ref "U13") (pin "13") (pinfunction "HO3_13") (pintype "unspecified"))
    )
    (net (code "55") (name "HOC4") (class "Default")
      (node (ref "R99") (pin "2") (pinfunction "2_2") (pintype "input"))
      (node (ref "U17") (pin "13") (pinfunction "HO3_13") (pintype "unspecified"))
    )
    (net (code "56") (name "LOA1") (class "Default")
      (node (ref "R21") (pin "2") (pinfunction "2_2") (pintype "input"))
      (node (ref "U5") (pin "11") (pinfunction "LO1_11") (pintype "unspecified"))
    )
    (net (code "57") (name "LOA2") (class "Default")
      (node (ref "R46") (pin "2") (pinfunction "2_2") (pintype "input"))
      (node (ref "U9") (pin "11") (pinfunction "LO1_11") (pintype "unspecified"))
    )
    (net (code "58") (name "LOA3") (class "Default")
      (node (ref "R71") (pin "2") (pinfunction "2_2") (pintype "input"))
      (node (ref "U13") (pin "11") (pinfunction "LO1_11") (pintype "unspecified"))
    )
    (net (code "59") (name "LOA4") (class "Default")
      (node (ref "R96") (pin "2") (pinfunction "2_2") (pintype "input"))
      (node (ref "U17") (pin "11") (pinfunction "LO1_11") (pintype "unspecified"))
    )
    (net (code "60") (name "LOB1") (class "Default")
      (node (ref "R23") (pin "2") (pinfunction "2_2") (pintype "input"))
      (node (ref "U5") (pin "10") (pinfunction "LO2_10") (pintype "unspecified"))
    )
    (net (code "61") (name "LOB2") (class "Default")
      (node (ref "R48") (pin "2") (pinfunction "2_2") (pintype "input"))
      (node (ref "U9") (pin "10") (pinfunction "LO2_10") (pintype "unspecified"))
    )
    (net (code "62") (name "LOB3") (class "Default")
      (node (ref "R73") (pin "2") (pinfunction "2_2") (pintype "input"))
      (node (ref "U13") (pin "10") (pinfunction "LO2_10") (pintype "unspecified"))
    )
    (net (code "63") (name "LOB4") (class "Default")
      (node (ref "R98") (pin "2") (pinfunction "2_2") (pintype "input"))
      (node (ref "U17") (pin "10") (pinfunction "LO2_10") (pintype "unspecified"))
    )
    (net (code "64") (name "LOC1") (class "Default")
      (node (ref "R25") (pin "2") (pinfunction "2_2") (pintype "input"))
      (node (ref "U5") (pin "9") (pinfunction "LO3_9") (pintype "unspecified"))
    )
    (net (code "65") (name "LOC2") (class "Default")
      (node (ref "R50") (pin "2") (pinfunction "2_2") (pintype "input"))
      (node (ref "U9") (pin "9") (pinfunction "LO3_9") (pintype "unspecified"))
    )
    (net (code "66") (name "LOC3") (class "Default")
      (node (ref "R75") (pin "2") (pinfunction "2_2") (pintype "input"))
      (node (ref "U13") (pin "9") (pinfunction "LO3_9") (pintype "unspecified"))
    )
    (net (code "67") (name "LOC4") (class "Default")
      (node (ref "R100") (pin "2") (pinfunction "2_2") (pintype "input"))
      (node (ref "U17") (pin "9") (pinfunction "LO3_9") (pintype "unspecified"))
    )
    (net (code "68") (name "MID1") (class "Default")
      (node (ref "R10") (pin "2") (pinfunction "2_2") (pintype "input"))
      (node (ref "R4") (pin "2") (pinfunction "2_2") (pintype "input"))
      (node (ref "R7") (pin "2") (pinfunction "2_2") (pintype "input"))
      (node (ref "U1") (pin "27") (pinfunction "PB14_27") (pintype "unspecified"))
      (node (ref "U1") (pin "28") (pinfunction "PB15_28") (pintype "unspecified"))
    )
    (net (code "69") (name "MID2") (class "Default")
      (node (ref "R29") (pin "2") (pinfunction "2_2") (pintype "input"))
      (node (ref "R32") (pin "2") (pinfunction "2_2") (pintype "input"))
      (node (ref "R35") (pin "2") (pinfunction "2_2") (pintype "input"))
      (node (ref "U6") (pin "27") (pinfunction "PB14_27") (pintype "unspecified"))
      (node (ref "U6") (pin "28") (pinfunction "PB15_28") (pintype "unspecified"))
    )
    (net (code "70") (name "MID3") (class "Default")
      (node (ref "R54") (pin "2") (pinfunction "2_2") (pintype "input"))
      (node (ref "R57") (pin "2") (pinfunction "2_2") (pintype "input"))
      (node (ref "R60") (pin "2") (pinfunction "2_2") (pintype "input"))
      (node (ref "U10") (pin "27") (pinfunction "PB14_27") (pintype "unspecified"))
      (node (ref "U10") (pin "28") (pinfunction "PB15_28") (pintype "unspecified"))
    )
    (net (code "71") (name "MID4") (class "Default")
      (node (ref "R79") (pin "2") (pinfunction "2_2") (pintype "input"))
      (node (ref "R82") (pin "2") (pinfunction "2_2") (pintype "input"))
      (node (ref "R85") (pin "2") (pinfunction "2_2") (pintype "input"))
      (node (ref "U14") (pin "27") (pinfunction "PB14_27") (pintype "unspecified"))
      (node (ref "U14") (pin "28") (pinfunction "PB15_28") (pintype "unspecified"))
    )
    (net (code "72") (name "NRST1") (class "Default")
      (node (ref "C5") (pin "2") (pinfunction "2_2") (pintype "input"))
      (node (ref "R2") (pin "1") (pinfunction "1_1") (pintype "unspecified"))
      (node (ref "U1") (pin "7") (pinfunction "NRST_7") (pintype "unspecified"))
    )
    (net (code "73") (name "NRST2") (class "Default")
      (node (ref "C40") (pin "2") (pinfunction "2_2") (pintype "input"))
      (node (ref "R26") (pin "1") (pinfunction "1_1") (pintype "unspecified"))
      (node (ref "U6") (pin "7") (pinfunction "NRST_7") (pintype "unspecified"))
    )
    (net (code "74") (name "NRST3") (class "Default")
      (node (ref "C70") (pin "2") (pinfunction "2_2") (pintype "input"))
      (node (ref "R51") (pin "1") (pinfunction "1_1") (pintype "unspecified"))
      (node (ref "U10") (pin "7") (pinfunction "NRST_7") (pintype "unspecified"))
    )
    (net (code "75") (name "NRST4") (class "Default")
      (node (ref "C100") (pin "2") (pinfunction "2_2") (pintype "input"))
      (node (ref "R76") (pin "1") (pinfunction "1_1") (pintype "unspecified"))
      (node (ref "U14") (pin "7") (pinfunction "NRST_7") (pintype "unspecified"))
    )
    (net (code "76") (name "Net-(D2-K)") (class "Default")
      (node (ref "C34") (pin "2") (pinfunction "2_2") (pintype "input"))
      (node (ref "D2") (pin "2") (pinfunction "K_2") (pintype "unspecified"))
      (node (ref "U5") (pin "17") (pinfunction "VB2_17") (pintype "unspecified"))
    )
    (net (code "77") (name "Net-(D3-K)") (class "Default")
      (node (ref "C35") (pin "2") (pinfunction "2_2") (pintype "input"))
      (node (ref "D3") (pin "2") (pinfunction "K_2") (pintype "unspecified"))
      (node (ref "U5") (pin "14") (pinfunction "VB3_14") (pintype "unspecified"))
    )
    (net (code "78") (name "Net-(D4-K)") (class "Default")
      (node (ref "C33") (pin "2") (pinfunction "2_2") (pintype "input"))
      (node (ref "D4") (pin "2") (pinfunction "K_2") (pintype "unspecified"))
      (node (ref "U5") (pin "20") (pinfunction "VB1_20") (pintype "unspecified"))
    )
    (net (code "79") (name "Net-(D6-K)") (class "Default")
      (node (ref "C63") (pin "2") (pinfunction "2_2") (pintype "input"))
      (node (ref "D6") (pin "2") (pinfunction "K_2") (pintype "unspecified"))
      (node (ref "U9") (pin "20") (pinfunction "VB1_20") (pintype "unspecified"))
    )
    (net (code "80") (name "Net-(D7-K)") (class "Default")
      (node (ref "C64") (pin "2") (pinfunction "2_2") (pintype "input"))
      (node (ref "D7") (pin "2") (pinfunction "K_2") (pintype "unspecified"))
      (node (ref "U9") (pin "17") (pinfunction "VB2_17") (pintype "unspecified"))
    )
    (net (code "81") (name "Net-(D8-K)") (class "Default")
      (node (ref "C65") (pin "2") (pinfunction "2_2") (pintype "input"))
      (node (ref "D8") (pin "2") (pinfunction "K_2") (pintype "unspecified"))
      (node (ref "U9") (pin "14") (pinfunction "VB3_14") (pintype "unspecified"))
    )
    (net (code "82") (name "Net-(D10-K)") (class "Default")
      (node (ref "C93") (pin "2") (pinfunction "2_2") (pintype "input"))
      (node (ref "D10") (pin "2") (pinfunction "K_2") (pintype "unspecified"))
      (node (ref "U13") (pin "20") (pinfunction "VB1_20") (pintype "unspecified"))
    )
    (net (code "83") (name "Net-(D11-K)") (class "Default")
      (node (ref "C94") (pin "2") (pinfunction "2_2") (pintype "input"))
      (node (ref "D11") (pin "2") (pinfunction "K_2") (pintype "unspecified"))
      (node (ref "U13") (pin "17") (pinfunction "VB2_17") (pintype "unspecified"))
    )
    (net (code "84") (name "Net-(D12-K)") (class "Default")
      (node (ref "C95") (pin "2") (pinfunction "2_2") (pintype "input"))
      (node (ref "D12") (pin "2") (pinfunction "K_2") (pintype "unspecified"))
      (node (ref "U13") (pin "14") (pinfunction "VB3_14") (pintype "unspecified"))
    )
    (net (code "85") (name "Net-(D14-K)") (class "Default")
      (node (ref "C123") (pin "2") (pinfunction "2_2") (pintype "input"))
      (node (ref "D14") (pin "2") (pinfunction "K_2") (pintype "unspecified"))
      (node (ref "U17") (pin "20") (pinfunction "VB1_20") (pintype "unspecified"))
    )
    (net (code "86") (name "Net-(D15-K)") (class "Default")
      (node (ref "C124") (pin "2") (pinfunction "2_2") (pintype "input"))
      (node (ref "D15") (pin "2") (pinfunction "K_2") (pintype "unspecified"))
      (node (ref "U17") (pin "17") (pinfunction "VB2_17") (pintype "unspecified"))
    )
    (net (code "87") (name "Net-(D16-K)") (class "Default")
      (node (ref "C125") (pin "2") (pinfunction "2_2") (pintype "input"))
      (node (ref "D16") (pin "2") (pinfunction "K_2") (pintype "unspecified"))
      (node (ref "U17") (pin "14") (pinfunction "VB3_14") (pintype "unspecified"))
    )
    (net (code "88") (name "Net-(LED1-A)") (class "Default")
      (node (ref "LED1") (pin "2") (pinfunction "A_2") (pintype "unspecified"))
      (node (ref "R14") (pin "1") (pinfunction "1_1") (pintype "input"))
    )
    (net (code "89") (name "Net-(LED2-A)") (class "Default")
      (node (ref "LED2") (pin "2") (pinfunction "A_2") (pintype "unspecified"))
      (node (ref "R15") (pin "2") (pinfunction "2_2") (pintype "input"))
    )
    (net (code "90") (name "Net-(LED3-A)") (class "Default")
      (node (ref "LED3") (pin "2") (pinfunction "A_2") (pintype "unspecified"))
      (node (ref "R39") (pin "1") (pinfunction "1_1") (pintype "input"))
    )
    (net (code "91") (name "Net-(LED4-A)") (class "Default")
      (node (ref "LED4") (pin "2") (pinfunction "A_2") (pintype "unspecified"))
      (node (ref "R40") (pin "2") (pinfunction "2_2") (pintype "input"))
    )
    (net (code "92") (name "Net-(LED5-A)") (class "Default")
      (node (ref "LED5") (pin "2") (pinfunction "A_2") (pintype "unspecified"))
      (node (ref "R64") (pin "1") (pinfunction "1_1") (pintype "input"))
    )
    (net (code "93") (name "Net-(LED6-A)") (class "Default")
      (node (ref "LED6") (pin "2") (pinfunction "A_2") (pintype "unspecified"))
      (node (ref "R65") (pin "2") (pinfunction "2_2") (pintype "input"))
    )
    (net (code "94") (name "Net-(LED7-A)") (class "Default")
      (node (ref "LED7") (pin "2") (pinfunction "A_2") (pintype "unspecified"))
      (node (ref "R89") (pin "1") (pinfunction "1_1") (pintype "input"))
    )
    (net (code "95") (name "Net-(LED8-A)") (class "Default")
      (node (ref "LED8") (pin "2") (pinfunction "A_2") (pintype "unspecified"))
      (node (ref "R90") (pin "2") (pinfunction "2_2") (pintype "input"))
    )
    (net (code "96") (name "Net-(Q1-G)") (class "Default")
      (node (ref "Q1") (pin "4") (pinfunction "G_4") (pintype "unspecified"))
      (node (ref "R20") (pin "1") (pinfunction "1_1") (pintype "input"))
    )
    (net (code "97") (name "Net-(Q2-G)") (class "Default")
      (node (ref "Q2") (pin "4") (pinfunction "G_4") (pintype "unspecified"))
      (node (ref "R21") (pin "1") (pinfunction "1_1") (pintype "input"))
    )
    (net (code "98") (name "Net-(Q3-G)") (class "Default")
      (node (ref "Q3") (pin "4") (pinfunction "G_4") (pintype "unspecified"))
      (node (ref "R22") (pin "1") (pinfunction "1_1") (pintype "input"))
    )
    (net (code "99") (name "Net-(Q4-G)") (class "Default")
      (node (ref "Q4") (pin "4") (pinfunction "G_4") (pintype "unspecified"))
      (node (ref "R23") (pin "1") (pinfunction "1_1") (pintype "input"))
    )
    (net (code "100") (name "Net-(Q5-G)") (class "Default")
      (node (ref "Q5") (pin "4") (pinfunction "G_4") (pintype "unspecified"))
      (node (ref "R24") (pin "1") (pinfunction "1_1") (pintype "input"))
    )
    (net (code "101") (name "Net-(Q6-G)") (class "Default")
      (node (ref "Q6") (pin "4") (pinfunction "G_4") (pintype "unspecified"))
      (node (ref "R25") (pin "1") (pinfunction "1_1") (pintype "input"))
    )
    (net (code "102") (name "Net-(Q7-G)") (class "Default")
      (node (ref "Q7") (pin "4") (pinfunction "G_4") (pintype "unspecified"))
      (node (ref "R45") (pin "1") (pinfunction "1_1") (pintype "input"))
    )
    (net (code "103") (name "Net-(Q8-G)") (class "Default")
      (node (ref "Q8") (pin "4") (pinfunction "G_4") (pintype "unspecified"))
      (node (ref "R46") (pin "1") (pinfunction "1_1") (pintype "input"))
    )
    (net (code "104") (name "Net-(Q9-G)") (class "Default")
      (node (ref "Q9") (pin "4") (pinfunction "G_4") (pintype "unspecified"))
      (node (ref "R47") (pin "1") (pinfunction "1_1") (pintype "input"))
    )
    (net (code "105") (name "Net-(Q10-G)") (class "Default")
      (node (ref "Q10") (pin "4") (pinfunction "G_4") (pintype "unspecified"))
      (node (ref "R48") (pin "1") (pinfunction "1_1") (pintype "input"))
    )
    (net (code "106") (name "Net-(Q11-G)") (class "Default")
      (node (ref "Q11") (pin "4") (pinfunction "G_4") (pintype "unspecified"))
      (node (ref "R49") (pin "1") (pinfunction "1_1") (pintype "input"))
    )
    (net (code "107") (name "Net-(Q12-G)") (class "Default")
      (node (ref "Q12") (pin "4") (pinfunction "G_4") (pintype "unspecified"))
      (node (ref "R50") (pin "1") (pinfunction "1_1") (pintype "input"))
    )
    (net (code "108") (name "Net-(Q13-G)") (class "Default")
      (node (ref "Q13") (pin "4") (pinfunction "G_4") (pintype "unspecified"))
      (node (ref "R70") (pin "1") (pinfunction "1_1") (pintype "input"))
    )
    (net (code "109") (name "Net-(Q14-G)") (class "Default")
      (node (ref "Q14") (pin "4") (pinfunction "G_4") (pintype "unspecified"))
      (node (ref "R71") (pin "1") (pinfunction "1_1") (pintype "input"))
    )
    (net (code "110") (name "Net-(Q15-G)") (class "Default")
      (node (ref "Q15") (pin "4") (pinfunction "G_4") (pintype "unspecified"))
      (node (ref "R72") (pin "1") (pinfunction "1_1") (pintype "input"))
    )
    (net (code "111") (name "Net-(Q16-G)") (class "Default")
      (node (ref "Q16") (pin "4") (pinfunction "G_4") (pintype "unspecified"))
      (node (ref "R73") (pin "1") (pinfunction "1_1") (pintype "input"))
    )
    (net (code "112") (name "Net-(Q17-G)") (class "Default")
      (node (ref "Q17") (pin "4") (pinfunction "G_4") (pintype "unspecified"))
      (node (ref "R74") (pin "1") (pinfunction "1_1") (pintype "input"))
    )
    (net (code "113") (name "Net-(Q18-G)") (class "Default")
      (node (ref "Q18") (pin "4") (pinfunction "G_4") (pintype "unspecified"))
      (node (ref "R75") (pin "1") (pinfunction "1_1") (pintype "input"))
    )
    (net (code "114") (name "Net-(Q19-G)") (class "Default")
      (node (ref "Q19") (pin "4") (pinfunction "G_4") (pintype "unspecified"))
      (node (ref "R95") (pin "1") (pinfunction "1_1") (pintype "input"))
    )
    (net (code "115") (name "Net-(Q20-G)") (class "Default")
      (node (ref "Q20") (pin "4") (pinfunction "G_4") (pintype "unspecified"))
      (node (ref "R96") (pin "1") (pinfunction "1_1") (pintype "input"))
    )
    (net (code "116") (name "Net-(Q21-G)") (class "Default")
      (node (ref "Q21") (pin "4") (pinfunction "G_4") (pintype "unspecified"))
      (node (ref "R97") (pin "1") (pinfunction "1_1") (pintype "input"))
    )
    (net (code "117") (name "Net-(Q22-G)") (class "Default")
      (node (ref "Q22") (pin "4") (pinfunction "G_4") (pintype "unspecified"))
      (node (ref "R98") (pin "1") (pinfunction "1_1") (pintype "input"))
    )
    (net (code "118") (name "Net-(Q23-G)") (class "Default")
      (node (ref "Q23") (pin "4") (pinfunction "G_4") (pintype "unspecified"))
      (node (ref "R99") (pin "1") (pinfunction "1_1") (pintype "input"))
    )
    (net (code "119") (name "Net-(Q24-G)") (class "Default")
      (node (ref "Q24") (pin "4") (pinfunction "G_4") (pintype "unspecified"))
      (node (ref "R100") (pin "1") (pinfunction "1_1") (pintype "input"))
    )
    (net (code "120") (name "Net-(U1-BOOT0)") (class "Default")
      (node (ref "R1") (pin "1") (pinfunction "1_1") (pintype "unspecified"))
      (node (ref "U1") (pin "44") (pinfunction "BOOT0_44") (pintype "unspecified"))
    )
    (net (code "121") (name "Net-(U1-VDDA)") (class "Default")
      (node (ref "C2") (pin "2") (pinfunction "2_2") (pintype "unspecified"))
      (node (ref "L1") (pin "1") (pinfunction "1_1") (pintype "unspecified"))
      (node (ref "U1") (pin "9") (pinfunction "VDDA_9") (pintype "unspecified"))
    )
    (net (code "122") (name "Net-(U1-VSSA)") (class "Default")
      (node (ref "L2") (pin "2") (pinfunction "2_2") (pintype "unspecified"))
      (node (ref "U1") (pin "8") (pinfunction "VSSA_8") (pintype "unspecified"))
    )
    (net (code "123") (name "Net-(U3-BS)") (class "Default")
      (node (ref "C17") (pin "2") (pinfunction "2_2") (pintype "unspecified"))
      (node (ref "U3") (pin "1") (pinfunction "BS_1") (pintype "input"))
    )
    (net (code "124") (name "Net-(U3-EN)") (class "Default")
      (node (ref "R16") (pin "1") (pinfunction "1_1") (pintype "input"))
      (node (ref "U3") (pin "3") (pinfunction "EN_3") (pintype "input"))
    )
    (net (code "125") (name "Net-(U3-LX)") (class "Default")
      (node (ref "C17") (pin "1") (pinfunction "1_1") (pintype "unspecified"))
      (node (ref "L3") (pin "2") (pinfunction "2_2") (pintype "unspecified"))
      (node (ref "U3") (pin "2") (pinfunction "LX_2") (pintype "input"))
    )
    (net (code "126") (name "Net-(U3-SS)") (class "Default")
      (node (ref "C18") (pin "2") (pinfunction "2_2") (pintype "unspecified"))
      (node (ref "U3") (pin "4") (pinfunction "SS_4") (pintype "input"))
    )
    (net (code "127") (name "Net-(U3-VCC)") (class "Default")
      (node (ref "C21") (pin "2") (pinfunction "2_2") (pintype "unspecified"))
      (node (ref "U3") (pin "6") (pinfunction "VCC_6") (pintype "input"))
    )
    (net (code "128") (name "Net-(U6-BOOT0)") (class "Default")
      (node (ref "R27") (pin "1") (pinfunction "1_1") (pintype "unspecified"))
      (node (ref "U6") (pin "44") (pinfunction "BOOT0_44") (pintype "unspecified"))
    )
    (net (code "129") (name "Net-(U6-VDDA)") (class "Default")
      (node (ref "C37") (pin "2") (pinfunction "2_2") (pintype "unspecified"))
      (node (ref "L4") (pin "1") (pinfunction "1_1") (pintype "unspecified"))
      (node (ref "U6") (pin "9") (pinfunction "VDDA_9") (pintype "unspecified"))
    )
    (net (code "130") (name "Net-(U6-VSSA)") (class "Default")
      (node (ref "L5") (pin "2") (pinfunction "2_2") (pintype "unspecified"))
      (node (ref "U6") (pin "8") (pinfunction "VSSA_8") (pintype "unspecified"))
    )
    (net (code "131") (name "Net-(U10-BOOT0)") (class "Default")
      (node (ref "R52") (pin "1") (pinfunction "1_1") (pintype "unspecified"))
      (node (ref "U10") (pin "44") (pinfunction "BOOT0_44") (pintype "unspecified"))
    )
    (net (code "132") (name "Net-(U10-VDDA)") (class "Default")
      (node (ref "C67") (pin "2") (pinfunction "2_2") (pintype "unspecified"))
      (node (ref "L7") (pin "1") (pinfunction "1_1") (pintype "unspecified"))
      (node (ref "U10") (pin "9") (pinfunction "VDDA_9") (pintype "unspecified"))
    )
    (net (code "133") (name "Net-(U10-VSSA)") (class "Default")
      (node (ref "L8") (pin "2") (pinfunction "2_2") (pintype "unspecified"))
      (node (ref "U10") (pin "8") (pinfunction "VSSA_8") (pintype "unspecified"))
    )
    (net (code "134") (name "Net-(U11-BS)") (class "Default")
      (node (ref "C83") (pin "2") (pinfunction "2_2") (pintype "unspecified"))
      (node (ref "U11") (pin "1") (pinfunction "BS_1") (pintype "input"))
    )
    (net (code "135") (name "Net-(U11-EN)") (class "Default")
      (node (ref "R66") (pin "1") (pinfunction "1_1") (pintype "input"))
      (node (ref "U11") (pin "3") (pinfunction "EN_3") (pintype "input"))
    )
    (net (code "136") (name "Net-(U11-LX)") (class "Default")
      (node (ref "C83") (pin "1") (pinfunction "1_1") (pintype "unspecified"))
      (node (ref "L9") (pin "2") (pinfunction "2_2") (pintype "unspecified"))
      (node (ref "U11") (pin "2") (pinfunction "LX_2") (pintype "input"))
    )
    (net (code "137") (name "Net-(U11-SS)") (class "Default")
      (node (ref "C84") (pin "2") (pinfunction "2_2") (pintype "unspecified"))
      (node (ref "U11") (pin "4") (pinfunction "SS_4") (pintype "input"))
    )
    (net (code "138") (name "Net-(U11-VCC)") (class "Default")
      (node (ref "C87") (pin "2") (pinfunction "2_2") (pintype "unspecified"))
      (node (ref "U11") (pin "6") (pinfunction "VCC_6") (pintype "input"))
    )
    (net (code "139") (name "Net-(U14-BOOT0)") (class "Default")
      (node (ref "R77") (pin "1") (pinfunction "1_1") (pintype "unspecified"))
      (node (ref "U14") (pin "44") (pinfunction "BOOT0_44") (pintype "unspecified"))
    )
    (net (code "140") (name "Net-(U14-VDDA)") (class "Default")
      (node (ref "C97") (pin "2") (pinfunction "2_2") (pintype "unspecified"))
      (node (ref "L10") (pin "1") (pinfunction "1_1") (pintype "unspecified"))
      (node (ref "U14") (pin "9") (pinfunction "VDDA_9") (pintype "unspecified"))
    )
    (net (code "141") (name "Net-(U14-VSSA)") (class "Default")
      (node (ref "L11") (pin "2") (pinfunction "2_2") (pintype "unspecified"))
      (node (ref "U14") (pin "8") (pinfunction "VSSA_8") (pintype "unspecified"))
    )
    (net (code "142") (name "P1") (class "Default")
      (node (ref "CN2") (pin "1") (pinfunction "1_1") (pintype "unspecified"))
      (node (ref "R101") (pin "2") (pinfunction "2_2") (pintype "input"))
    )
    (net (code "143") (name "P2") (class "Default")
      (node (ref "CN2") (pin "2") (pinfunction "2_2") (pintype "unspecified"))
      (node (ref "R102") (pin "2") (pinfunction "2_2") (pintype "input"))
    )
    (net (code "144") (name "P3") (class "Default")
      (node (ref "CN2") (pin "3") (pinfunction "3_3") (pintype "unspecified"))
      (node (ref "R103") (pin "2") (pinfunction "2_2") (pintype "input"))
    )
    (net (code "145") (name "P4") (class "Default")
      (node (ref "CN2") (pin "4") (pinfunction "4_4") (pintype "unspecified"))
      (node (ref "R104") (pin "2") (pinfunction "2_2") (pintype "input"))
    )
    (net (code "146") (name "PGND") (class "Default")
      (node (ref "C10") (pin "1") (pinfunction "1_1") (pintype "unspecified"))
      (node (ref "C11") (pin "1") (pinfunction "1_1") (pintype "unspecified"))
      (node (ref "C12") (pin "1") (pinfunction "1_1") (pintype "unspecified"))
      (node (ref "C126") (pin "1") (pinfunction "1_1") (pintype "unspecified"))
      (node (ref "C127") (pin "1") (pinfunction "1_1") (pintype "unspecified"))
      (node (ref "C128") (pin "1") (pinfunction "1_1") (pintype "unspecified"))
      (node (ref "C129") (pin "1") (pinfunction "1_1") (pintype "unspecified"))
      (node (ref "C13") (pin "1") (pinfunction "1_1") (pintype "unspecified"))
      (node (ref "C130") (pin "1") (pinfunction "1_1") (pintype "unspecified"))
      (node (ref "C131") (pin "1") (pinfunction "1_1") (pintype "unspecified"))
      (node (ref "C132") (pin "1") (pinfunction "1_1") (pintype "unspecified"))
      (node (ref "C133") (pin "1") (pinfunction "1_1") (pintype "unspecified"))
      (node (ref "C134") (pin "1") (pinfunction "1_1") (pintype "unspecified"))
      (node (ref "C135") (pin "1") (pinfunction "1_1") (pintype "unspecified"))
      (node (ref "C136") (pin "1") (pinfunction "1_1") (pintype "unspecified"))
      (node (ref "C137") (pin "1") (pinfunction "1_1") (pintype "unspecified"))
      (node (ref "C138") (pin "1") (pinfunction "1_1") (pintype "unspecified"))
      (node (ref "C14") (pin "1") (pinfunction "1_1") (pintype "unspecified"))
      (node (ref "C15") (pin "1") (pinfunction "1_1") (pintype "unspecified"))
      (node (ref "C16") (pin "2") (pinfunction "2_2") (pintype "input"))
      (node (ref "C23") (pin "1") (pinfunction "1_1") (pintype "unspecified"))
      (node (ref "C24") (pin "1") (pinfunction "1_1") (pintype "unspecified"))
      (node (ref "C36") (pin "1") (pinfunction "1_1") (pintype "unspecified"))
      (node (ref "C66") (pin "1") (pinfunction "1_1") (pintype "unspecified"))
      (node (ref "C76") (pin "1") (pinfunction "1_1") (pintype "unspecified"))
      (node (ref "C77") (pin "1") (pinfunction "1_1") (pintype "unspecified"))
      (node (ref "C78") (pin "1") (pinfunction "1_1") (pintype "unspecified"))
      (node (ref "C79") (pin "1") (pinfunction "1_1") (pintype "unspecified"))
      (node (ref "C80") (pin "1") (pinfunction "1_1") (pintype "unspecified"))
      (node (ref "C81") (pin "1") (pinfunction "1_1") (pintype "unspecified"))
      (node (ref "C82") (pin "2") (pinfunction "2_2") (pintype "input"))
      (node (ref "C96") (pin "1") (pinfunction "1_1") (pintype "unspecified"))
      (node (ref "Q10") (pin "1") (pinfunction "S_1") (pintype "unspecified"))
      (node (ref "Q10") (pin "2") (pinfunction "S_2") (pintype "unspecified"))
      (node (ref "Q10") (pin "3") (pinfunction "S_3") (pintype "unspecified"))
      (node (ref "Q12") (pin "1") (pinfunction "S_1") (pintype "unspecified"))
      (node (ref "Q12") (pin "2") (pinfunction "S_2") (pintype "unspecified"))
      (node (ref "Q12") (pin "3") (pinfunction "S_3") (pintype "unspecified"))
      (node (ref "Q14") (pin "1") (pinfunction "S_1") (pintype "unspecified"))
      (node (ref "Q14") (pin "2") (pinfunction "S_2") (pintype "unspecified"))
      (node (ref "Q14") (pin "3") (pinfunction "S_3") (pintype "unspecified"))
      (node (ref "Q16") (pin "1") (pinfunction "S_1") (pintype "unspecified"))
      (node (ref "Q16") (pin "2") (pinfunction "S_2") (pintype "unspecified"))
      (node (ref "Q16") (pin "3") (pinfunction "S_3") (pintype "unspecified"))
      (node (ref "Q18") (pin "1") (pinfunction "S_1") (pintype "unspecified"))
      (node (ref "Q18") (pin "2") (pinfunction "S_2") (pintype "unspecified"))
      (node (ref "Q18") (pin "3") (pinfunction "S_3") (pintype "unspecified"))
      (node (ref "Q2") (pin "1") (pinfunction "S_1") (pintype "unspecified"))
      (node (ref "Q2") (pin "2") (pinfunction "S_2") (pintype "unspecified"))
      (node (ref "Q2") (pin "3") (pinfunction "S_3") (pintype "unspecified"))
      (node (ref "Q20") (pin "1") (pinfunction "S_1") (pintype "unspecified"))
      (node (ref "Q20") (pin "2") (pinfunction "S_2") (pintype "unspecified"))
      (node (ref "Q20") (pin "3") (pinfunction "S_3") (pintype "unspecified"))
      (node (ref "Q22") (pin "1") (pinfunction "S_1") (pintype "unspecified"))
      (node (ref "Q22") (pin "2") (pinfunction "S_2") (pintype "unspecified"))
      (node (ref "Q22") (pin "3") (pinfunction "S_3") (pintype "unspecified"))
      (node (ref "Q24") (pin "1") (pinfunction "S_1") (pintype "unspecified"))
      (node (ref "Q24") (pin "2") (pinfunction "S_2") (pintype "unspecified"))
      (node (ref "Q24") (pin "3") (pinfunction "S_3") (pintype "unspecified"))
      (node (ref "Q4") (pin "1") (pinfunction "S_1") (pintype "unspecified"))
      (node (ref "Q4") (pin "2") (pinfunction "S_2") (pintype "unspecified"))
      (node (ref "Q4") (pin "3") (pinfunction "S_3") (pintype "unspecified"))
      (node (ref "Q6") (pin "1") (pinfunction "S_1") (pintype "unspecified"))
      (node (ref "Q6") (pin "2") (pinfunction "S_2") (pintype "unspecified"))
      (node (ref "Q6") (pin "3") (pinfunction "S_3") (pintype "unspecified"))
      (node (ref "Q8") (pin "1") (pinfunction "S_1") (pintype "unspecified"))
      (node (ref "Q8") (pin "2") (pinfunction "S_2") (pintype "unspecified"))
      (node (ref "Q8") (pin "3") (pinfunction "S_3") (pintype "unspecified"))
      (node (ref "R105") (pin "2") (pinfunction "2_2") (pintype "input"))
      (node (ref "R106") (pin "2") (pinfunction "2_2") (pintype "input"))
      (node (ref "R107") (pin "2") (pinfunction "2_2") (pintype "input"))
      (node (ref "R17") (pin "2") (pinfunction "2_2") (pintype "input"))
      (node (ref "R67") (pin "2") (pinfunction "2_2") (pintype "input"))
      (node (ref "U11") (pin "9") (pinfunction "GND_9") (pintype "input"))
      (node (ref "U13") (pin "25") (pinfunction "EP_25") (pintype "unspecified"))
      (node (ref "U13") (pin "6") (pinfunction "COM_6") (pintype "unspecified"))
      (node (ref "U17") (pin "25") (pinfunction "EP_25") (pintype "unspecified"))
      (node (ref "U17") (pin "6") (pinfunction "COM_6") (pintype "unspecified"))
      (node (ref "U3") (pin "9") (pinfunction "GND_9") (pintype "input"))
      (node (ref "U5") (pin "25") (pinfunction "EP_25") (pintype "unspecified"))
      (node (ref "U5") (pin "6") (pinfunction "COM_6") (pintype "unspecified"))
      (node (ref "U9") (pin "25") (pinfunction "EP_25") (pintype "unspecified"))
      (node (ref "U9") (pin "6") (pinfunction "COM_6") (pintype "unspecified"))
    )
    (net (code "147") (name "PWMAH1") (class "Default")
      (node (ref "U1") (pin "29") (pinfunction "PA8_29") (pintype "unspecified"))
      (node (ref "U5") (pin "22") (pinfunction "HIN1_22") (pintype "unspecified"))
    )
    (net (code "148") (name "PWMAH2") (class "Default")
      (node (ref "U6") (pin "29") (pinfunction "PA8_29") (pintype "unspecified"))
      (node (ref "U9") (pin "22") (pinfunction "HIN1_22") (pintype "unspecified"))
    )
    (net (code "149") (name "PWMAH3") (class "Default")
      (node (ref "U10") (pin "29") (pinfunction "PA8_29") (pintype "unspecified"))
      (node (ref "U13") (pin "22") (pinfunction "HIN1_22") (pintype "unspecified"))
    )
    (net (code "150") (name "PWMAH4") (class "Default")
      (node (ref "U14") (pin "29") (pinfunction "PA8_29") (pintype "unspecified"))
      (node (ref "U17") (pin "22") (pinfunction "HIN1_22") (pintype "unspecified"))
    )
    (net (code "151") (name "PWMAL1") (class "Default")
      (node (ref "U1") (pin "17") (pinfunction "PA7/ADC7_17") (pintype "unspecified"))
      (node (ref "U5") (pin "1") (pinfunction "LIN1_1") (pintype "unspecified"))
    )
    (net (code "152") (name "PWMAL2") (class "Default")
      (node (ref "U6") (pin "17") (pinfunction "PA7/ADC7_17") (pintype "unspecified"))
      (node (ref "U9") (pin "1") (pinfunction "LIN1_1") (pintype "unspecified"))
    )
    (net (code "153") (name "PWMAL3") (class "Default")
      (node (ref "U10") (pin "17") (pinfunction "PA7/ADC7_17") (pintype "unspecified"))
      (node (ref "U13") (pin "1") (pinfunction "LIN1_1") (pintype "unspecified"))
    )
    (net (code "154") (name "PWMAL4") (class "Default")
      (node (ref "U14") (pin "17") (pinfunction "PA7/ADC7_17") (pintype "unspecified"))
      (node (ref "U17") (pin "1") (pinfunction "LIN1_1") (pintype "unspecified"))
    )
    (net (code "155") (name "PWMBH1") (class "Default")
      (node (ref "U1") (pin "30") (pinfunction "PA9_30") (pintype "unspecified"))
      (node (ref "U5") (pin "23") (pinfunction "HIN2_23") (pintype "unspecified"))
    )
    (net (code "156") (name "PWMBH2") (class "Default")
      (node (ref "U6") (pin "30") (pinfunction "PA9_30") (pintype "unspecified"))
      (node (ref "U9") (pin "23") (pinfunction "HIN2_23") (pintype "unspecified"))
    )
    (net (code "157") (name "PWMBH3") (class "Default")
      (node (ref "U10") (pin "30") (pinfunction "PA9_30") (pintype "unspecified"))
      (node (ref "U13") (pin "23") (pinfunction "HIN2_23") (pintype "unspecified"))
    )
    (net (code "158") (name "PWMBH4") (class "Default")
      (node (ref "U14") (pin "30") (pinfunction "PA9_30") (pintype "unspecified"))
      (node (ref "U17") (pin "23") (pinfunction "HIN2_23") (pintype "unspecified"))
    )
    (net (code "159") (name "PWMBL1") (class "Default")
      (node (ref "U1") (pin "18") (pinfunction "PB0/ADC8_18") (pintype "unspecified"))
      (node (ref "U5") (pin "2") (pinfunction "LIN2_2") (pintype "unspecified"))
    )
    (net (code "160") (name "PWMBL2") (class "Default")
      (node (ref "U6") (pin "18") (pinfunction "PB0/ADC8_18") (pintype "unspecified"))
      (node (ref "U9") (pin "2") (pinfunction "LIN2_2") (pintype "unspecified"))
    )
    (net (code "161") (name "PWMBL3") (class "Default")
      (node (ref "U10") (pin "18") (pinfunction "PB0/ADC8_18") (pintype "unspecified"))
      (node (ref "U13") (pin "2") (pinfunction "LIN2_2") (pintype "unspecified"))
    )
    (net (code "162") (name "PWMBL4") (class "Default")
      (node (ref "U14") (pin "18") (pinfunction "PB0/ADC8_18") (pintype "unspecified"))
      (node (ref "U17") (pin "2") (pinfunction "LIN2_2") (pintype "unspecified"))
    )
    (net (code "163") (name "PWMCH1") (class "Default")
      (node (ref "U1") (pin "31") (pinfunction "PA10_31") (pintype "unspecified"))
      (node (ref "U5") (pin "24") (pinfunction "HIN3_24") (pintype "unspecified"))
    )
    (net (code "164") (name "PWMCH2") (class "Default")
      (node (ref "U6") (pin "31") (pinfunction "PA10_31") (pintype "unspecified"))
      (node (ref "U9") (pin "24") (pinfunction "HIN3_24") (pintype "unspecified"))
    )
    (net (code "165") (name "PWMCH3") (class "Default")
      (node (ref "U10") (pin "31") (pinfunction "PA10_31") (pintype "unspecified"))
      (node (ref "U13") (pin "24") (pinfunction "HIN3_24") (pintype "unspecified"))
    )
    (net (code "166") (name "PWMCH4") (class "Default")
      (node (ref "U14") (pin "31") (pinfunction "PA10_31") (pintype "unspecified"))
      (node (ref "U17") (pin "24") (pinfunction "HIN3_24") (pintype "unspecified"))
    )
    (net (code "167") (name "PWMCL1") (class "Default")
      (node (ref "U1") (pin "19") (pinfunction "PB1/ADC9_19") (pintype "unspecified"))
      (node (ref "U5") (pin "3") (pinfunction "LIN3_3") (pintype "unspecified"))
    )
    (net (code "168") (name "PWMCL2") (class "Default")
      (node (ref "U6") (pin "19") (pinfunction "PB1/ADC9_19") (pintype "unspecified"))
      (node (ref "U9") (pin "3") (pinfunction "LIN3_3") (pintype "unspecified"))
    )
    (net (code "169") (name "PWMCL3") (class "Default")
      (node (ref "U10") (pin "19") (pinfunction "PB1/ADC9_19") (pintype "unspecified"))
      (node (ref "U13") (pin "3") (pinfunction "LIN3_3") (pintype "unspecified"))
    )
    (net (code "170") (name "PWMCL4") (class "Default")
      (node (ref "U14") (pin "19") (pinfunction "PB1/ADC9_19") (pintype "unspecified"))
      (node (ref "U17") (pin "3") (pinfunction "LIN3_3") (pintype "unspecified"))
    )
    (net (code "171") (name "PWMIN1") (class "Default")
      (node (ref "R101") (pin "1") (pinfunction "1_1") (pintype "input"))
      (node (ref "U1") (pin "38") (pinfunction "PA15_38") (pintype "unspecified"))
    )
    (net (code "172") (name "PWMIN2") (class "Default")
      (node (ref "R102") (pin "1") (pinfunction "1_1") (pintype "input"))
      (node (ref "U6") (pin "38") (pinfunction "PA15_38") (pintype "unspecified"))
    )
    (net (code "173") (name "PWMIN3") (class "Default")
      (node (ref "R103") (pin "1") (pinfunction "1_1") (pintype "input"))
      (node (ref "U10") (pin "38") (pinfunction "PA15_38") (pintype "unspecified"))
    )
    (net (code "174") (name "PWMIN4") (class "Default")
      (node (ref "R104") (pin "1") (pinfunction "1_1") (pintype "input"))
      (node (ref "U14") (pin "38") (pinfunction "PA15_38") (pintype "unspecified"))
    )
    (net (code "175") (name "RUN1") (class "Default")
      (node (ref "LED2") (pin "1") (pinfunction "K_1") (pintype "unspecified"))
      (node (ref "U1") (pin "46") (pinfunction "PB9_46") (pintype "unspecified"))
    )
    (net (code "176") (name "RUN2") (class "Default")
      (node (ref "LED4") (pin "1") (pinfunction "K_1") (pintype "unspecified"))
      (node (ref "U6") (pin "46") (pinfunction "PB9_46") (pintype "unspecified"))
    )
    (net (code "177") (name "RUN3") (class "Default")
      (node (ref "LED6") (pin "1") (pinfunction "K_1") (pintype "unspecified"))
      (node (ref "U10") (pin "46") (pinfunction "PB9_46") (pintype "unspecified"))
    )
    (net (code "178") (name "RUN4") (class "Default")
      (node (ref "LED8") (pin "1") (pinfunction "K_1") (pintype "unspecified"))
      (node (ref "U14") (pin "46") (pinfunction "PB9_46") (pintype "unspecified"))
    )
    (net (code "179") (name "RX1") (class "Default")
      (node (ref "H1") (pin "1") (pinfunction "1_1") (pintype "unspecified"))
      (node (ref "U1") (pin "43") (pinfunction "PB7_43") (pintype "unspecified"))
    )
    (net (code "180") (name "RX2") (class "Default")
      (node (ref "H2") (pin "1") (pinfunction "1_1") (pintype "unspecified"))
      (node (ref "U6") (pin "43") (pinfunction "PB7_43") (pintype "unspecified"))
    )
    (net (code "181") (name "RX3") (class "Default")
      (node (ref "H3") (pin "1") (pinfunction "1_1") (pintype "unspecified"))
      (node (ref "U10") (pin "43") (pinfunction "PB7_43") (pintype "unspecified"))
    )
    (net (code "182") (name "RX4") (class "Default")
      (node (ref "H4") (pin "1") (pinfunction "1_1") (pintype "unspecified"))
      (node (ref "U14") (pin "43") (pinfunction "PB7_43") (pintype "unspecified"))
    )
    (net (code "183") (name "TX1") (class "Default")
      (node (ref "H1") (pin "2") (pinfunction "2_2") (pintype "unspecified"))
      (node (ref "U1") (pin "42") (pinfunction "PB6_42") (pintype "unspecified"))
    )
    (net (code "184") (name "TX2") (class "Default")
      (node (ref "H2") (pin "2") (pinfunction "2_2") (pintype "unspecified"))
      (node (ref "U6") (pin "42") (pinfunction "PB6_42") (pintype "unspecified"))
    )
    (net (code "185") (name "TX3") (class "Default")
      (node (ref "H3") (pin "2") (pinfunction "2_2") (pintype "unspecified"))
      (node (ref "U10") (pin "42") (pinfunction "PB6_42") (pintype "unspecified"))
    )
    (net (code "186") (name "TX4") (class "Default")
      (node (ref "H4") (pin "2") (pinfunction "2_2") (pintype "unspecified"))
      (node (ref "U14") (pin "42") (pinfunction "PB6_42") (pintype "unspecified"))
    )
    (net (code "187") (name "VCCBAT") (class "Default")
      (node (ref "C10") (pin "2") (pinfunction "2_2") (pintype "unspecified"))
      (node (ref "C11") (pin "2") (pinfunction "2_2") (pintype "unspecified"))
      (node (ref "C12") (pin "2") (pinfunction "2_2") (pintype "unspecified"))
      (node (ref "C127") (pin "2") (pinfunction "2_2") (pintype "unspecified"))
      (node (ref "C128") (pin "2") (pinfunction "2_2") (pintype "unspecified"))
      (node (ref "C129") (pin "2") (pinfunction "2_2") (pintype "unspecified"))
      (node (ref "C13") (pin "2") (pinfunction "2_2") (pintype "unspecified"))
      (node (ref "C130") (pin "2") (pinfunction "2_2") (pintype "unspecified"))
      (node (ref "C131") (pin "2") (pinfunction "2_2") (pintype "unspecified"))
      (node (ref "C132") (pin "2") (pinfunction "2_2") (pintype "unspecified"))
      (node (ref "C133") (pin "2") (pinfunction "2_2") (pintype "unspecified"))
      (node (ref "C134") (pin "2") (pinfunction "2_2") (pintype "unspecified"))
      (node (ref "C135") (pin "2") (pinfunction "2_2") (pintype "unspecified"))
      (node (ref "C136") (pin "2") (pinfunction "2_2") (pintype "unspecified"))
      (node (ref "C137") (pin "2") (pinfunction "2_2") (pintype "unspecified"))
      (node (ref "C138") (pin "2") (pinfunction "2_2") (pintype "unspecified"))
      (node (ref "C14") (pin "2") (pinfunction "2_2") (pintype "unspecified"))
      (node (ref "C15") (pin "2") (pinfunction "2_2") (pintype "unspecified"))
      (node (ref "C16") (pin "1") (pinfunction "1_1") (pintype "input"))
      (node (ref "C76") (pin "2") (pinfunction "2_2") (pintype "unspecified"))
      (node (ref "C77") (pin "2") (pinfunction "2_2") (pintype "unspecified"))
      (node (ref "C78") (pin "2") (pinfunction "2_2") (pintype "unspecified"))
      (node (ref "C79") (pin "2") (pinfunction "2_2") (pintype "unspecified"))
      (node (ref "C80") (pin "2") (pinfunction "2_2") (pintype "unspecified"))
      (node (ref "C81") (pin "2") (pinfunction "2_2") (pintype "unspecified"))
      (node (ref "C82") (pin "1") (pinfunction "1_1") (pintype "input"))
      (node (ref "F2") (pin "1") (pinfunction "1_1") (pintype "unspecified"))
      (node (ref "F4") (pin "1") (pinfunction "1_1") (pintype "unspecified"))
      (node (ref "Q1") (pin "5") (pinfunction "D_5") (pintype "unspecified"))
      (node (ref "Q1") (pin "6") (pinfunction "D_6") (pintype "unspecified"))
      (node (ref "Q1") (pin "7") (pinfunction "D_7") (pintype "unspecified"))
      (node (ref "Q1") (pin "8") (pinfunction "D_8") (pintype "unspecified"))
      (node (ref "Q1") (pin "9") (pinfunction "D_9") (pintype "unspecified"))
      (node (ref "Q11") (pin "5") (pinfunction "D_5") (pintype "unspecified"))
      (node (ref "Q11") (pin "6") (pinfunction "D_6") (pintype "unspecified"))
      (node (ref "Q11") (pin "7") (pinfunction "D_7") (pintype "unspecified"))
      (node (ref "Q11") (pin "8") (pinfunction "D_8") (pintype "unspecified"))
      (node (ref "Q11") (pin "9") (pinfunction "D_9") (pintype "unspecified"))
      (node (ref "Q13") (pin "5") (pinfunction "D_5") (pintype "unspecified"))
      (node (ref "Q13") (pin "6") (pinfunction "D_6") (pintype "unspecified"))
      (node (ref "Q13") (pin "7") (pinfunction "D_7") (pintype "unspecified"))
      (node (ref "Q13") (pin "8") (pinfunction "D_8") (pintype "unspecified"))
      (node (ref "Q13") (pin "9") (pinfunction "D_9") (pintype "unspecified"))
      (node (ref "Q15") (pin "5") (pinfunction "D_5") (pintype "unspecified"))
      (node (ref "Q15") (pin "6") (pinfunction "D_6") (pintype "unspecified"))
      (node (ref "Q15") (pin "7") (pinfunction "D_7") (pintype "unspecified"))
      (node (ref "Q15") (pin "8") (pinfunction "D_8") (pintype "unspecified"))
      (node (ref "Q15") (pin "9") (pinfunction "D_9") (pintype "unspecified"))
      (node (ref "Q17") (pin "5") (pinfunction "D_5") (pintype "unspecified"))
      (node (ref "Q17") (pin "6") (pinfunction "D_6") (pintype "unspecified"))
      (node (ref "Q17") (pin "7") (pinfunction "D_7") (pintype "unspecified"))
      (node (ref "Q17") (pin "8") (pinfunction "D_8") (pintype "unspecified"))
      (node (ref "Q17") (pin "9") (pinfunction "D_9") (pintype "unspecified"))
      (node (ref "Q19") (pin "5") (pinfunction "D_5") (pintype "unspecified"))
      (node (ref "Q19") (pin "6") (pinfunction "D_6") (pintype "unspecified"))
      (node (ref "Q19") (pin "7") (pinfunction "D_7") (pintype "unspecified"))
      (node (ref "Q19") (pin "8") (pinfunction "D_8") (pintype "unspecified"))
      (node (ref "Q19") (pin "9") (pinfunction "D_9") (pintype "unspecified"))
      (node (ref "Q21") (pin "5") (pinfunction "D_5") (pintype "unspecified"))
      (node (ref "Q21") (pin "6") (pinfunction "D_6") (pintype "unspecified"))
      (node (ref "Q21") (pin "7") (pinfunction "D_7") (pintype "unspecified"))
      (node (ref "Q21") (pin "8") (pinfunction "D_8") (pintype "unspecified"))
      (node (ref "Q21") (pin "9") (pinfunction "D_9") (pintype "unspecified"))
      (node (ref "Q23") (pin "5") (pinfunction "D_5") (pintype "unspecified"))
      (node (ref "Q23") (pin "6") (pinfunction "D_6") (pintype "unspecified"))
      (node (ref "Q23") (pin "7") (pinfunction "D_7") (pintype "unspecified"))
      (node (ref "Q23") (pin "8") (pinfunction "D_8") (pintype "unspecified"))
      (node (ref "Q23") (pin "9") (pinfunction "D_9") (pintype "unspecified"))
      (node (ref "Q3") (pin "5") (pinfunction "D_5") (pintype "unspecified"))
      (node (ref "Q3") (pin "6") (pinfunction "D_6") (pintype "unspecified"))
      (node (ref "Q3") (pin "7") (pinfunction "D_7") (pintype "unspecified"))
      (node (ref "Q3") (pin "8") (pinfunction "D_8") (pintype "unspecified"))
      (node (ref "Q3") (pin "9") (pinfunction "D_9") (pintype "unspecified"))
      (node (ref "Q5") (pin "5") (pinfunction "D_5") (pintype "unspecified"))
      (node (ref "Q5") (pin "6") (pinfunction "D_6") (pintype "unspecified"))
      (node (ref "Q5") (pin "7") (pinfunction "D_7") (pintype "unspecified"))
      (node (ref "Q5") (pin "8") (pinfunction "D_8") (pintype "unspecified"))
      (node (ref "Q5") (pin "9") (pinfunction "D_9") (pintype "unspecified"))
      (node (ref "Q7") (pin "5") (pinfunction "D_5") (pintype "unspecified"))
      (node (ref "Q7") (pin "6") (pinfunction "D_6") (pintype "unspecified"))
      (node (ref "Q7") (pin "7") (pinfunction "D_7") (pintype "unspecified"))
      (node (ref "Q7") (pin "8") (pinfunction "D_8") (pintype "unspecified"))
      (node (ref "Q7") (pin "9") (pinfunction "D_9") (pintype "unspecified"))
      (node (ref "Q9") (pin "5") (pinfunction "D_5") (pintype "unspecified"))
      (node (ref "Q9") (pin "6") (pinfunction "D_6") (pintype "unspecified"))
      (node (ref "Q9") (pin "7") (pinfunction "D_7") (pintype "unspecified"))
      (node (ref "Q9") (pin "8") (pinfunction "D_8") (pintype "unspecified"))
      (node (ref "Q9") (pin "9") (pinfunction "D_9") (pintype "unspecified"))
      (node (ref "R12") (pin "1") (pinfunction "1_1") (pintype "input"))
      (node (ref "R37") (pin "1") (pinfunction "1_1") (pintype "input"))
      (node (ref "R62") (pin "1") (pinfunction "1_1") (pintype "input"))
      (node (ref "R87") (pin "1") (pinfunction "1_1") (pintype "input"))
    )
    (net (code "188") (name "VSA1") (class "Default")
      (node (ref "C33") (pin "1") (pinfunction "1_1") (pintype "input"))
      (node (ref "Q1") (pin "1") (pinfunction "S_1") (pintype "unspecified"))
      (node (ref "Q1") (pin "2") (pinfunction "S_2") (pintype "unspecified"))
      (node (ref "Q1") (pin "3") (pinfunction "S_3") (pintype "unspecified"))
      (node (ref "Q2") (pin "5") (pinfunction "D_5") (pintype "unspecified"))
      (node (ref "Q2") (pin "6") (pinfunction "D_6") (pintype "unspecified"))
      (node (ref "Q2") (pin "7") (pinfunction "D_7") (pintype "unspecified"))
      (node (ref "Q2") (pin "8") (pinfunction "D_8") (pintype "unspecified"))
      (node (ref "Q2") (pin "9") (pinfunction "D_9") (pintype "unspecified"))
      (node (ref "R3") (pin "2") (pinfunction "2_2") (pintype "unspecified"))
      (node (ref "U5") (pin "18") (pinfunction "VS1_18") (pintype "unspecified"))
    )
    (net (code "189") (name "VSA2") (class "Default")
      (node (ref "C63") (pin "1") (pinfunction "1_1") (pintype "input"))
      (node (ref "Q7") (pin "1") (pinfunction "S_1") (pintype "unspecified"))
      (node (ref "Q7") (pin "2") (pinfunction "S_2") (pintype "unspecified"))
      (node (ref "Q7") (pin "3") (pinfunction "S_3") (pintype "unspecified"))
      (node (ref "Q8") (pin "5") (pinfunction "D_5") (pintype "unspecified"))
      (node (ref "Q8") (pin "6") (pinfunction "D_6") (pintype "unspecified"))
      (node (ref "Q8") (pin "7") (pinfunction "D_7") (pintype "unspecified"))
      (node (ref "Q8") (pin "8") (pinfunction "D_8") (pintype "unspecified"))
      (node (ref "Q8") (pin "9") (pinfunction "D_9") (pintype "unspecified"))
      (node (ref "R28") (pin "2") (pinfunction "2_2") (pintype "unspecified"))
      (node (ref "U9") (pin "18") (pinfunction "VS1_18") (pintype "unspecified"))
    )
    (net (code "190") (name "VSA3") (class "Default")
      (node (ref "C93") (pin "1") (pinfunction "1_1") (pintype "input"))
      (node (ref "Q13") (pin "1") (pinfunction "S_1") (pintype "unspecified"))
      (node (ref "Q13") (pin "2") (pinfunction "S_2") (pintype "unspecified"))
      (node (ref "Q13") (pin "3") (pinfunction "S_3") (pintype "unspecified"))
      (node (ref "Q14") (pin "5") (pinfunction "D_5") (pintype "unspecified"))
      (node (ref "Q14") (pin "6") (pinfunction "D_6") (pintype "unspecified"))
      (node (ref "Q14") (pin "7") (pinfunction "D_7") (pintype "unspecified"))
      (node (ref "Q14") (pin "8") (pinfunction "D_8") (pintype "unspecified"))
      (node (ref "Q14") (pin "9") (pinfunction "D_9") (pintype "unspecified"))
      (node (ref "R53") (pin "2") (pinfunction "2_2") (pintype "unspecified"))
      (node (ref "U13") (pin "18") (pinfunction "VS1_18") (pintype "unspecified"))
    )
    (net (code "191") (name "VSA4") (class "Default")
      (node (ref "C123") (pin "1") (pinfunction "1_1") (pintype "input"))
      (node (ref "Q19") (pin "1") (pinfunction "S_1") (pintype "unspecified"))
      (node (ref "Q19") (pin "2") (pinfunction "S_2") (pintype "unspecified"))
      (node (ref "Q19") (pin "3") (pinfunction "S_3") (pintype "unspecified"))
      (node (ref "Q20") (pin "5") (pinfunction "D_5") (pintype "unspecified"))
      (node (ref "Q20") (pin "6") (pinfunction "D_6") (pintype "unspecified"))
      (node (ref "Q20") (pin "7") (pinfunction "D_7") (pintype "unspecified"))
      (node (ref "Q20") (pin "8") (pinfunction "D_8") (pintype "unspecified"))
      (node (ref "Q20") (pin "9") (pinfunction "D_9") (pintype "unspecified"))
      (node (ref "R78") (pin "2") (pinfunction "2_2") (pintype "unspecified"))
      (node (ref "U17") (pin "18") (pinfunction "VS1_18") (pintype "unspecified"))
    )
    (net (code "192") (name "VSB1") (class "Default")
      (node (ref "C34") (pin "1") (pinfunction "1_1") (pintype "input"))
      (node (ref "Q3") (pin "1") (pinfunction "S_1") (pintype "unspecified"))
      (node (ref "Q3") (pin "2") (pinfunction "S_2") (pintype "unspecified"))
      (node (ref "Q3") (pin "3") (pinfunction "S_3") (pintype "unspecified"))
      (node (ref "Q4") (pin "5") (pinfunction "D_5") (pintype "unspecified"))
      (node (ref "Q4") (pin "6") (pinfunction "D_6") (pintype "unspecified"))
      (node (ref "Q4") (pin "7") (pinfunction "D_7") (pintype "unspecified"))
      (node (ref "Q4") (pin "8") (pinfunction "D_8") (pintype "unspecified"))
      (node (ref "Q4") (pin "9") (pinfunction "D_9") (pintype "unspecified"))
      (node (ref "R6") (pin "2") (pinfunction "2_2") (pintype "unspecified"))
      (node (ref "U5") (pin "15") (pinfunction "VS2_15") (pintype "unspecified"))
    )
    (net (code "193") (name "VSB2") (class "Default")
      (node (ref "C64") (pin "1") (pinfunction "1_1") (pintype "input"))
      (node (ref "Q10") (pin "5") (pinfunction "D_5") (pintype "unspecified"))
      (node (ref "Q10") (pin "6") (pinfunction "D_6") (pintype "unspecified"))
      (node (ref "Q10") (pin "7") (pinfunction "D_7") (pintype "unspecified"))
      (node (ref "Q10") (pin "8") (pinfunction "D_8") (pintype "unspecified"))
      (node (ref "Q10") (pin "9") (pinfunction "D_9") (pintype "unspecified"))
      (node (ref "Q9") (pin "1") (pinfunction "S_1") (pintype "unspecified"))
      (node (ref "Q9") (pin "2") (pinfunction "S_2") (pintype "unspecified"))
      (node (ref "Q9") (pin "3") (pinfunction "S_3") (pintype "unspecified"))
      (node (ref "R31") (pin "2") (pinfunction "2_2") (pintype "unspecified"))
      (node (ref "U9") (pin "15") (pinfunction "VS2_15") (pintype "unspecified"))
    )
    (net (code "194") (name "VSB3") (class "Default")
      (node (ref "C94") (pin "1") (pinfunction "1_1") (pintype "input"))
      (node (ref "Q15") (pin "1") (pinfunction "S_1") (pintype "unspecified"))
      (node (ref "Q15") (pin "2") (pinfunction "S_2") (pintype "unspecified"))
      (node (ref "Q15") (pin "3") (pinfunction "S_3") (pintype "unspecified"))
      (node (ref "Q16") (pin "5") (pinfunction "D_5") (pintype "unspecified"))
      (node (ref "Q16") (pin "6") (pinfunction "D_6") (pintype "unspecified"))
      (node (ref "Q16") (pin "7") (pinfunction "D_7") (pintype "unspecified"))
      (node (ref "Q16") (pin "8") (pinfunction "D_8") (pintype "unspecified"))
      (node (ref "Q16") (pin "9") (pinfunction "D_9") (pintype "unspecified"))
      (node (ref "R56") (pin "2") (pinfunction "2_2") (pintype "unspecified"))
      (node (ref "U13") (pin "15") (pinfunction "VS2_15") (pintype "unspecified"))
    )
    (net (code "195") (name "VSB4") (class "Default")
      (node (ref "C124") (pin "1") (pinfunction "1_1") (pintype "input"))
      (node (ref "Q21") (pin "1") (pinfunction "S_1") (pintype "unspecified"))
      (node (ref "Q21") (pin "2") (pinfunction "S_2") (pintype "unspecified"))
      (node (ref "Q21") (pin "3") (pinfunction "S_3") (pintype "unspecified"))
      (node (ref "Q22") (pin "5") (pinfunction "D_5") (pintype "unspecified"))
      (node (ref "Q22") (pin "6") (pinfunction "D_6") (pintype "unspecified"))
      (node (ref "Q22") (pin "7") (pinfunction "D_7") (pintype "unspecified"))
      (node (ref "Q22") (pin "8") (pinfunction "D_8") (pintype "unspecified"))
      (node (ref "Q22") (pin "9") (pinfunction "D_9") (pintype "unspecified"))
      (node (ref "R81") (pin "2") (pinfunction "2_2") (pintype "unspecified"))
      (node (ref "U17") (pin "15") (pinfunction "VS2_15") (pintype "unspecified"))
    )
    (net (code "196") (name "VSC1") (class "Default")
      (node (ref "C35") (pin "1") (pinfunction "1_1") (pintype "input"))
      (node (ref "Q5") (pin "1") (pinfunction "S_1") (pintype "unspecified"))
      (node (ref "Q5") (pin "2") (pinfunction "S_2") (pintype "unspecified"))
      (node (ref "Q5") (pin "3") (pinfunction "S_3") (pintype "unspecified"))
      (node (ref "Q6") (pin "5") (pinfunction "D_5") (pintype "unspecified"))
      (node (ref "Q6") (pin "6") (pinfunction "D_6") (pintype "unspecified"))
      (node (ref "Q6") (pin "7") (pinfunction "D_7") (pintype "unspecified"))
      (node (ref "Q6") (pin "8") (pinfunction "D_8") (pintype "unspecified"))
      (node (ref "Q6") (pin "9") (pinfunction "D_9") (pintype "unspecified"))
      (node (ref "R9") (pin "2") (pinfunction "2_2") (pintype "unspecified"))
      (node (ref "U5") (pin "12") (pinfunction "VS3_12") (pintype "unspecified"))
    )
    (net (code "197") (name "VSC2") (class "Default")
      (node (ref "C65") (pin "1") (pinfunction "1_1") (pintype "input"))
      (node (ref "Q11") (pin "1") (pinfunction "S_1") (pintype "unspecified"))
      (node (ref "Q11") (pin "2") (pinfunction "S_2") (pintype "unspecified"))
      (node (ref "Q11") (pin "3") (pinfunction "S_3") (pintype "unspecified"))
      (node (ref "Q12") (pin "5") (pinfunction "D_5") (pintype "unspecified"))
      (node (ref "Q12") (pin "6") (pinfunction "D_6") (pintype "unspecified"))
      (node (ref "Q12") (pin "7") (pinfunction "D_7") (pintype "unspecified"))
      (node (ref "Q12") (pin "8") (pinfunction "D_8") (pintype "unspecified"))
      (node (ref "Q12") (pin "9") (pinfunction "D_9") (pintype "unspecified"))
      (node (ref "R34") (pin "2") (pinfunction "2_2") (pintype "unspecified"))
      (node (ref "U9") (pin "12") (pinfunction "VS3_12") (pintype "unspecified"))
    )
    (net (code "198") (name "VSC3") (class "Default")
      (node (ref "C95") (pin "1") (pinfunction "1_1") (pintype "input"))
      (node (ref "Q17") (pin "1") (pinfunction "S_1") (pintype "unspecified"))
      (node (ref "Q17") (pin "2") (pinfunction "S_2") (pintype "unspecified"))
      (node (ref "Q17") (pin "3") (pinfunction "S_3") (pintype "unspecified"))
      (node (ref "Q18") (pin "5") (pinfunction "D_5") (pintype "unspecified"))
      (node (ref "Q18") (pin "6") (pinfunction "D_6") (pintype "unspecified"))
      (node (ref "Q18") (pin "7") (pinfunction "D_7") (pintype "unspecified"))
      (node (ref "Q18") (pin "8") (pinfunction "D_8") (pintype "unspecified"))
      (node (ref "Q18") (pin "9") (pinfunction "D_9") (pintype "unspecified"))
      (node (ref "R59") (pin "2") (pinfunction "2_2") (pintype "unspecified"))
      (node (ref "U13") (pin "12") (pinfunction "VS3_12") (pintype "unspecified"))
    )
    (net (code "199") (name "VSC4") (class "Default")
      (node (ref "C125") (pin "1") (pinfunction "1_1") (pintype "input"))
      (node (ref "Q23") (pin "1") (pinfunction "S_1") (pintype "unspecified"))
      (node (ref "Q23") (pin "2") (pinfunction "S_2") (pintype "unspecified"))
      (node (ref "Q23") (pin "3") (pinfunction "S_3") (pintype "unspecified"))
      (node (ref "Q24") (pin "5") (pinfunction "D_5") (pintype "unspecified"))
      (node (ref "Q24") (pin "6") (pinfunction "D_6") (pintype "unspecified"))
      (node (ref "Q24") (pin "7") (pinfunction "D_7") (pintype "unspecified"))
      (node (ref "Q24") (pin "8") (pinfunction "D_8") (pintype "unspecified"))
      (node (ref "Q24") (pin "9") (pinfunction "D_9") (pintype "unspecified"))
      (node (ref "R84") (pin "2") (pinfunction "2_2") (pintype "unspecified"))
      (node (ref "U17") (pin "12") (pinfunction "VS3_12") (pintype "unspecified"))
    )
    (net (code "200") (name "unconnected-(D1-K-Pad2)") (class "Default")
      (node (ref "D1") (pin "2") (pinfunction "K_2") (pintype "unspecified"))
    )
    (net (code "201") (name "unconnected-(D5-K-Pad2)") (class "Default")
      (node (ref "D5") (pin "2") (pinfunction "K_2") (pintype "unspecified"))
    )
    (net (code "202") (name "unconnected-(D9-K-Pad2)") (class "Default")
      (node (ref "D9") (pin "2") (pinfunction "K_2") (pintype "unspecified"))
    )
    (net (code "203") (name "unconnected-(D13-K-Pad2)") (class "Default")
      (node (ref "D13") (pin "2") (pinfunction "K_2") (pintype "unspecified"))
    )
    (net (code "204") (name "unconnected-(TP1-Pad1)") (class "Default")
      (node (ref "TP1") (pin "1") (pinfunction "1_1") (pintype "input+no_connect"))
    )
    (net (code "205") (name "unconnected-(TP2-Pad1)") (class "Default")
      (node (ref "TP2") (pin "1") (pinfunction "1_1") (pintype "input+no_connect"))
    )
    (net (code "206") (name "unconnected-(U1-OSC_IN{slash}PD0-Pad5)") (class "Default")
      (node (ref "U1") (pin "5") (pinfunction "OSC_IN/PD0_5") (pintype "unspecified+no_connect"))
    )
    (net (code "207") (name "unconnected-(U1-OSC_OUT{slash}PD1-Pad6)") (class "Default")
      (node (ref "U1") (pin "6") (pinfunction "OSC_OUT/PD1_6") (pintype "unspecified+no_connect"))
    )
    (net (code "208") (name "unconnected-(U1-PA0{slash}WKUP{slash}ADC0-Pad10)") (class "Default")
      (node (ref "U1") (pin "10") (pinfunction "PA0/WKUP/ADC0_10") (pintype "unspecified+no_connect"))
    )
    (net (code "209") (name "unconnected-(U1-PA6{slash}ADC6-Pad16)") (class "Default")
      (node (ref "U1") (pin "16") (pinfunction "PA6/ADC6_16") (pintype "unspecified+no_connect"))
    )
    (net (code "210") (name "unconnected-(U1-PA11{slash}USB1DM-Pad32)") (class "Default")
      (node (ref "U1") (pin "32") (pinfunction "PA11/USB1DM_32") (pintype "unspecified+no_connect"))
    )
    (net (code "211") (name "unconnected-(U1-PA12{slash}USB1DP-Pad33)") (class "Default")
      (node (ref "U1") (pin "33") (pinfunction "PA12/USB1DP_33") (pintype "unspecified+no_connect"))
    )
    (net (code "212") (name "unconnected-(U1-PB2{slash}BOOT1-Pad20)") (class "Default")
      (node (ref "U1") (pin "20") (pinfunction "PB2/BOOT1_20") (pintype "unspecified+no_connect"))
    )
    (net (code "213") (name "unconnected-(U1-PB3-Pad39)") (class "Default")
      (node (ref "U1") (pin "39") (pinfunction "PB3_39") (pintype "unspecified+no_connect"))
    )
    (net (code "214") (name "unconnected-(U1-PB4-Pad40)") (class "Default")
      (node (ref "U1") (pin "40") (pinfunction "PB4_40") (pintype "unspecified+no_connect"))
    )
    (net (code "215") (name "unconnected-(U1-PB5-Pad41)") (class "Default")
      (node (ref "U1") (pin "41") (pinfunction "PB5_41") (pintype "unspecified+no_connect"))
    )
    (net (code "216") (name "unconnected-(U1-PB12-Pad25)") (class "Default")
      (node (ref "U1") (pin "25") (pinfunction "PB12_25") (pintype "unspecified+no_connect"))
    )
    (net (code "217") (name "unconnected-(U1-PB13-Pad26)") (class "Default")
      (node (ref "U1") (pin "26") (pinfunction "PB13_26") (pintype "unspecified+no_connect"))
    )
    (net (code "218") (name "unconnected-(U1-PC13{slash}TAMPER_RTC-Pad2)") (class "Default")
      (node (ref "U1") (pin "2") (pinfunction "PC13/TAMPER_RTC_2") (pintype "unspecified+no_connect"))
    )
    (net (code "219") (name "unconnected-(U1-PC14{slash}OSC32IN-Pad3)") (class "Default")
      (node (ref "U1") (pin "3") (pinfunction "PC14/OSC32IN_3") (pintype "unspecified+no_connect"))
    )
    (net (code "220") (name "unconnected-(U1-PC15{slash}OSC32OUT-Pad4)") (class "Default")
      (node (ref "U1") (pin "4") (pinfunction "PC15/OSC32OUT_4") (pintype "unspecified+no_connect"))
    )
    (net (code "221") (name "unconnected-(U4-NC-Pad4)") (class "Default")
      (node (ref "U4") (pin "4") (pinfunction "NC_4") (pintype "unspecified+no_connect"))
    )
    (net (code "222") (name "unconnected-(U5-NC-Pad5)") (class "Default")
      (node (ref "U5") (pin "5") (pinfunction "NC_5") (pintype "unspecified+no_connect"))
    )
    (net (code "223") (name "unconnected-(U5-NC-Pad7)") (class "Default")
      (node (ref "U5") (pin "7") (pinfunction "NC_7") (pintype "unspecified+no_connect"))
    )
    (net (code "224") (name "unconnected-(U5-NC-Pad8)") (class "Default")
      (node (ref "U5") (pin "8") (pinfunction "NC_8") (pintype "unspecified+no_connect"))
    )
    (net (code "225") (name "unconnected-(U5-NC-Pad21)") (class "Default")
      (node (ref "U5") (pin "21") (pinfunction "NC_21") (pintype "unspecified+no_connect"))
    )
    (net (code "226") (name "unconnected-(U6-OSC_IN{slash}PD0-Pad5)") (class "Default")
      (node (ref "U6") (pin "5") (pinfunction "OSC_IN/PD0_5") (pintype "unspecified+no_connect"))
    )
    (net (code "227") (name "unconnected-(U6-OSC_OUT{slash}PD1-Pad6)") (class "Default")
      (node (ref "U6") (pin "6") (pinfunction "OSC_OUT/PD1_6") (pintype "unspecified+no_connect"))
    )
    (net (code "228") (name "unconnected-(U6-PA0{slash}WKUP{slash}ADC0-Pad10)") (class "Default")
      (node (ref "U6") (pin "10") (pinfunction "PA0/WKUP/ADC0_10") (pintype "unspecified+no_connect"))
    )
    (net (code "229") (name "unconnected-(U6-PA6{slash}ADC6-Pad16)") (class "Default")
      (node (ref "U6") (pin "16") (pinfunction "PA6/ADC6_16") (pintype "unspecified+no_connect"))
    )
    (net (code "230") (name "unconnected-(U6-PA11{slash}USB1DM-Pad32)") (class "Default")
      (node (ref "U6") (pin "32") (pinfunction "PA11/USB1DM_32") (pintype "unspecified+no_connect"))
    )
    (net (code "231") (name "unconnected-(U6-PA12{slash}USB1DP-Pad33)") (class "Default")
      (node (ref "U6") (pin "33") (pinfunction "PA12/USB1DP_33") (pintype "unspecified+no_connect"))
    )
    (net (code "232") (name "unconnected-(U6-PB2{slash}BOOT1-Pad20)") (class "Default")
      (node (ref "U6") (pin "20") (pinfunction "PB2/BOOT1_20") (pintype "unspecified+no_connect"))
    )
    (net (code "233") (name "unconnected-(U6-PB3-Pad39)") (class "Default")
      (node (ref "U6") (pin "39") (pinfunction "PB3_39") (pintype "unspecified+no_connect"))
    )
    (net (code "234") (name "unconnected-(U6-PB4-Pad40)") (class "Default")
      (node (ref "U6") (pin "40") (pinfunction "PB4_40") (pintype "unspecified+no_connect"))
    )
    (net (code "235") (name "unconnected-(U6-PB5-Pad41)") (class "Default")
      (node (ref "U6") (pin "41") (pinfunction "PB5_41") (pintype "unspecified+no_connect"))
    )
    (net (code "236") (name "unconnected-(U6-PB12-Pad25)") (class "Default")
      (node (ref "U6") (pin "25") (pinfunction "PB12_25") (pintype "unspecified+no_connect"))
    )
    (net (code "237") (name "unconnected-(U6-PB13-Pad26)") (class "Default")
      (node (ref "U6") (pin "26") (pinfunction "PB13_26") (pintype "unspecified+no_connect"))
    )
    (net (code "238") (name "unconnected-(U6-PC13{slash}TAMPER_RTC-Pad2)") (class "Default")
      (node (ref "U6") (pin "2") (pinfunction "PC13/TAMPER_RTC_2") (pintype "unspecified+no_connect"))
    )
    (net (code "239") (name "unconnected-(U6-PC14{slash}OSC32IN-Pad3)") (class "Default")
      (node (ref "U6") (pin "3") (pinfunction "PC14/OSC32IN_3") (pintype "unspecified+no_connect"))
    )
    (net (code "240") (name "unconnected-(U6-PC15{slash}OSC32OUT-Pad4)") (class "Default")
      (node (ref "U6") (pin "4") (pinfunction "PC15/OSC32OUT_4") (pintype "unspecified+no_connect"))
    )
    (net (code "241") (name "unconnected-(U8-NC-Pad4)") (class "Default")
      (node (ref "U8") (pin "4") (pinfunction "NC_4") (pintype "unspecified+no_connect"))
    )
    (net (code "242") (name "unconnected-(U9-NC-Pad5)") (class "Default")
      (node (ref "U9") (pin "5") (pinfunction "NC_5") (pintype "unspecified+no_connect"))
    )
    (net (code "243") (name "unconnected-(U9-NC-Pad7)") (class "Default")
      (node (ref "U9") (pin "7") (pinfunction "NC_7") (pintype "unspecified+no_connect"))
    )
    (net (code "244") (name "unconnected-(U9-NC-Pad8)") (class "Default")
      (node (ref "U9") (pin "8") (pinfunction "NC_8") (pintype "unspecified+no_connect"))
    )
    (net (code "245") (name "unconnected-(U9-NC-Pad21)") (class "Default")
      (node (ref "U9") (pin "21") (pinfunction "NC_21") (pintype "unspecified+no_connect"))
    )
    (net (code "246") (name "unconnected-(U10-OSC_IN{slash}PD0-Pad5)") (class "Default")
      (node (ref "U10") (pin "5") (pinfunction "OSC_IN/PD0_5") (pintype "unspecified+no_connect"))
    )
    (net (code "247") (name "unconnected-(U10-OSC_OUT{slash}PD1-Pad6)") (class "Default")
      (node (ref "U10") (pin "6") (pinfunction "OSC_OUT/PD1_6") (pintype "unspecified+no_connect"))
    )
    (net (code "248") (name "unconnected-(U10-PA0{slash}WKUP{slash}ADC0-Pad10)") (class "Default")
      (node (ref "U10") (pin "10") (pinfunction "PA0/WKUP/ADC0_10") (pintype "unspecified+no_connect"))
    )
    (net (code "249") (name "unconnected-(U10-PA6{slash}ADC6-Pad16)") (class "Default")
      (node (ref "U10") (pin "16") (pinfunction "PA6/ADC6_16") (pintype "unspecified+no_connect"))
    )
    (net (code "250") (name "unconnected-(U10-PA11{slash}USB1DM-Pad32)") (class "Default")
      (node (ref "U10") (pin "32") (pinfunction "PA11/USB1DM_32") (pintype "unspecified+no_connect"))
    )
    (net (code "251") (name "unconnected-(U10-PA12{slash}USB1DP-Pad33)") (class "Default")
      (node (ref "U10") (pin "33") (pinfunction "PA12/USB1DP_33") (pintype "unspecified+no_connect"))
    )
    (net (code "252") (name "unconnected-(U10-PB2{slash}BOOT1-Pad20)") (class "Default")
      (node (ref "U10") (pin "20") (pinfunction "PB2/BOOT1_20") (pintype "unspecified+no_connect"))
    )
    (net (code "253") (name "unconnected-(U10-PB3-Pad39)") (class "Default")
      (node (ref "U10") (pin "39") (pinfunction "PB3_39") (pintype "unspecified+no_connect"))
    )
    (net (code "254") (name "unconnected-(U10-PB4-Pad40)") (class "Default")
      (node (ref "U10") (pin "40") (pinfunction "PB4_40") (pintype "unspecified+no_connect"))
    )
    (net (code "255") (name "unconnected-(U10-PB5-Pad41)") (class "Default")
      (node (ref "U10") (pin "41") (pinfunction "PB5_41") (pintype "unspecified+no_connect"))
    )
    (net (code "256") (name "unconnected-(U10-PB12-Pad25)") (class "Default")
      (node (ref "U10") (pin "25") (pinfunction "PB12_25") (pintype "unspecified+no_connect"))
    )
    (net (code "257") (name "unconnected-(U10-PB13-Pad26)") (class "Default")
      (node (ref "U10") (pin "26") (pinfunction "PB13_26") (pintype "unspecified+no_connect"))
    )
    (net (code "258") (name "unconnected-(U10-PC13{slash}TAMPER_RTC-Pad2)") (class "Default")
      (node (ref "U10") (pin "2") (pinfunction "PC13/TAMPER_RTC_2") (pintype "unspecified+no_connect"))
    )
    (net (code "259") (name "unconnected-(U10-PC14{slash}OSC32IN-Pad3)") (class "Default")
      (node (ref "U10") (pin "3") (pinfunction "PC14/OSC32IN_3") (pintype "unspecified+no_connect"))
    )
    (net (code "260") (name "unconnected-(U10-PC15{slash}OSC32OUT-Pad4)") (class "Default")
      (node (ref "U10") (pin "4") (pinfunction "PC15/OSC32OUT_4") (pintype "unspecified+no_connect"))
    )
    (net (code "261") (name "unconnected-(U12-NC-Pad4)") (class "Default")
      (node (ref "U12") (pin "4") (pinfunction "NC_4") (pintype "unspecified+no_connect"))
    )
    (net (code "262") (name "unconnected-(U13-NC-Pad5)") (class "Default")
      (node (ref "U13") (pin "5") (pinfunction "NC_5") (pintype "unspecified+no_connect"))
    )
    (net (code "263") (name "unconnected-(U13-NC-Pad7)") (class "Default")
      (node (ref "U13") (pin "7") (pinfunction "NC_7") (pintype "unspecified+no_connect"))
    )
    (net (code "264") (name "unconnected-(U13-NC-Pad8)") (class "Default")
      (node (ref "U13") (pin "8") (pinfunction "NC_8") (pintype "unspecified+no_connect"))
    )
    (net (code "265") (name "unconnected-(U13-NC-Pad21)") (class "Default")
      (node (ref "U13") (pin "21") (pinfunction "NC_21") (pintype "unspecified+no_connect"))
    )
    (net (code "266") (name "unconnected-(U14-OSC_IN{slash}PD0-Pad5)") (class "Default")
      (node (ref "U14") (pin "5") (pinfunction "OSC_IN/PD0_5") (pintype "unspecified+no_connect"))
    )
    (net (code "267") (name "unconnected-(U14-OSC_OUT{slash}PD1-Pad6)") (class "Default")
      (node (ref "U14") (pin "6") (pinfunction "OSC_OUT/PD1_6") (pintype "unspecified+no_connect"))
    )
    (net (code "268") (name "unconnected-(U14-PA0{slash}WKUP{slash}ADC0-Pad10)") (class "Default")
      (node (ref "U14") (pin "10") (pinfunction "PA0/WKUP/ADC0_10") (pintype "unspecified+no_connect"))
    )
    (net (code "269") (name "unconnected-(U14-PA6{slash}ADC6-Pad16)") (class "Default")
      (node (ref "U14") (pin "16") (pinfunction "PA6/ADC6_16") (pintype "unspecified+no_connect"))
    )
    (net (code "270") (name "unconnected-(U14-PA11{slash}USB1DM-Pad32)") (class "Default")
      (node (ref "U14") (pin "32") (pinfunction "PA11/USB1DM_32") (pintype "unspecified+no_connect"))
    )
    (net (code "271") (name "unconnected-(U14-PA12{slash}USB1DP-Pad33)") (class "Default")
      (node (ref "U14") (pin "33") (pinfunction "PA12/USB1DP_33") (pintype "unspecified+no_connect"))
    )
    (net (code "272") (name "unconnected-(U14-PB2{slash}BOOT1-Pad20)") (class "Default")
      (node (ref "U14") (pin "20") (pinfunction "PB2/BOOT1_20") (pintype "unspecified+no_connect"))
    )
    (net (code "273") (name "unconnected-(U14-PB3-Pad39)") (class "Default")
      (node (ref "U14") (pin "39") (pinfunction "PB3_39") (pintype "unspecified+no_connect"))
    )
    (net (code "274") (name "unconnected-(U14-PB4-Pad40)") (class "Default")
      (node (ref "U14") (pin "40") (pinfunction "PB4_40") (pintype "unspecified+no_connect"))
    )
    (net (code "275") (name "unconnected-(U14-PB5-Pad41)") (class "Default")
      (node (ref "U14") (pin "41") (pinfunction "PB5_41") (pintype "unspecified+no_connect"))
    )
    (net (code "276") (name "unconnected-(U14-PB12-Pad25)") (class "Default")
      (node (ref "U14") (pin "25") (pinfunction "PB12_25") (pintype "unspecified+no_connect"))
    )
    (net (code "277") (name "unconnected-(U14-PB13-Pad26)") (class "Default")
      (node (ref "U14") (pin "26") (pinfunction "PB13_26") (pintype "unspecified+no_connect"))
    )
    (net (code "278") (name "unconnected-(U14-PC13{slash}TAMPER_RTC-Pad2)") (class "Default")
      (node (ref "U14") (pin "2") (pinfunction "PC13/TAMPER_RTC_2") (pintype "unspecified+no_connect"))
    )
    (net (code "279") (name "unconnected-(U14-PC14{slash}OSC32IN-Pad3)") (class "Default")
      (node (ref "U14") (pin "3") (pinfunction "PC14/OSC32IN_3") (pintype "unspecified+no_connect"))
    )
    (net (code "280") (name "unconnected-(U14-PC15{slash}OSC32OUT-Pad4)") (class "Default")
      (node (ref "U14") (pin "4") (pinfunction "PC15/OSC32OUT_4") (pintype "unspecified+no_connect"))
    )
    (net (code "281") (name "unconnected-(U16-NC-Pad4)") (class "Default")
      (node (ref "U16") (pin "4") (pinfunction "NC_4") (pintype "unspecified+no_connect"))
    )
    (net (code "282") (name "unconnected-(U17-NC-Pad5)") (class "Default")
      (node (ref "U17") (pin "5") (pinfunction "NC_5") (pintype "unspecified+no_connect"))
    )
    (net (code "283") (name "unconnected-(U17-NC-Pad7)") (class "Default")
      (node (ref "U17") (pin "7") (pinfunction "NC_7") (pintype "unspecified+no_connect"))
    )
    (net (code "284") (name "unconnected-(U17-NC-Pad8)") (class "Default")
      (node (ref "U17") (pin "8") (pinfunction "NC_8") (pintype "unspecified+no_connect"))
    )
    (net (code "285") (name "unconnected-(U17-NC-Pad21)") (class "Default")
      (node (ref "U17") (pin "21") (pinfunction "NC_21") (pintype "unspecified+no_connect"))
    )
  )
)
